# POGO_Tester_Rev1_Connectors.net
KiCad netlist of a schematic drawn in Altium Designer
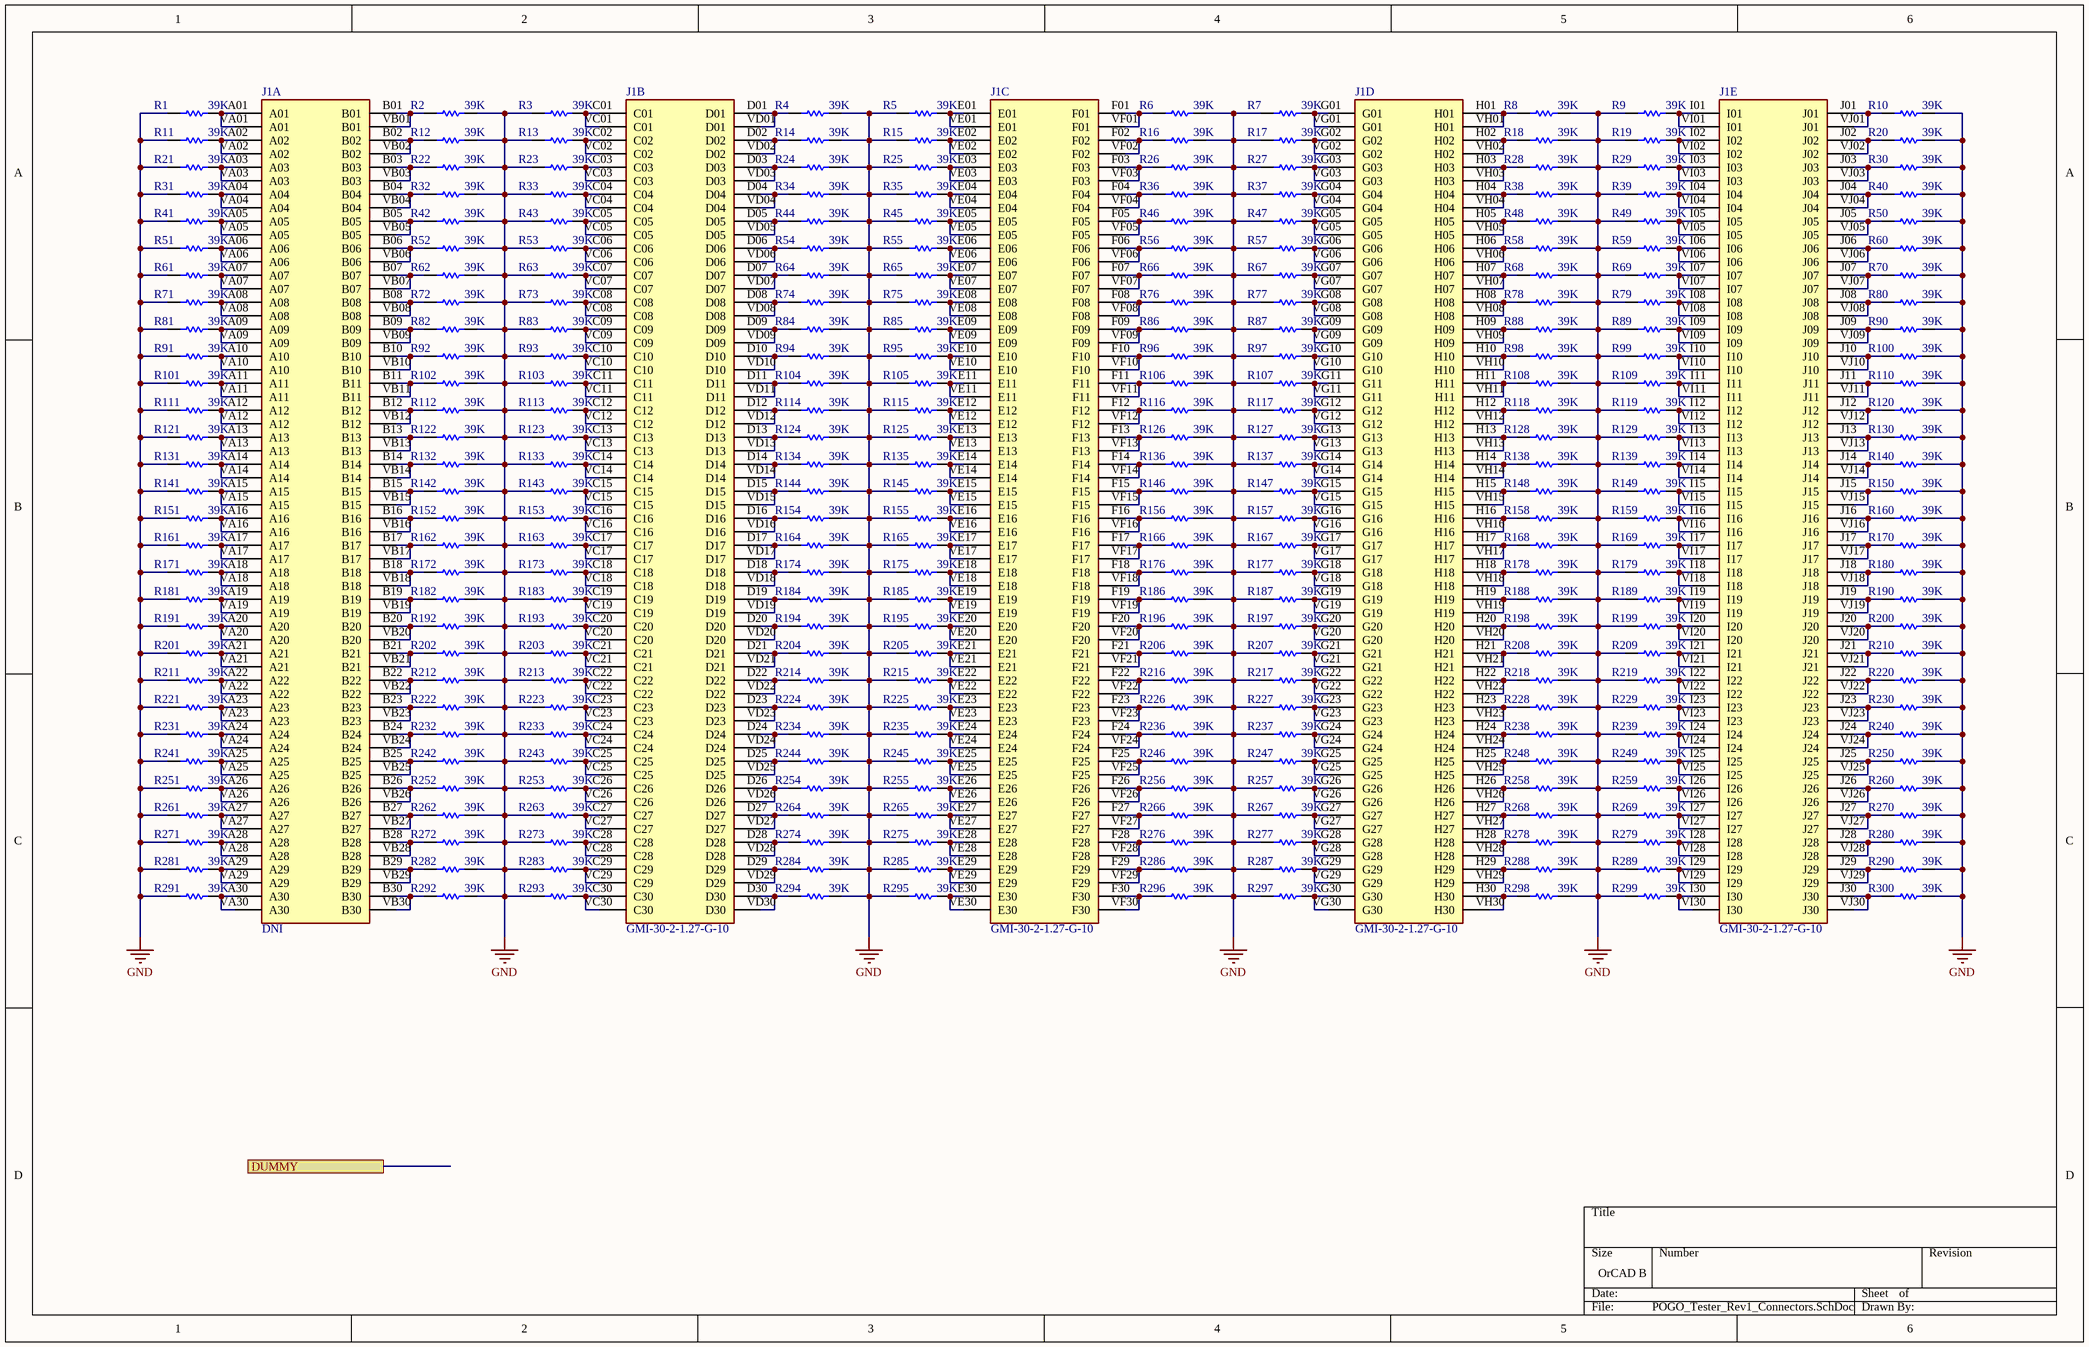
[diagram p0: POGO_Tester_Rev1_Connectors.SchDoc]

(export (version "E")
  (design (tool "Eeschema 10.0.6"))
  (components
    (comp (ref "J1")
      (value "DNI")
      (footprint "SAMTEC_GMI-30-2-1.27-G-10 - Nothing But Pads")
      (fields (field (name "MP") "GMI-30-2-1.27-G-10"))
      (libsource (lib "Avery Schem Library") (part "GMI-30-2-1.27-G-10"))
    )
    (comp (ref "R1")
      (value "39K")
      (footprint "DEFAULT_RESISTOR_0402")
      (description "RES 39K OHM 1% 1/3W 0402")
      (fields (field (name "POWER") "1/3W") (field (name "TOLERANCE") "1%"))
      (libsource (lib "Avery Altium Llibrary") (part "RCS040239K0FKED"))
    )
    (comp (ref "R2")
      (value "39K")
      (footprint "DEFAULT_RESISTOR_0402")
      (description "RES 39K OHM 1% 1/3W 0402")
      (fields (field (name "POWER") "1/3W") (field (name "TOLERANCE") "1%"))
      (libsource (lib "Avery Altium Llibrary") (part "RCS040239K0FKED"))
    )
    (comp (ref "R3")
      (value "39K")
      (footprint "DEFAULT_RESISTOR_0402")
      (description "RES 39K OHM 1% 1/3W 0402")
      (fields (field (name "POWER") "1/3W") (field (name "TOLERANCE") "1%"))
      (libsource (lib "Avery Altium Llibrary") (part "RCS040239K0FKED"))
    )
    (comp (ref "R4")
      (value "39K")
      (footprint "DEFAULT_RESISTOR_0402")
      (description "RES 39K OHM 1% 1/3W 0402")
      (fields (field (name "POWER") "1/3W") (field (name "TOLERANCE") "1%"))
      (libsource (lib "Avery Altium Llibrary") (part "RCS040239K0FKED"))
    )
    (comp (ref "R5")
      (value "39K")
      (footprint "DEFAULT_RESISTOR_0402")
      (description "RES 39K OHM 1% 1/3W 0402")
      (fields (field (name "POWER") "1/3W") (field (name "TOLERANCE") "1%"))
      (libsource (lib "Avery Altium Llibrary") (part "RCS040239K0FKED"))
    )
    (comp (ref "R6")
      (value "39K")
      (footprint "DEFAULT_RESISTOR_0402")
      (description "RES 39K OHM 1% 1/3W 0402")
      (fields (field (name "POWER") "1/3W") (field (name "TOLERANCE") "1%"))
      (libsource (lib "Avery Altium Llibrary") (part "RCS040239K0FKED"))
    )
    (comp (ref "R7")
      (value "39K")
      (footprint "DEFAULT_RESISTOR_0402")
      (description "RES 39K OHM 1% 1/3W 0402")
      (fields (field (name "POWER") "1/3W") (field (name "TOLERANCE") "1%"))
      (libsource (lib "Avery Altium Llibrary") (part "RCS040239K0FKED"))
    )
    (comp (ref "R8")
      (value "39K")
      (footprint "DEFAULT_RESISTOR_0402")
      (description "RES 39K OHM 1% 1/3W 0402")
      (fields (field (name "POWER") "1/3W") (field (name "TOLERANCE") "1%"))
      (libsource (lib "Avery Altium Llibrary") (part "RCS040239K0FKED"))
    )
    (comp (ref "R9")
      (value "39K")
      (footprint "DEFAULT_RESISTOR_0402")
      (description "RES 39K OHM 1% 1/3W 0402")
      (fields (field (name "POWER") "1/3W") (field (name "TOLERANCE") "1%"))
      (libsource (lib "Avery Altium Llibrary") (part "RCS040239K0FKED"))
    )
    (comp (ref "R10")
      (value "39K")
      (footprint "DEFAULT_RESISTOR_0402")
      (description "RES 39K OHM 1% 1/3W 0402")
      (fields (field (name "POWER") "1/3W") (field (name "TOLERANCE") "1%"))
      (libsource (lib "Avery Altium Llibrary") (part "RCS040239K0FKED"))
    )
    (comp (ref "R11")
      (value "39K")
      (footprint "DEFAULT_RESISTOR_0402")
      (description "RES 39K OHM 1% 1/3W 0402")
      (fields (field (name "POWER") "1/3W") (field (name "TOLERANCE") "1%"))
      (libsource (lib "Avery Altium Llibrary") (part "RCS040239K0FKED"))
    )
    (comp (ref "R12")
      (value "39K")
      (footprint "DEFAULT_RESISTOR_0402")
      (description "RES 39K OHM 1% 1/3W 0402")
      (fields (field (name "POWER") "1/3W") (field (name "TOLERANCE") "1%"))
      (libsource (lib "Avery Altium Llibrary") (part "RCS040239K0FKED"))
    )
    (comp (ref "R13")
      (value "39K")
      (footprint "DEFAULT_RESISTOR_0402")
      (description "RES 39K OHM 1% 1/3W 0402")
      (fields (field (name "POWER") "1/3W") (field (name "TOLERANCE") "1%"))
      (libsource (lib "Avery Altium Llibrary") (part "RCS040239K0FKED"))
    )
    (comp (ref "R14")
      (value "39K")
      (footprint "DEFAULT_RESISTOR_0402")
      (description "RES 39K OHM 1% 1/3W 0402")
      (fields (field (name "POWER") "1/3W") (field (name "TOLERANCE") "1%"))
      (libsource (lib "Avery Altium Llibrary") (part "RCS040239K0FKED"))
    )
    (comp (ref "R15")
      (value "39K")
      (footprint "DEFAULT_RESISTOR_0402")
      (description "RES 39K OHM 1% 1/3W 0402")
      (fields (field (name "POWER") "1/3W") (field (name "TOLERANCE") "1%"))
      (libsource (lib "Avery Altium Llibrary") (part "RCS040239K0FKED"))
    )
    (comp (ref "R16")
      (value "39K")
      (footprint "DEFAULT_RESISTOR_0402")
      (description "RES 39K OHM 1% 1/3W 0402")
      (fields (field (name "POWER") "1/3W") (field (name "TOLERANCE") "1%"))
      (libsource (lib "Avery Altium Llibrary") (part "RCS040239K0FKED"))
    )
    (comp (ref "R17")
      (value "39K")
      (footprint "DEFAULT_RESISTOR_0402")
      (description "RES 39K OHM 1% 1/3W 0402")
      (fields (field (name "POWER") "1/3W") (field (name "TOLERANCE") "1%"))
      (libsource (lib "Avery Altium Llibrary") (part "RCS040239K0FKED"))
    )
    (comp (ref "R18")
      (value "39K")
      (footprint "DEFAULT_RESISTOR_0402")
      (description "RES 39K OHM 1% 1/3W 0402")
      (fields (field (name "POWER") "1/3W") (field (name "TOLERANCE") "1%"))
      (libsource (lib "Avery Altium Llibrary") (part "RCS040239K0FKED"))
    )
    (comp (ref "R19")
      (value "39K")
      (footprint "DEFAULT_RESISTOR_0402")
      (description "RES 39K OHM 1% 1/3W 0402")
      (fields (field (name "POWER") "1/3W") (field (name "TOLERANCE") "1%"))
      (libsource (lib "Avery Altium Llibrary") (part "RCS040239K0FKED"))
    )
    (comp (ref "R20")
      (value "39K")
      (footprint "DEFAULT_RESISTOR_0402")
      (description "RES 39K OHM 1% 1/3W 0402")
      (fields (field (name "POWER") "1/3W") (field (name "TOLERANCE") "1%"))
      (libsource (lib "Avery Altium Llibrary") (part "RCS040239K0FKED"))
    )
    (comp (ref "R21")
      (value "39K")
      (footprint "DEFAULT_RESISTOR_0402")
      (description "RES 39K OHM 1% 1/3W 0402")
      (fields (field (name "POWER") "1/3W") (field (name "TOLERANCE") "1%"))
      (libsource (lib "Avery Altium Llibrary") (part "RCS040239K0FKED"))
    )
    (comp (ref "R22")
      (value "39K")
      (footprint "DEFAULT_RESISTOR_0402")
      (description "RES 39K OHM 1% 1/3W 0402")
      (fields (field (name "POWER") "1/3W") (field (name "TOLERANCE") "1%"))
      (libsource (lib "Avery Altium Llibrary") (part "RCS040239K0FKED"))
    )
    (comp (ref "R23")
      (value "39K")
      (footprint "DEFAULT_RESISTOR_0402")
      (description "RES 39K OHM 1% 1/3W 0402")
      (fields (field (name "POWER") "1/3W") (field (name "TOLERANCE") "1%"))
      (libsource (lib "Avery Altium Llibrary") (part "RCS040239K0FKED"))
    )
    (comp (ref "R24")
      (value "39K")
      (footprint "DEFAULT_RESISTOR_0402")
      (description "RES 39K OHM 1% 1/3W 0402")
      (fields (field (name "POWER") "1/3W") (field (name "TOLERANCE") "1%"))
      (libsource (lib "Avery Altium Llibrary") (part "RCS040239K0FKED"))
    )
    (comp (ref "R25")
      (value "39K")
      (footprint "DEFAULT_RESISTOR_0402")
      (description "RES 39K OHM 1% 1/3W 0402")
      (fields (field (name "POWER") "1/3W") (field (name "TOLERANCE") "1%"))
      (libsource (lib "Avery Altium Llibrary") (part "RCS040239K0FKED"))
    )
    (comp (ref "R26")
      (value "39K")
      (footprint "DEFAULT_RESISTOR_0402")
      (description "RES 39K OHM 1% 1/3W 0402")
      (fields (field (name "POWER") "1/3W") (field (name "TOLERANCE") "1%"))
      (libsource (lib "Avery Altium Llibrary") (part "RCS040239K0FKED"))
    )
    (comp (ref "R27")
      (value "39K")
      (footprint "DEFAULT_RESISTOR_0402")
      (description "RES 39K OHM 1% 1/3W 0402")
      (fields (field (name "POWER") "1/3W") (field (name "TOLERANCE") "1%"))
      (libsource (lib "Avery Altium Llibrary") (part "RCS040239K0FKED"))
    )
    (comp (ref "R28")
      (value "39K")
      (footprint "DEFAULT_RESISTOR_0402")
      (description "RES 39K OHM 1% 1/3W 0402")
      (fields (field (name "POWER") "1/3W") (field (name "TOLERANCE") "1%"))
      (libsource (lib "Avery Altium Llibrary") (part "RCS040239K0FKED"))
    )
    (comp (ref "R29")
      (value "39K")
      (footprint "DEFAULT_RESISTOR_0402")
      (description "RES 39K OHM 1% 1/3W 0402")
      (fields (field (name "POWER") "1/3W") (field (name "TOLERANCE") "1%"))
      (libsource (lib "Avery Altium Llibrary") (part "RCS040239K0FKED"))
    )
    (comp (ref "R30")
      (value "39K")
      (footprint "DEFAULT_RESISTOR_0402")
      (description "RES 39K OHM 1% 1/3W 0402")
      (fields (field (name "POWER") "1/3W") (field (name "TOLERANCE") "1%"))
      (libsource (lib "Avery Altium Llibrary") (part "RCS040239K0FKED"))
    )
    (comp (ref "R31")
      (value "39K")
      (footprint "DEFAULT_RESISTOR_0402")
      (description "RES 39K OHM 1% 1/3W 0402")
      (fields (field (name "POWER") "1/3W") (field (name "TOLERANCE") "1%"))
      (libsource (lib "Avery Altium Llibrary") (part "RCS040239K0FKED"))
    )
    (comp (ref "R32")
      (value "39K")
      (footprint "DEFAULT_RESISTOR_0402")
      (description "RES 39K OHM 1% 1/3W 0402")
      (fields (field (name "POWER") "1/3W") (field (name "TOLERANCE") "1%"))
      (libsource (lib "Avery Altium Llibrary") (part "RCS040239K0FKED"))
    )
    (comp (ref "R33")
      (value "39K")
      (footprint "DEFAULT_RESISTOR_0402")
      (description "RES 39K OHM 1% 1/3W 0402")
      (fields (field (name "POWER") "1/3W") (field (name "TOLERANCE") "1%"))
      (libsource (lib "Avery Altium Llibrary") (part "RCS040239K0FKED"))
    )
    (comp (ref "R34")
      (value "39K")
      (footprint "DEFAULT_RESISTOR_0402")
      (description "RES 39K OHM 1% 1/3W 0402")
      (fields (field (name "POWER") "1/3W") (field (name "TOLERANCE") "1%"))
      (libsource (lib "Avery Altium Llibrary") (part "RCS040239K0FKED"))
    )
    (comp (ref "R35")
      (value "39K")
      (footprint "DEFAULT_RESISTOR_0402")
      (description "RES 39K OHM 1% 1/3W 0402")
      (fields (field (name "POWER") "1/3W") (field (name "TOLERANCE") "1%"))
      (libsource (lib "Avery Altium Llibrary") (part "RCS040239K0FKED"))
    )
    (comp (ref "R36")
      (value "39K")
      (footprint "DEFAULT_RESISTOR_0402")
      (description "RES 39K OHM 1% 1/3W 0402")
      (fields (field (name "POWER") "1/3W") (field (name "TOLERANCE") "1%"))
      (libsource (lib "Avery Altium Llibrary") (part "RCS040239K0FKED"))
    )
    (comp (ref "R37")
      (value "39K")
      (footprint "DEFAULT_RESISTOR_0402")
      (description "RES 39K OHM 1% 1/3W 0402")
      (fields (field (name "POWER") "1/3W") (field (name "TOLERANCE") "1%"))
      (libsource (lib "Avery Altium Llibrary") (part "RCS040239K0FKED"))
    )
    (comp (ref "R38")
      (value "39K")
      (footprint "DEFAULT_RESISTOR_0402")
      (description "RES 39K OHM 1% 1/3W 0402")
      (fields (field (name "POWER") "1/3W") (field (name "TOLERANCE") "1%"))
      (libsource (lib "Avery Altium Llibrary") (part "RCS040239K0FKED"))
    )
    (comp (ref "R39")
      (value "39K")
      (footprint "DEFAULT_RESISTOR_0402")
      (description "RES 39K OHM 1% 1/3W 0402")
      (fields (field (name "POWER") "1/3W") (field (name "TOLERANCE") "1%"))
      (libsource (lib "Avery Altium Llibrary") (part "RCS040239K0FKED"))
    )
    (comp (ref "R40")
      (value "39K")
      (footprint "DEFAULT_RESISTOR_0402")
      (description "RES 39K OHM 1% 1/3W 0402")
      (fields (field (name "POWER") "1/3W") (field (name "TOLERANCE") "1%"))
      (libsource (lib "Avery Altium Llibrary") (part "RCS040239K0FKED"))
    )
    (comp (ref "R41")
      (value "39K")
      (footprint "DEFAULT_RESISTOR_0402")
      (description "RES 39K OHM 1% 1/3W 0402")
      (fields (field (name "POWER") "1/3W") (field (name "TOLERANCE") "1%"))
      (libsource (lib "Avery Altium Llibrary") (part "RCS040239K0FKED"))
    )
    (comp (ref "R42")
      (value "39K")
      (footprint "DEFAULT_RESISTOR_0402")
      (description "RES 39K OHM 1% 1/3W 0402")
      (fields (field (name "POWER") "1/3W") (field (name "TOLERANCE") "1%"))
      (libsource (lib "Avery Altium Llibrary") (part "RCS040239K0FKED"))
    )
    (comp (ref "R43")
      (value "39K")
      (footprint "DEFAULT_RESISTOR_0402")
      (description "RES 39K OHM 1% 1/3W 0402")
      (fields (field (name "POWER") "1/3W") (field (name "TOLERANCE") "1%"))
      (libsource (lib "Avery Altium Llibrary") (part "RCS040239K0FKED"))
    )
    (comp (ref "R44")
      (value "39K")
      (footprint "DEFAULT_RESISTOR_0402")
      (description "RES 39K OHM 1% 1/3W 0402")
      (fields (field (name "POWER") "1/3W") (field (name "TOLERANCE") "1%"))
      (libsource (lib "Avery Altium Llibrary") (part "RCS040239K0FKED"))
    )
    (comp (ref "R45")
      (value "39K")
      (footprint "DEFAULT_RESISTOR_0402")
      (description "RES 39K OHM 1% 1/3W 0402")
      (fields (field (name "POWER") "1/3W") (field (name "TOLERANCE") "1%"))
      (libsource (lib "Avery Altium Llibrary") (part "RCS040239K0FKED"))
    )
    (comp (ref "R46")
      (value "39K")
      (footprint "DEFAULT_RESISTOR_0402")
      (description "RES 39K OHM 1% 1/3W 0402")
      (fields (field (name "POWER") "1/3W") (field (name "TOLERANCE") "1%"))
      (libsource (lib "Avery Altium Llibrary") (part "RCS040239K0FKED"))
    )
    (comp (ref "R47")
      (value "39K")
      (footprint "DEFAULT_RESISTOR_0402")
      (description "RES 39K OHM 1% 1/3W 0402")
      (fields (field (name "POWER") "1/3W") (field (name "TOLERANCE") "1%"))
      (libsource (lib "Avery Altium Llibrary") (part "RCS040239K0FKED"))
    )
    (comp (ref "R48")
      (value "39K")
      (footprint "DEFAULT_RESISTOR_0402")
      (description "RES 39K OHM 1% 1/3W 0402")
      (fields (field (name "POWER") "1/3W") (field (name "TOLERANCE") "1%"))
      (libsource (lib "Avery Altium Llibrary") (part "RCS040239K0FKED"))
    )
    (comp (ref "R49")
      (value "39K")
      (footprint "DEFAULT_RESISTOR_0402")
      (description "RES 39K OHM 1% 1/3W 0402")
      (fields (field (name "POWER") "1/3W") (field (name "TOLERANCE") "1%"))
      (libsource (lib "Avery Altium Llibrary") (part "RCS040239K0FKED"))
    )
    (comp (ref "R50")
      (value "39K")
      (footprint "DEFAULT_RESISTOR_0402")
      (description "RES 39K OHM 1% 1/3W 0402")
      (fields (field (name "POWER") "1/3W") (field (name "TOLERANCE") "1%"))
      (libsource (lib "Avery Altium Llibrary") (part "RCS040239K0FKED"))
    )
    (comp (ref "R51")
      (value "39K")
      (footprint "DEFAULT_RESISTOR_0402")
      (description "RES 39K OHM 1% 1/3W 0402")
      (fields (field (name "POWER") "1/3W") (field (name "TOLERANCE") "1%"))
      (libsource (lib "Avery Altium Llibrary") (part "RCS040239K0FKED"))
    )
    (comp (ref "R52")
      (value "39K")
      (footprint "DEFAULT_RESISTOR_0402")
      (description "RES 39K OHM 1% 1/3W 0402")
      (fields (field (name "POWER") "1/3W") (field (name "TOLERANCE") "1%"))
      (libsource (lib "Avery Altium Llibrary") (part "RCS040239K0FKED"))
    )
    (comp (ref "R53")
      (value "39K")
      (footprint "DEFAULT_RESISTOR_0402")
      (description "RES 39K OHM 1% 1/3W 0402")
      (fields (field (name "POWER") "1/3W") (field (name "TOLERANCE") "1%"))
      (libsource (lib "Avery Altium Llibrary") (part "RCS040239K0FKED"))
    )
    (comp (ref "R54")
      (value "39K")
      (footprint "DEFAULT_RESISTOR_0402")
      (description "RES 39K OHM 1% 1/3W 0402")
      (fields (field (name "POWER") "1/3W") (field (name "TOLERANCE") "1%"))
      (libsource (lib "Avery Altium Llibrary") (part "RCS040239K0FKED"))
    )
    (comp (ref "R55")
      (value "39K")
      (footprint "DEFAULT_RESISTOR_0402")
      (description "RES 39K OHM 1% 1/3W 0402")
      (fields (field (name "POWER") "1/3W") (field (name "TOLERANCE") "1%"))
      (libsource (lib "Avery Altium Llibrary") (part "RCS040239K0FKED"))
    )
    (comp (ref "R56")
      (value "39K")
      (footprint "DEFAULT_RESISTOR_0402")
      (description "RES 39K OHM 1% 1/3W 0402")
      (fields (field (name "POWER") "1/3W") (field (name "TOLERANCE") "1%"))
      (libsource (lib "Avery Altium Llibrary") (part "RCS040239K0FKED"))
    )
    (comp (ref "R57")
      (value "39K")
      (footprint "DEFAULT_RESISTOR_0402")
      (description "RES 39K OHM 1% 1/3W 0402")
      (fields (field (name "POWER") "1/3W") (field (name "TOLERANCE") "1%"))
      (libsource (lib "Avery Altium Llibrary") (part "RCS040239K0FKED"))
    )
    (comp (ref "R58")
      (value "39K")
      (footprint "DEFAULT_RESISTOR_0402")
      (description "RES 39K OHM 1% 1/3W 0402")
      (fields (field (name "POWER") "1/3W") (field (name "TOLERANCE") "1%"))
      (libsource (lib "Avery Altium Llibrary") (part "RCS040239K0FKED"))
    )
    (comp (ref "R59")
      (value "39K")
      (footprint "DEFAULT_RESISTOR_0402")
      (description "RES 39K OHM 1% 1/3W 0402")
      (fields (field (name "POWER") "1/3W") (field (name "TOLERANCE") "1%"))
      (libsource (lib "Avery Altium Llibrary") (part "RCS040239K0FKED"))
    )
    (comp (ref "R60")
      (value "39K")
      (footprint "DEFAULT_RESISTOR_0402")
      (description "RES 39K OHM 1% 1/3W 0402")
      (fields (field (name "POWER") "1/3W") (field (name "TOLERANCE") "1%"))
      (libsource (lib "Avery Altium Llibrary") (part "RCS040239K0FKED"))
    )
    (comp (ref "R61")
      (value "39K")
      (footprint "DEFAULT_RESISTOR_0402")
      (description "RES 39K OHM 1% 1/3W 0402")
      (fields (field (name "POWER") "1/3W") (field (name "TOLERANCE") "1%"))
      (libsource (lib "Avery Altium Llibrary") (part "RCS040239K0FKED"))
    )
    (comp (ref "R62")
      (value "39K")
      (footprint "DEFAULT_RESISTOR_0402")
      (description "RES 39K OHM 1% 1/3W 0402")
      (fields (field (name "POWER") "1/3W") (field (name "TOLERANCE") "1%"))
      (libsource (lib "Avery Altium Llibrary") (part "RCS040239K0FKED"))
    )
    (comp (ref "R63")
      (value "39K")
      (footprint "DEFAULT_RESISTOR_0402")
      (description "RES 39K OHM 1% 1/3W 0402")
      (fields (field (name "POWER") "1/3W") (field (name "TOLERANCE") "1%"))
      (libsource (lib "Avery Altium Llibrary") (part "RCS040239K0FKED"))
    )
    (comp (ref "R64")
      (value "39K")
      (footprint "DEFAULT_RESISTOR_0402")
      (description "RES 39K OHM 1% 1/3W 0402")
      (fields (field (name "POWER") "1/3W") (field (name "TOLERANCE") "1%"))
      (libsource (lib "Avery Altium Llibrary") (part "RCS040239K0FKED"))
    )
    (comp (ref "R65")
      (value "39K")
      (footprint "DEFAULT_RESISTOR_0402")
      (description "RES 39K OHM 1% 1/3W 0402")
      (fields (field (name "POWER") "1/3W") (field (name "TOLERANCE") "1%"))
      (libsource (lib "Avery Altium Llibrary") (part "RCS040239K0FKED"))
    )
    (comp (ref "R66")
      (value "39K")
      (footprint "DEFAULT_RESISTOR_0402")
      (description "RES 39K OHM 1% 1/3W 0402")
      (fields (field (name "POWER") "1/3W") (field (name "TOLERANCE") "1%"))
      (libsource (lib "Avery Altium Llibrary") (part "RCS040239K0FKED"))
    )
    (comp (ref "R67")
      (value "39K")
      (footprint "DEFAULT_RESISTOR_0402")
      (description "RES 39K OHM 1% 1/3W 0402")
      (fields (field (name "POWER") "1/3W") (field (name "TOLERANCE") "1%"))
      (libsource (lib "Avery Altium Llibrary") (part "RCS040239K0FKED"))
    )
    (comp (ref "R68")
      (value "39K")
      (footprint "DEFAULT_RESISTOR_0402")
      (description "RES 39K OHM 1% 1/3W 0402")
      (fields (field (name "POWER") "1/3W") (field (name "TOLERANCE") "1%"))
      (libsource (lib "Avery Altium Llibrary") (part "RCS040239K0FKED"))
    )
    (comp (ref "R69")
      (value "39K")
      (footprint "DEFAULT_RESISTOR_0402")
      (description "RES 39K OHM 1% 1/3W 0402")
      (fields (field (name "POWER") "1/3W") (field (name "TOLERANCE") "1%"))
      (libsource (lib "Avery Altium Llibrary") (part "RCS040239K0FKED"))
    )
    (comp (ref "R70")
      (value "39K")
      (footprint "DEFAULT_RESISTOR_0402")
      (description "RES 39K OHM 1% 1/3W 0402")
      (fields (field (name "POWER") "1/3W") (field (name "TOLERANCE") "1%"))
      (libsource (lib "Avery Altium Llibrary") (part "RCS040239K0FKED"))
    )
    (comp (ref "R71")
      (value "39K")
      (footprint "DEFAULT_RESISTOR_0402")
      (description "RES 39K OHM 1% 1/3W 0402")
      (fields (field (name "POWER") "1/3W") (field (name "TOLERANCE") "1%"))
      (libsource (lib "Avery Altium Llibrary") (part "RCS040239K0FKED"))
    )
    (comp (ref "R72")
      (value "39K")
      (footprint "DEFAULT_RESISTOR_0402")
      (description "RES 39K OHM 1% 1/3W 0402")
      (fields (field (name "POWER") "1/3W") (field (name "TOLERANCE") "1%"))
      (libsource (lib "Avery Altium Llibrary") (part "RCS040239K0FKED"))
    )
    (comp (ref "R73")
      (value "39K")
      (footprint "DEFAULT_RESISTOR_0402")
      (description "RES 39K OHM 1% 1/3W 0402")
      (fields (field (name "POWER") "1/3W") (field (name "TOLERANCE") "1%"))
      (libsource (lib "Avery Altium Llibrary") (part "RCS040239K0FKED"))
    )
    (comp (ref "R74")
      (value "39K")
      (footprint "DEFAULT_RESISTOR_0402")
      (description "RES 39K OHM 1% 1/3W 0402")
      (fields (field (name "POWER") "1/3W") (field (name "TOLERANCE") "1%"))
      (libsource (lib "Avery Altium Llibrary") (part "RCS040239K0FKED"))
    )
    (comp (ref "R75")
      (value "39K")
      (footprint "DEFAULT_RESISTOR_0402")
      (description "RES 39K OHM 1% 1/3W 0402")
      (fields (field (name "POWER") "1/3W") (field (name "TOLERANCE") "1%"))
      (libsource (lib "Avery Altium Llibrary") (part "RCS040239K0FKED"))
    )
    (comp (ref "R76")
      (value "39K")
      (footprint "DEFAULT_RESISTOR_0402")
      (description "RES 39K OHM 1% 1/3W 0402")
      (fields (field (name "POWER") "1/3W") (field (name "TOLERANCE") "1%"))
      (libsource (lib "Avery Altium Llibrary") (part "RCS040239K0FKED"))
    )
    (comp (ref "R77")
      (value "39K")
      (footprint "DEFAULT_RESISTOR_0402")
      (description "RES 39K OHM 1% 1/3W 0402")
      (fields (field (name "POWER") "1/3W") (field (name "TOLERANCE") "1%"))
      (libsource (lib "Avery Altium Llibrary") (part "RCS040239K0FKED"))
    )
    (comp (ref "R78")
      (value "39K")
      (footprint "DEFAULT_RESISTOR_0402")
      (description "RES 39K OHM 1% 1/3W 0402")
      (fields (field (name "POWER") "1/3W") (field (name "TOLERANCE") "1%"))
      (libsource (lib "Avery Altium Llibrary") (part "RCS040239K0FKED"))
    )
    (comp (ref "R79")
      (value "39K")
      (footprint "DEFAULT_RESISTOR_0402")
      (description "RES 39K OHM 1% 1/3W 0402")
      (fields (field (name "POWER") "1/3W") (field (name "TOLERANCE") "1%"))
      (libsource (lib "Avery Altium Llibrary") (part "RCS040239K0FKED"))
    )
    (comp (ref "R80")
      (value "39K")
      (footprint "DEFAULT_RESISTOR_0402")
      (description "RES 39K OHM 1% 1/3W 0402")
      (fields (field (name "POWER") "1/3W") (field (name "TOLERANCE") "1%"))
      (libsource (lib "Avery Altium Llibrary") (part "RCS040239K0FKED"))
    )
    (comp (ref "R81")
      (value "39K")
      (footprint "DEFAULT_RESISTOR_0402")
      (description "RES 39K OHM 1% 1/3W 0402")
      (fields (field (name "POWER") "1/3W") (field (name "TOLERANCE") "1%"))
      (libsource (lib "Avery Altium Llibrary") (part "RCS040239K0FKED"))
    )
    (comp (ref "R82")
      (value "39K")
      (footprint "DEFAULT_RESISTOR_0402")
      (description "RES 39K OHM 1% 1/3W 0402")
      (fields (field (name "POWER") "1/3W") (field (name "TOLERANCE") "1%"))
      (libsource (lib "Avery Altium Llibrary") (part "RCS040239K0FKED"))
    )
    (comp (ref "R83")
      (value "39K")
      (footprint "DEFAULT_RESISTOR_0402")
      (description "RES 39K OHM 1% 1/3W 0402")
      (fields (field (name "POWER") "1/3W") (field (name "TOLERANCE") "1%"))
      (libsource (lib "Avery Altium Llibrary") (part "RCS040239K0FKED"))
    )
    (comp (ref "R84")
      (value "39K")
      (footprint "DEFAULT_RESISTOR_0402")
      (description "RES 39K OHM 1% 1/3W 0402")
      (fields (field (name "POWER") "1/3W") (field (name "TOLERANCE") "1%"))
      (libsource (lib "Avery Altium Llibrary") (part "RCS040239K0FKED"))
    )
    (comp (ref "R85")
      (value "39K")
      (footprint "DEFAULT_RESISTOR_0402")
      (description "RES 39K OHM 1% 1/3W 0402")
      (fields (field (name "POWER") "1/3W") (field (name "TOLERANCE") "1%"))
      (libsource (lib "Avery Altium Llibrary") (part "RCS040239K0FKED"))
    )
    (comp (ref "R86")
      (value "39K")
      (footprint "DEFAULT_RESISTOR_0402")
      (description "RES 39K OHM 1% 1/3W 0402")
      (fields (field (name "POWER") "1/3W") (field (name "TOLERANCE") "1%"))
      (libsource (lib "Avery Altium Llibrary") (part "RCS040239K0FKED"))
    )
    (comp (ref "R87")
      (value "39K")
      (footprint "DEFAULT_RESISTOR_0402")
      (description "RES 39K OHM 1% 1/3W 0402")
      (fields (field (name "POWER") "1/3W") (field (name "TOLERANCE") "1%"))
      (libsource (lib "Avery Altium Llibrary") (part "RCS040239K0FKED"))
    )
    (comp (ref "R88")
      (value "39K")
      (footprint "DEFAULT_RESISTOR_0402")
      (description "RES 39K OHM 1% 1/3W 0402")
      (fields (field (name "POWER") "1/3W") (field (name "TOLERANCE") "1%"))
      (libsource (lib "Avery Altium Llibrary") (part "RCS040239K0FKED"))
    )
    (comp (ref "R89")
      (value "39K")
      (footprint "DEFAULT_RESISTOR_0402")
      (description "RES 39K OHM 1% 1/3W 0402")
      (fields (field (name "POWER") "1/3W") (field (name "TOLERANCE") "1%"))
      (libsource (lib "Avery Altium Llibrary") (part "RCS040239K0FKED"))
    )
    (comp (ref "R90")
      (value "39K")
      (footprint "DEFAULT_RESISTOR_0402")
      (description "RES 39K OHM 1% 1/3W 0402")
      (fields (field (name "POWER") "1/3W") (field (name "TOLERANCE") "1%"))
      (libsource (lib "Avery Altium Llibrary") (part "RCS040239K0FKED"))
    )
    (comp (ref "R91")
      (value "39K")
      (footprint "DEFAULT_RESISTOR_0402")
      (description "RES 39K OHM 1% 1/3W 0402")
      (fields (field (name "POWER") "1/3W") (field (name "TOLERANCE") "1%"))
      (libsource (lib "Avery Altium Llibrary") (part "RCS040239K0FKED"))
    )
    (comp (ref "R92")
      (value "39K")
      (footprint "DEFAULT_RESISTOR_0402")
      (description "RES 39K OHM 1% 1/3W 0402")
      (fields (field (name "POWER") "1/3W") (field (name "TOLERANCE") "1%"))
      (libsource (lib "Avery Altium Llibrary") (part "RCS040239K0FKED"))
    )
    (comp (ref "R93")
      (value "39K")
      (footprint "DEFAULT_RESISTOR_0402")
      (description "RES 39K OHM 1% 1/3W 0402")
      (fields (field (name "POWER") "1/3W") (field (name "TOLERANCE") "1%"))
      (libsource (lib "Avery Altium Llibrary") (part "RCS040239K0FKED"))
    )
    (comp (ref "R94")
      (value "39K")
      (footprint "DEFAULT_RESISTOR_0402")
      (description "RES 39K OHM 1% 1/3W 0402")
      (fields (field (name "POWER") "1/3W") (field (name "TOLERANCE") "1%"))
      (libsource (lib "Avery Altium Llibrary") (part "RCS040239K0FKED"))
    )
    (comp (ref "R95")
      (value "39K")
      (footprint "DEFAULT_RESISTOR_0402")
      (description "RES 39K OHM 1% 1/3W 0402")
      (fields (field (name "POWER") "1/3W") (field (name "TOLERANCE") "1%"))
      (libsource (lib "Avery Altium Llibrary") (part "RCS040239K0FKED"))
    )
    (comp (ref "R96")
      (value "39K")
      (footprint "DEFAULT_RESISTOR_0402")
      (description "RES 39K OHM 1% 1/3W 0402")
      (fields (field (name "POWER") "1/3W") (field (name "TOLERANCE") "1%"))
      (libsource (lib "Avery Altium Llibrary") (part "RCS040239K0FKED"))
    )
    (comp (ref "R97")
      (value "39K")
      (footprint "DEFAULT_RESISTOR_0402")
      (description "RES 39K OHM 1% 1/3W 0402")
      (fields (field (name "POWER") "1/3W") (field (name "TOLERANCE") "1%"))
      (libsource (lib "Avery Altium Llibrary") (part "RCS040239K0FKED"))
    )
    (comp (ref "R98")
      (value "39K")
      (footprint "DEFAULT_RESISTOR_0402")
      (description "RES 39K OHM 1% 1/3W 0402")
      (fields (field (name "POWER") "1/3W") (field (name "TOLERANCE") "1%"))
      (libsource (lib "Avery Altium Llibrary") (part "RCS040239K0FKED"))
    )
    (comp (ref "R99")
      (value "39K")
      (footprint "DEFAULT_RESISTOR_0402")
      (description "RES 39K OHM 1% 1/3W 0402")
      (fields (field (name "POWER") "1/3W") (field (name "TOLERANCE") "1%"))
      (libsource (lib "Avery Altium Llibrary") (part "RCS040239K0FKED"))
    )
    (comp (ref "R100")
      (value "39K")
      (footprint "DEFAULT_RESISTOR_0402")
      (description "RES 39K OHM 1% 1/3W 0402")
      (fields (field (name "POWER") "1/3W") (field (name "TOLERANCE") "1%"))
      (libsource (lib "Avery Altium Llibrary") (part "RCS040239K0FKED"))
    )
    (comp (ref "R101")
      (value "39K")
      (footprint "DEFAULT_RESISTOR_0402")
      (description "RES 39K OHM 1% 1/3W 0402")
      (fields (field (name "POWER") "1/3W") (field (name "TOLERANCE") "1%"))
      (libsource (lib "Avery Altium Llibrary") (part "RCS040239K0FKED"))
    )
    (comp (ref "R102")
      (value "39K")
      (footprint "DEFAULT_RESISTOR_0402")
      (description "RES 39K OHM 1% 1/3W 0402")
      (fields (field (name "POWER") "1/3W") (field (name "TOLERANCE") "1%"))
      (libsource (lib "Avery Altium Llibrary") (part "RCS040239K0FKED"))
    )
    (comp (ref "R103")
      (value "39K")
      (footprint "DEFAULT_RESISTOR_0402")
      (description "RES 39K OHM 1% 1/3W 0402")
      (fields (field (name "POWER") "1/3W") (field (name "TOLERANCE") "1%"))
      (libsource (lib "Avery Altium Llibrary") (part "RCS040239K0FKED"))
    )
    (comp (ref "R104")
      (value "39K")
      (footprint "DEFAULT_RESISTOR_0402")
      (description "RES 39K OHM 1% 1/3W 0402")
      (fields (field (name "POWER") "1/3W") (field (name "TOLERANCE") "1%"))
      (libsource (lib "Avery Altium Llibrary") (part "RCS040239K0FKED"))
    )
    (comp (ref "R105")
      (value "39K")
      (footprint "DEFAULT_RESISTOR_0402")
      (description "RES 39K OHM 1% 1/3W 0402")
      (fields (field (name "POWER") "1/3W") (field (name "TOLERANCE") "1%"))
      (libsource (lib "Avery Altium Llibrary") (part "RCS040239K0FKED"))
    )
    (comp (ref "R106")
      (value "39K")
      (footprint "DEFAULT_RESISTOR_0402")
      (description "RES 39K OHM 1% 1/3W 0402")
      (fields (field (name "POWER") "1/3W") (field (name "TOLERANCE") "1%"))
      (libsource (lib "Avery Altium Llibrary") (part "RCS040239K0FKED"))
    )
    (comp (ref "R107")
      (value "39K")
      (footprint "DEFAULT_RESISTOR_0402")
      (description "RES 39K OHM 1% 1/3W 0402")
      (fields (field (name "POWER") "1/3W") (field (name "TOLERANCE") "1%"))
      (libsource (lib "Avery Altium Llibrary") (part "RCS040239K0FKED"))
    )
    (comp (ref "R108")
      (value "39K")
      (footprint "DEFAULT_RESISTOR_0402")
      (description "RES 39K OHM 1% 1/3W 0402")
      (fields (field (name "POWER") "1/3W") (field (name "TOLERANCE") "1%"))
      (libsource (lib "Avery Altium Llibrary") (part "RCS040239K0FKED"))
    )
    (comp (ref "R109")
      (value "39K")
      (footprint "DEFAULT_RESISTOR_0402")
      (description "RES 39K OHM 1% 1/3W 0402")
      (fields (field (name "POWER") "1/3W") (field (name "TOLERANCE") "1%"))
      (libsource (lib "Avery Altium Llibrary") (part "RCS040239K0FKED"))
    )
    (comp (ref "R110")
      (value "39K")
      (footprint "DEFAULT_RESISTOR_0402")
      (description "RES 39K OHM 1% 1/3W 0402")
      (fields (field (name "POWER") "1/3W") (field (name "TOLERANCE") "1%"))
      (libsource (lib "Avery Altium Llibrary") (part "RCS040239K0FKED"))
    )
    (comp (ref "R111")
      (value "39K")
      (footprint "DEFAULT_RESISTOR_0402")
      (description "RES 39K OHM 1% 1/3W 0402")
      (fields (field (name "POWER") "1/3W") (field (name "TOLERANCE") "1%"))
      (libsource (lib "Avery Altium Llibrary") (part "RCS040239K0FKED"))
    )
    (comp (ref "R112")
      (value "39K")
      (footprint "DEFAULT_RESISTOR_0402")
      (description "RES 39K OHM 1% 1/3W 0402")
      (fields (field (name "POWER") "1/3W") (field (name "TOLERANCE") "1%"))
      (libsource (lib "Avery Altium Llibrary") (part "RCS040239K0FKED"))
    )
    (comp (ref "R113")
      (value "39K")
      (footprint "DEFAULT_RESISTOR_0402")
      (description "RES 39K OHM 1% 1/3W 0402")
      (fields (field (name "POWER") "1/3W") (field (name "TOLERANCE") "1%"))
      (libsource (lib "Avery Altium Llibrary") (part "RCS040239K0FKED"))
    )
    (comp (ref "R114")
      (value "39K")
      (footprint "DEFAULT_RESISTOR_0402")
      (description "RES 39K OHM 1% 1/3W 0402")
      (fields (field (name "POWER") "1/3W") (field (name "TOLERANCE") "1%"))
      (libsource (lib "Avery Altium Llibrary") (part "RCS040239K0FKED"))
    )
    (comp (ref "R115")
      (value "39K")
      (footprint "DEFAULT_RESISTOR_0402")
      (description "RES 39K OHM 1% 1/3W 0402")
      (fields (field (name "POWER") "1/3W") (field (name "TOLERANCE") "1%"))
      (libsource (lib "Avery Altium Llibrary") (part "RCS040239K0FKED"))
    )
    (comp (ref "R116")
      (value "39K")
      (footprint "DEFAULT_RESISTOR_0402")
      (description "RES 39K OHM 1% 1/3W 0402")
      (fields (field (name "POWER") "1/3W") (field (name "TOLERANCE") "1%"))
      (libsource (lib "Avery Altium Llibrary") (part "RCS040239K0FKED"))
    )
    (comp (ref "R117")
      (value "39K")
      (footprint "DEFAULT_RESISTOR_0402")
      (description "RES 39K OHM 1% 1/3W 0402")
      (fields (field (name "POWER") "1/3W") (field (name "TOLERANCE") "1%"))
      (libsource (lib "Avery Altium Llibrary") (part "RCS040239K0FKED"))
    )
    (comp (ref "R118")
      (value "39K")
      (footprint "DEFAULT_RESISTOR_0402")
      (description "RES 39K OHM 1% 1/3W 0402")
      (fields (field (name "POWER") "1/3W") (field (name "TOLERANCE") "1%"))
      (libsource (lib "Avery Altium Llibrary") (part "RCS040239K0FKED"))
    )
    (comp (ref "R119")
      (value "39K")
      (footprint "DEFAULT_RESISTOR_0402")
      (description "RES 39K OHM 1% 1/3W 0402")
      (fields (field (name "POWER") "1/3W") (field (name "TOLERANCE") "1%"))
      (libsource (lib "Avery Altium Llibrary") (part "RCS040239K0FKED"))
    )
    (comp (ref "R120")
      (value "39K")
      (footprint "DEFAULT_RESISTOR_0402")
      (description "RES 39K OHM 1% 1/3W 0402")
      (fields (field (name "POWER") "1/3W") (field (name "TOLERANCE") "1%"))
      (libsource (lib "Avery Altium Llibrary") (part "RCS040239K0FKED"))
    )
    (comp (ref "R121")
      (value "39K")
      (footprint "DEFAULT_RESISTOR_0402")
      (description "RES 39K OHM 1% 1/3W 0402")
      (fields (field (name "POWER") "1/3W") (field (name "TOLERANCE") "1%"))
      (libsource (lib "Avery Altium Llibrary") (part "RCS040239K0FKED"))
    )
    (comp (ref "R122")
      (value "39K")
      (footprint "DEFAULT_RESISTOR_0402")
      (description "RES 39K OHM 1% 1/3W 0402")
      (fields (field (name "POWER") "1/3W") (field (name "TOLERANCE") "1%"))
      (libsource (lib "Avery Altium Llibrary") (part "RCS040239K0FKED"))
    )
    (comp (ref "R123")
      (value "39K")
      (footprint "DEFAULT_RESISTOR_0402")
      (description "RES 39K OHM 1% 1/3W 0402")
      (fields (field (name "POWER") "1/3W") (field (name "TOLERANCE") "1%"))
      (libsource (lib "Avery Altium Llibrary") (part "RCS040239K0FKED"))
    )
    (comp (ref "R124")
      (value "39K")
      (footprint "DEFAULT_RESISTOR_0402")
      (description "RES 39K OHM 1% 1/3W 0402")
      (fields (field (name "POWER") "1/3W") (field (name "TOLERANCE") "1%"))
      (libsource (lib "Avery Altium Llibrary") (part "RCS040239K0FKED"))
    )
    (comp (ref "R125")
      (value "39K")
      (footprint "DEFAULT_RESISTOR_0402")
      (description "RES 39K OHM 1% 1/3W 0402")
      (fields (field (name "POWER") "1/3W") (field (name "TOLERANCE") "1%"))
      (libsource (lib "Avery Altium Llibrary") (part "RCS040239K0FKED"))
    )
    (comp (ref "R126")
      (value "39K")
      (footprint "DEFAULT_RESISTOR_0402")
      (description "RES 39K OHM 1% 1/3W 0402")
      (fields (field (name "POWER") "1/3W") (field (name "TOLERANCE") "1%"))
      (libsource (lib "Avery Altium Llibrary") (part "RCS040239K0FKED"))
    )
    (comp (ref "R127")
      (value "39K")
      (footprint "DEFAULT_RESISTOR_0402")
      (description "RES 39K OHM 1% 1/3W 0402")
      (fields (field (name "POWER") "1/3W") (field (name "TOLERANCE") "1%"))
      (libsource (lib "Avery Altium Llibrary") (part "RCS040239K0FKED"))
    )
    (comp (ref "R128")
      (value "39K")
      (footprint "DEFAULT_RESISTOR_0402")
      (description "RES 39K OHM 1% 1/3W 0402")
      (fields (field (name "POWER") "1/3W") (field (name "TOLERANCE") "1%"))
      (libsource (lib "Avery Altium Llibrary") (part "RCS040239K0FKED"))
    )
    (comp (ref "R129")
      (value "39K")
      (footprint "DEFAULT_RESISTOR_0402")
      (description "RES 39K OHM 1% 1/3W 0402")
      (fields (field (name "POWER") "1/3W") (field (name "TOLERANCE") "1%"))
      (libsource (lib "Avery Altium Llibrary") (part "RCS040239K0FKED"))
    )
    (comp (ref "R130")
      (value "39K")
      (footprint "DEFAULT_RESISTOR_0402")
      (description "RES 39K OHM 1% 1/3W 0402")
      (fields (field (name "POWER") "1/3W") (field (name "TOLERANCE") "1%"))
      (libsource (lib "Avery Altium Llibrary") (part "RCS040239K0FKED"))
    )
    (comp (ref "R131")
      (value "39K")
      (footprint "DEFAULT_RESISTOR_0402")
      (description "RES 39K OHM 1% 1/3W 0402")
      (fields (field (name "POWER") "1/3W") (field (name "TOLERANCE") "1%"))
      (libsource (lib "Avery Altium Llibrary") (part "RCS040239K0FKED"))
    )
    (comp (ref "R132")
      (value "39K")
      (footprint "DEFAULT_RESISTOR_0402")
      (description "RES 39K OHM 1% 1/3W 0402")
      (fields (field (name "POWER") "1/3W") (field (name "TOLERANCE") "1%"))
      (libsource (lib "Avery Altium Llibrary") (part "RCS040239K0FKED"))
    )
    (comp (ref "R133")
      (value "39K")
      (footprint "DEFAULT_RESISTOR_0402")
      (description "RES 39K OHM 1% 1/3W 0402")
      (fields (field (name "POWER") "1/3W") (field (name "TOLERANCE") "1%"))
      (libsource (lib "Avery Altium Llibrary") (part "RCS040239K0FKED"))
    )
    (comp (ref "R134")
      (value "39K")
      (footprint "DEFAULT_RESISTOR_0402")
      (description "RES 39K OHM 1% 1/3W 0402")
      (fields (field (name "POWER") "1/3W") (field (name "TOLERANCE") "1%"))
      (libsource (lib "Avery Altium Llibrary") (part "RCS040239K0FKED"))
    )
    (comp (ref "R135")
      (value "39K")
      (footprint "DEFAULT_RESISTOR_0402")
      (description "RES 39K OHM 1% 1/3W 0402")
      (fields (field (name "POWER") "1/3W") (field (name "TOLERANCE") "1%"))
      (libsource (lib "Avery Altium Llibrary") (part "RCS040239K0FKED"))
    )
    (comp (ref "R136")
      (value "39K")
      (footprint "DEFAULT_RESISTOR_0402")
      (description "RES 39K OHM 1% 1/3W 0402")
      (fields (field (name "POWER") "1/3W") (field (name "TOLERANCE") "1%"))
      (libsource (lib "Avery Altium Llibrary") (part "RCS040239K0FKED"))
    )
    (comp (ref "R137")
      (value "39K")
      (footprint "DEFAULT_RESISTOR_0402")
      (description "RES 39K OHM 1% 1/3W 0402")
      (fields (field (name "POWER") "1/3W") (field (name "TOLERANCE") "1%"))
      (libsource (lib "Avery Altium Llibrary") (part "RCS040239K0FKED"))
    )
    (comp (ref "R138")
      (value "39K")
      (footprint "DEFAULT_RESISTOR_0402")
      (description "RES 39K OHM 1% 1/3W 0402")
      (fields (field (name "POWER") "1/3W") (field (name "TOLERANCE") "1%"))
      (libsource (lib "Avery Altium Llibrary") (part "RCS040239K0FKED"))
    )
    (comp (ref "R139")
      (value "39K")
      (footprint "DEFAULT_RESISTOR_0402")
      (description "RES 39K OHM 1% 1/3W 0402")
      (fields (field (name "POWER") "1/3W") (field (name "TOLERANCE") "1%"))
      (libsource (lib "Avery Altium Llibrary") (part "RCS040239K0FKED"))
    )
    (comp (ref "R140")
      (value "39K")
      (footprint "DEFAULT_RESISTOR_0402")
      (description "RES 39K OHM 1% 1/3W 0402")
      (fields (field (name "POWER") "1/3W") (field (name "TOLERANCE") "1%"))
      (libsource (lib "Avery Altium Llibrary") (part "RCS040239K0FKED"))
    )
    (comp (ref "R141")
      (value "39K")
      (footprint "DEFAULT_RESISTOR_0402")
      (description "RES 39K OHM 1% 1/3W 0402")
      (fields (field (name "POWER") "1/3W") (field (name "TOLERANCE") "1%"))
      (libsource (lib "Avery Altium Llibrary") (part "RCS040239K0FKED"))
    )
    (comp (ref "R142")
      (value "39K")
      (footprint "DEFAULT_RESISTOR_0402")
      (description "RES 39K OHM 1% 1/3W 0402")
      (fields (field (name "POWER") "1/3W") (field (name "TOLERANCE") "1%"))
      (libsource (lib "Avery Altium Llibrary") (part "RCS040239K0FKED"))
    )
    (comp (ref "R143")
      (value "39K")
      (footprint "DEFAULT_RESISTOR_0402")
      (description "RES 39K OHM 1% 1/3W 0402")
      (fields (field (name "POWER") "1/3W") (field (name "TOLERANCE") "1%"))
      (libsource (lib "Avery Altium Llibrary") (part "RCS040239K0FKED"))
    )
    (comp (ref "R144")
      (value "39K")
      (footprint "DEFAULT_RESISTOR_0402")
      (description "RES 39K OHM 1% 1/3W 0402")
      (fields (field (name "POWER") "1/3W") (field (name "TOLERANCE") "1%"))
      (libsource (lib "Avery Altium Llibrary") (part "RCS040239K0FKED"))
    )
    (comp (ref "R145")
      (value "39K")
      (footprint "DEFAULT_RESISTOR_0402")
      (description "RES 39K OHM 1% 1/3W 0402")
      (fields (field (name "POWER") "1/3W") (field (name "TOLERANCE") "1%"))
      (libsource (lib "Avery Altium Llibrary") (part "RCS040239K0FKED"))
    )
    (comp (ref "R146")
      (value "39K")
      (footprint "DEFAULT_RESISTOR_0402")
      (description "RES 39K OHM 1% 1/3W 0402")
      (fields (field (name "POWER") "1/3W") (field (name "TOLERANCE") "1%"))
      (libsource (lib "Avery Altium Llibrary") (part "RCS040239K0FKED"))
    )
    (comp (ref "R147")
      (value "39K")
      (footprint "DEFAULT_RESISTOR_0402")
      (description "RES 39K OHM 1% 1/3W 0402")
      (fields (field (name "POWER") "1/3W") (field (name "TOLERANCE") "1%"))
      (libsource (lib "Avery Altium Llibrary") (part "RCS040239K0FKED"))
    )
    (comp (ref "R148")
      (value "39K")
      (footprint "DEFAULT_RESISTOR_0402")
      (description "RES 39K OHM 1% 1/3W 0402")
      (fields (field (name "POWER") "1/3W") (field (name "TOLERANCE") "1%"))
      (libsource (lib "Avery Altium Llibrary") (part "RCS040239K0FKED"))
    )
    (comp (ref "R149")
      (value "39K")
      (footprint "DEFAULT_RESISTOR_0402")
      (description "RES 39K OHM 1% 1/3W 0402")
      (fields (field (name "POWER") "1/3W") (field (name "TOLERANCE") "1%"))
      (libsource (lib "Avery Altium Llibrary") (part "RCS040239K0FKED"))
    )
    (comp (ref "R150")
      (value "39K")
      (footprint "DEFAULT_RESISTOR_0402")
      (description "RES 39K OHM 1% 1/3W 0402")
      (fields (field (name "POWER") "1/3W") (field (name "TOLERANCE") "1%"))
      (libsource (lib "Avery Altium Llibrary") (part "RCS040239K0FKED"))
    )
    (comp (ref "R151")
      (value "39K")
      (footprint "DEFAULT_RESISTOR_0402")
      (description "RES 39K OHM 1% 1/3W 0402")
      (fields (field (name "POWER") "1/3W") (field (name "TOLERANCE") "1%"))
      (libsource (lib "Avery Altium Llibrary") (part "RCS040239K0FKED"))
    )
    (comp (ref "R152")
      (value "39K")
      (footprint "DEFAULT_RESISTOR_0402")
      (description "RES 39K OHM 1% 1/3W 0402")
      (fields (field (name "POWER") "1/3W") (field (name "TOLERANCE") "1%"))
      (libsource (lib "Avery Altium Llibrary") (part "RCS040239K0FKED"))
    )
    (comp (ref "R153")
      (value "39K")
      (footprint "DEFAULT_RESISTOR_0402")
      (description "RES 39K OHM 1% 1/3W 0402")
      (fields (field (name "POWER") "1/3W") (field (name "TOLERANCE") "1%"))
      (libsource (lib "Avery Altium Llibrary") (part "RCS040239K0FKED"))
    )
    (comp (ref "R154")
      (value "39K")
      (footprint "DEFAULT_RESISTOR_0402")
      (description "RES 39K OHM 1% 1/3W 0402")
      (fields (field (name "POWER") "1/3W") (field (name "TOLERANCE") "1%"))
      (libsource (lib "Avery Altium Llibrary") (part "RCS040239K0FKED"))
    )
    (comp (ref "R155")
      (value "39K")
      (footprint "DEFAULT_RESISTOR_0402")
      (description "RES 39K OHM 1% 1/3W 0402")
      (fields (field (name "POWER") "1/3W") (field (name "TOLERANCE") "1%"))
      (libsource (lib "Avery Altium Llibrary") (part "RCS040239K0FKED"))
    )
    (comp (ref "R156")
      (value "39K")
      (footprint "DEFAULT_RESISTOR_0402")
      (description "RES 39K OHM 1% 1/3W 0402")
      (fields (field (name "POWER") "1/3W") (field (name "TOLERANCE") "1%"))
      (libsource (lib "Avery Altium Llibrary") (part "RCS040239K0FKED"))
    )
    (comp (ref "R157")
      (value "39K")
      (footprint "DEFAULT_RESISTOR_0402")
      (description "RES 39K OHM 1% 1/3W 0402")
      (fields (field (name "POWER") "1/3W") (field (name "TOLERANCE") "1%"))
      (libsource (lib "Avery Altium Llibrary") (part "RCS040239K0FKED"))
    )
    (comp (ref "R158")
      (value "39K")
      (footprint "DEFAULT_RESISTOR_0402")
      (description "RES 39K OHM 1% 1/3W 0402")
      (fields (field (name "POWER") "1/3W") (field (name "TOLERANCE") "1%"))
      (libsource (lib "Avery Altium Llibrary") (part "RCS040239K0FKED"))
    )
    (comp (ref "R159")
      (value "39K")
      (footprint "DEFAULT_RESISTOR_0402")
      (description "RES 39K OHM 1% 1/3W 0402")
      (fields (field (name "POWER") "1/3W") (field (name "TOLERANCE") "1%"))
      (libsource (lib "Avery Altium Llibrary") (part "RCS040239K0FKED"))
    )
    (comp (ref "R160")
      (value "39K")
      (footprint "DEFAULT_RESISTOR_0402")
      (description "RES 39K OHM 1% 1/3W 0402")
      (fields (field (name "POWER") "1/3W") (field (name "TOLERANCE") "1%"))
      (libsource (lib "Avery Altium Llibrary") (part "RCS040239K0FKED"))
    )
    (comp (ref "R161")
      (value "39K")
      (footprint "DEFAULT_RESISTOR_0402")
      (description "RES 39K OHM 1% 1/3W 0402")
      (fields (field (name "POWER") "1/3W") (field (name "TOLERANCE") "1%"))
      (libsource (lib "Avery Altium Llibrary") (part "RCS040239K0FKED"))
    )
    (comp (ref "R162")
      (value "39K")
      (footprint "DEFAULT_RESISTOR_0402")
      (description "RES 39K OHM 1% 1/3W 0402")
      (fields (field (name "POWER") "1/3W") (field (name "TOLERANCE") "1%"))
      (libsource (lib "Avery Altium Llibrary") (part "RCS040239K0FKED"))
    )
    (comp (ref "R163")
      (value "39K")
      (footprint "DEFAULT_RESISTOR_0402")
      (description "RES 39K OHM 1% 1/3W 0402")
      (fields (field (name "POWER") "1/3W") (field (name "TOLERANCE") "1%"))
      (libsource (lib "Avery Altium Llibrary") (part "RCS040239K0FKED"))
    )
    (comp (ref "R164")
      (value "39K")
      (footprint "DEFAULT_RESISTOR_0402")
      (description "RES 39K OHM 1% 1/3W 0402")
      (fields (field (name "POWER") "1/3W") (field (name "TOLERANCE") "1%"))
      (libsource (lib "Avery Altium Llibrary") (part "RCS040239K0FKED"))
    )
    (comp (ref "R165")
      (value "39K")
      (footprint "DEFAULT_RESISTOR_0402")
      (description "RES 39K OHM 1% 1/3W 0402")
      (fields (field (name "POWER") "1/3W") (field (name "TOLERANCE") "1%"))
      (libsource (lib "Avery Altium Llibrary") (part "RCS040239K0FKED"))
    )
    (comp (ref "R166")
      (value "39K")
      (footprint "DEFAULT_RESISTOR_0402")
      (description "RES 39K OHM 1% 1/3W 0402")
      (fields (field (name "POWER") "1/3W") (field (name "TOLERANCE") "1%"))
      (libsource (lib "Avery Altium Llibrary") (part "RCS040239K0FKED"))
    )
    (comp (ref "R167")
      (value "39K")
      (footprint "DEFAULT_RESISTOR_0402")
      (description "RES 39K OHM 1% 1/3W 0402")
      (fields (field (name "POWER") "1/3W") (field (name "TOLERANCE") "1%"))
      (libsource (lib "Avery Altium Llibrary") (part "RCS040239K0FKED"))
    )
    (comp (ref "R168")
      (value "39K")
      (footprint "DEFAULT_RESISTOR_0402")
      (description "RES 39K OHM 1% 1/3W 0402")
      (fields (field (name "POWER") "1/3W") (field (name "TOLERANCE") "1%"))
      (libsource (lib "Avery Altium Llibrary") (part "RCS040239K0FKED"))
    )
    (comp (ref "R169")
      (value "39K")
      (footprint "DEFAULT_RESISTOR_0402")
      (description "RES 39K OHM 1% 1/3W 0402")
      (fields (field (name "POWER") "1/3W") (field (name "TOLERANCE") "1%"))
      (libsource (lib "Avery Altium Llibrary") (part "RCS040239K0FKED"))
    )
    (comp (ref "R170")
      (value "39K")
      (footprint "DEFAULT_RESISTOR_0402")
      (description "RES 39K OHM 1% 1/3W 0402")
      (fields (field (name "POWER") "1/3W") (field (name "TOLERANCE") "1%"))
      (libsource (lib "Avery Altium Llibrary") (part "RCS040239K0FKED"))
    )
    (comp (ref "R171")
      (value "39K")
      (footprint "DEFAULT_RESISTOR_0402")
      (description "RES 39K OHM 1% 1/3W 0402")
      (fields (field (name "POWER") "1/3W") (field (name "TOLERANCE") "1%"))
      (libsource (lib "Avery Altium Llibrary") (part "RCS040239K0FKED"))
    )
    (comp (ref "R172")
      (value "39K")
      (footprint "DEFAULT_RESISTOR_0402")
      (description "RES 39K OHM 1% 1/3W 0402")
      (fields (field (name "POWER") "1/3W") (field (name "TOLERANCE") "1%"))
      (libsource (lib "Avery Altium Llibrary") (part "RCS040239K0FKED"))
    )
    (comp (ref "R173")
      (value "39K")
      (footprint "DEFAULT_RESISTOR_0402")
      (description "RES 39K OHM 1% 1/3W 0402")
      (fields (field (name "POWER") "1/3W") (field (name "TOLERANCE") "1%"))
      (libsource (lib "Avery Altium Llibrary") (part "RCS040239K0FKED"))
    )
    (comp (ref "R174")
      (value "39K")
      (footprint "DEFAULT_RESISTOR_0402")
      (description "RES 39K OHM 1% 1/3W 0402")
      (fields (field (name "POWER") "1/3W") (field (name "TOLERANCE") "1%"))
      (libsource (lib "Avery Altium Llibrary") (part "RCS040239K0FKED"))
    )
    (comp (ref "R175")
      (value "39K")
      (footprint "DEFAULT_RESISTOR_0402")
      (description "RES 39K OHM 1% 1/3W 0402")
      (fields (field (name "POWER") "1/3W") (field (name "TOLERANCE") "1%"))
      (libsource (lib "Avery Altium Llibrary") (part "RCS040239K0FKED"))
    )
    (comp (ref "R176")
      (value "39K")
      (footprint "DEFAULT_RESISTOR_0402")
      (description "RES 39K OHM 1% 1/3W 0402")
      (fields (field (name "POWER") "1/3W") (field (name "TOLERANCE") "1%"))
      (libsource (lib "Avery Altium Llibrary") (part "RCS040239K0FKED"))
    )
    (comp (ref "R177")
      (value "39K")
      (footprint "DEFAULT_RESISTOR_0402")
      (description "RES 39K OHM 1% 1/3W 0402")
      (fields (field (name "POWER") "1/3W") (field (name "TOLERANCE") "1%"))
      (libsource (lib "Avery Altium Llibrary") (part "RCS040239K0FKED"))
    )
    (comp (ref "R178")
      (value "39K")
      (footprint "DEFAULT_RESISTOR_0402")
      (description "RES 39K OHM 1% 1/3W 0402")
      (fields (field (name "POWER") "1/3W") (field (name "TOLERANCE") "1%"))
      (libsource (lib "Avery Altium Llibrary") (part "RCS040239K0FKED"))
    )
    (comp (ref "R179")
      (value "39K")
      (footprint "DEFAULT_RESISTOR_0402")
      (description "RES 39K OHM 1% 1/3W 0402")
      (fields (field (name "POWER") "1/3W") (field (name "TOLERANCE") "1%"))
      (libsource (lib "Avery Altium Llibrary") (part "RCS040239K0FKED"))
    )
    (comp (ref "R180")
      (value "39K")
      (footprint "DEFAULT_RESISTOR_0402")
      (description "RES 39K OHM 1% 1/3W 0402")
      (fields (field (name "POWER") "1/3W") (field (name "TOLERANCE") "1%"))
      (libsource (lib "Avery Altium Llibrary") (part "RCS040239K0FKED"))
    )
    (comp (ref "R181")
      (value "39K")
      (footprint "DEFAULT_RESISTOR_0402")
      (description "RES 39K OHM 1% 1/3W 0402")
      (fields (field (name "POWER") "1/3W") (field (name "TOLERANCE") "1%"))
      (libsource (lib "Avery Altium Llibrary") (part "RCS040239K0FKED"))
    )
    (comp (ref "R182")
      (value "39K")
      (footprint "DEFAULT_RESISTOR_0402")
      (description "RES 39K OHM 1% 1/3W 0402")
      (fields (field (name "POWER") "1/3W") (field (name "TOLERANCE") "1%"))
      (libsource (lib "Avery Altium Llibrary") (part "RCS040239K0FKED"))
    )
    (comp (ref "R183")
      (value "39K")
      (footprint "DEFAULT_RESISTOR_0402")
      (description "RES 39K OHM 1% 1/3W 0402")
      (fields (field (name "POWER") "1/3W") (field (name "TOLERANCE") "1%"))
      (libsource (lib "Avery Altium Llibrary") (part "RCS040239K0FKED"))
    )
    (comp (ref "R184")
      (value "39K")
      (footprint "DEFAULT_RESISTOR_0402")
      (description "RES 39K OHM 1% 1/3W 0402")
      (fields (field (name "POWER") "1/3W") (field (name "TOLERANCE") "1%"))
      (libsource (lib "Avery Altium Llibrary") (part "RCS040239K0FKED"))
    )
    (comp (ref "R185")
      (value "39K")
      (footprint "DEFAULT_RESISTOR_0402")
      (description "RES 39K OHM 1% 1/3W 0402")
      (fields (field (name "POWER") "1/3W") (field (name "TOLERANCE") "1%"))
      (libsource (lib "Avery Altium Llibrary") (part "RCS040239K0FKED"))
    )
    (comp (ref "R186")
      (value "39K")
      (footprint "DEFAULT_RESISTOR_0402")
      (description "RES 39K OHM 1% 1/3W 0402")
      (fields (field (name "POWER") "1/3W") (field (name "TOLERANCE") "1%"))
      (libsource (lib "Avery Altium Llibrary") (part "RCS040239K0FKED"))
    )
    (comp (ref "R187")
      (value "39K")
      (footprint "DEFAULT_RESISTOR_0402")
      (description "RES 39K OHM 1% 1/3W 0402")
      (fields (field (name "POWER") "1/3W") (field (name "TOLERANCE") "1%"))
      (libsource (lib "Avery Altium Llibrary") (part "RCS040239K0FKED"))
    )
    (comp (ref "R188")
      (value "39K")
      (footprint "DEFAULT_RESISTOR_0402")
      (description "RES 39K OHM 1% 1/3W 0402")
      (fields (field (name "POWER") "1/3W") (field (name "TOLERANCE") "1%"))
      (libsource (lib "Avery Altium Llibrary") (part "RCS040239K0FKED"))
    )
    (comp (ref "R189")
      (value "39K")
      (footprint "DEFAULT_RESISTOR_0402")
      (description "RES 39K OHM 1% 1/3W 0402")
      (fields (field (name "POWER") "1/3W") (field (name "TOLERANCE") "1%"))
      (libsource (lib "Avery Altium Llibrary") (part "RCS040239K0FKED"))
    )
    (comp (ref "R190")
      (value "39K")
      (footprint "DEFAULT_RESISTOR_0402")
      (description "RES 39K OHM 1% 1/3W 0402")
      (fields (field (name "POWER") "1/3W") (field (name "TOLERANCE") "1%"))
      (libsource (lib "Avery Altium Llibrary") (part "RCS040239K0FKED"))
    )
    (comp (ref "R191")
      (value "39K")
      (footprint "DEFAULT_RESISTOR_0402")
      (description "RES 39K OHM 1% 1/3W 0402")
      (fields (field (name "POWER") "1/3W") (field (name "TOLERANCE") "1%"))
      (libsource (lib "Avery Altium Llibrary") (part "RCS040239K0FKED"))
    )
    (comp (ref "R192")
      (value "39K")
      (footprint "DEFAULT_RESISTOR_0402")
      (description "RES 39K OHM 1% 1/3W 0402")
      (fields (field (name "POWER") "1/3W") (field (name "TOLERANCE") "1%"))
      (libsource (lib "Avery Altium Llibrary") (part "RCS040239K0FKED"))
    )
    (comp (ref "R193")
      (value "39K")
      (footprint "DEFAULT_RESISTOR_0402")
      (description "RES 39K OHM 1% 1/3W 0402")
      (fields (field (name "POWER") "1/3W") (field (name "TOLERANCE") "1%"))
      (libsource (lib "Avery Altium Llibrary") (part "RCS040239K0FKED"))
    )
    (comp (ref "R194")
      (value "39K")
      (footprint "DEFAULT_RESISTOR_0402")
      (description "RES 39K OHM 1% 1/3W 0402")
      (fields (field (name "POWER") "1/3W") (field (name "TOLERANCE") "1%"))
      (libsource (lib "Avery Altium Llibrary") (part "RCS040239K0FKED"))
    )
    (comp (ref "R195")
      (value "39K")
      (footprint "DEFAULT_RESISTOR_0402")
      (description "RES 39K OHM 1% 1/3W 0402")
      (fields (field (name "POWER") "1/3W") (field (name "TOLERANCE") "1%"))
      (libsource (lib "Avery Altium Llibrary") (part "RCS040239K0FKED"))
    )
    (comp (ref "R196")
      (value "39K")
      (footprint "DEFAULT_RESISTOR_0402")
      (description "RES 39K OHM 1% 1/3W 0402")
      (fields (field (name "POWER") "1/3W") (field (name "TOLERANCE") "1%"))
      (libsource (lib "Avery Altium Llibrary") (part "RCS040239K0FKED"))
    )
    (comp (ref "R197")
      (value "39K")
      (footprint "DEFAULT_RESISTOR_0402")
      (description "RES 39K OHM 1% 1/3W 0402")
      (fields (field (name "POWER") "1/3W") (field (name "TOLERANCE") "1%"))
      (libsource (lib "Avery Altium Llibrary") (part "RCS040239K0FKED"))
    )
    (comp (ref "R198")
      (value "39K")
      (footprint "DEFAULT_RESISTOR_0402")
      (description "RES 39K OHM 1% 1/3W 0402")
      (fields (field (name "POWER") "1/3W") (field (name "TOLERANCE") "1%"))
      (libsource (lib "Avery Altium Llibrary") (part "RCS040239K0FKED"))
    )
    (comp (ref "R199")
      (value "39K")
      (footprint "DEFAULT_RESISTOR_0402")
      (description "RES 39K OHM 1% 1/3W 0402")
      (fields (field (name "POWER") "1/3W") (field (name "TOLERANCE") "1%"))
      (libsource (lib "Avery Altium Llibrary") (part "RCS040239K0FKED"))
    )
    (comp (ref "R200")
      (value "39K")
      (footprint "DEFAULT_RESISTOR_0402")
      (description "RES 39K OHM 1% 1/3W 0402")
      (fields (field (name "POWER") "1/3W") (field (name "TOLERANCE") "1%"))
      (libsource (lib "Avery Altium Llibrary") (part "RCS040239K0FKED"))
    )
    (comp (ref "R201")
      (value "39K")
      (footprint "DEFAULT_RESISTOR_0402")
      (description "RES 39K OHM 1% 1/3W 0402")
      (fields (field (name "POWER") "1/3W") (field (name "TOLERANCE") "1%"))
      (libsource (lib "Avery Altium Llibrary") (part "RCS040239K0FKED"))
    )
    (comp (ref "R202")
      (value "39K")
      (footprint "DEFAULT_RESISTOR_0402")
      (description "RES 39K OHM 1% 1/3W 0402")
      (fields (field (name "POWER") "1/3W") (field (name "TOLERANCE") "1%"))
      (libsource (lib "Avery Altium Llibrary") (part "RCS040239K0FKED"))
    )
    (comp (ref "R203")
      (value "39K")
      (footprint "DEFAULT_RESISTOR_0402")
      (description "RES 39K OHM 1% 1/3W 0402")
      (fields (field (name "POWER") "1/3W") (field (name "TOLERANCE") "1%"))
      (libsource (lib "Avery Altium Llibrary") (part "RCS040239K0FKED"))
    )
    (comp (ref "R204")
      (value "39K")
      (footprint "DEFAULT_RESISTOR_0402")
      (description "RES 39K OHM 1% 1/3W 0402")
      (fields (field (name "POWER") "1/3W") (field (name "TOLERANCE") "1%"))
      (libsource (lib "Avery Altium Llibrary") (part "RCS040239K0FKED"))
    )
    (comp (ref "R205")
      (value "39K")
      (footprint "DEFAULT_RESISTOR_0402")
      (description "RES 39K OHM 1% 1/3W 0402")
      (fields (field (name "POWER") "1/3W") (field (name "TOLERANCE") "1%"))
      (libsource (lib "Avery Altium Llibrary") (part "RCS040239K0FKED"))
    )
    (comp (ref "R206")
      (value "39K")
      (footprint "DEFAULT_RESISTOR_0402")
      (description "RES 39K OHM 1% 1/3W 0402")
      (fields (field (name "POWER") "1/3W") (field (name "TOLERANCE") "1%"))
      (libsource (lib "Avery Altium Llibrary") (part "RCS040239K0FKED"))
    )
    (comp (ref "R207")
      (value "39K")
      (footprint "DEFAULT_RESISTOR_0402")
      (description "RES 39K OHM 1% 1/3W 0402")
      (fields (field (name "POWER") "1/3W") (field (name "TOLERANCE") "1%"))
      (libsource (lib "Avery Altium Llibrary") (part "RCS040239K0FKED"))
    )
    (comp (ref "R208")
      (value "39K")
      (footprint "DEFAULT_RESISTOR_0402")
      (description "RES 39K OHM 1% 1/3W 0402")
      (fields (field (name "POWER") "1/3W") (field (name "TOLERANCE") "1%"))
      (libsource (lib "Avery Altium Llibrary") (part "RCS040239K0FKED"))
    )
    (comp (ref "R209")
      (value "39K")
      (footprint "DEFAULT_RESISTOR_0402")
      (description "RES 39K OHM 1% 1/3W 0402")
      (fields (field (name "POWER") "1/3W") (field (name "TOLERANCE") "1%"))
      (libsource (lib "Avery Altium Llibrary") (part "RCS040239K0FKED"))
    )
    (comp (ref "R210")
      (value "39K")
      (footprint "DEFAULT_RESISTOR_0402")
      (description "RES 39K OHM 1% 1/3W 0402")
      (fields (field (name "POWER") "1/3W") (field (name "TOLERANCE") "1%"))
      (libsource (lib "Avery Altium Llibrary") (part "RCS040239K0FKED"))
    )
    (comp (ref "R211")
      (value "39K")
      (footprint "DEFAULT_RESISTOR_0402")
      (description "RES 39K OHM 1% 1/3W 0402")
      (fields (field (name "POWER") "1/3W") (field (name "TOLERANCE") "1%"))
      (libsource (lib "Avery Altium Llibrary") (part "RCS040239K0FKED"))
    )
    (comp (ref "R212")
      (value "39K")
      (footprint "DEFAULT_RESISTOR_0402")
      (description "RES 39K OHM 1% 1/3W 0402")
      (fields (field (name "POWER") "1/3W") (field (name "TOLERANCE") "1%"))
      (libsource (lib "Avery Altium Llibrary") (part "RCS040239K0FKED"))
    )
    (comp (ref "R213")
      (value "39K")
      (footprint "DEFAULT_RESISTOR_0402")
      (description "RES 39K OHM 1% 1/3W 0402")
      (fields (field (name "POWER") "1/3W") (field (name "TOLERANCE") "1%"))
      (libsource (lib "Avery Altium Llibrary") (part "RCS040239K0FKED"))
    )
    (comp (ref "R214")
      (value "39K")
      (footprint "DEFAULT_RESISTOR_0402")
      (description "RES 39K OHM 1% 1/3W 0402")
      (fields (field (name "POWER") "1/3W") (field (name "TOLERANCE") "1%"))
      (libsource (lib "Avery Altium Llibrary") (part "RCS040239K0FKED"))
    )
    (comp (ref "R215")
      (value "39K")
      (footprint "DEFAULT_RESISTOR_0402")
      (description "RES 39K OHM 1% 1/3W 0402")
      (fields (field (name "POWER") "1/3W") (field (name "TOLERANCE") "1%"))
      (libsource (lib "Avery Altium Llibrary") (part "RCS040239K0FKED"))
    )
    (comp (ref "R216")
      (value "39K")
      (footprint "DEFAULT_RESISTOR_0402")
      (description "RES 39K OHM 1% 1/3W 0402")
      (fields (field (name "POWER") "1/3W") (field (name "TOLERANCE") "1%"))
      (libsource (lib "Avery Altium Llibrary") (part "RCS040239K0FKED"))
    )
    (comp (ref "R217")
      (value "39K")
      (footprint "DEFAULT_RESISTOR_0402")
      (description "RES 39K OHM 1% 1/3W 0402")
      (fields (field (name "POWER") "1/3W") (field (name "TOLERANCE") "1%"))
      (libsource (lib "Avery Altium Llibrary") (part "RCS040239K0FKED"))
    )
    (comp (ref "R218")
      (value "39K")
      (footprint "DEFAULT_RESISTOR_0402")
      (description "RES 39K OHM 1% 1/3W 0402")
      (fields (field (name "POWER") "1/3W") (field (name "TOLERANCE") "1%"))
      (libsource (lib "Avery Altium Llibrary") (part "RCS040239K0FKED"))
    )
    (comp (ref "R219")
      (value "39K")
      (footprint "DEFAULT_RESISTOR_0402")
      (description "RES 39K OHM 1% 1/3W 0402")
      (fields (field (name "POWER") "1/3W") (field (name "TOLERANCE") "1%"))
      (libsource (lib "Avery Altium Llibrary") (part "RCS040239K0FKED"))
    )
    (comp (ref "R220")
      (value "39K")
      (footprint "DEFAULT_RESISTOR_0402")
      (description "RES 39K OHM 1% 1/3W 0402")
      (fields (field (name "POWER") "1/3W") (field (name "TOLERANCE") "1%"))
      (libsource (lib "Avery Altium Llibrary") (part "RCS040239K0FKED"))
    )
    (comp (ref "R221")
      (value "39K")
      (footprint "DEFAULT_RESISTOR_0402")
      (description "RES 39K OHM 1% 1/3W 0402")
      (fields (field (name "POWER") "1/3W") (field (name "TOLERANCE") "1%"))
      (libsource (lib "Avery Altium Llibrary") (part "RCS040239K0FKED"))
    )
    (comp (ref "R222")
      (value "39K")
      (footprint "DEFAULT_RESISTOR_0402")
      (description "RES 39K OHM 1% 1/3W 0402")
      (fields (field (name "POWER") "1/3W") (field (name "TOLERANCE") "1%"))
      (libsource (lib "Avery Altium Llibrary") (part "RCS040239K0FKED"))
    )
    (comp (ref "R223")
      (value "39K")
      (footprint "DEFAULT_RESISTOR_0402")
      (description "RES 39K OHM 1% 1/3W 0402")
      (fields (field (name "POWER") "1/3W") (field (name "TOLERANCE") "1%"))
      (libsource (lib "Avery Altium Llibrary") (part "RCS040239K0FKED"))
    )
    (comp (ref "R224")
      (value "39K")
      (footprint "DEFAULT_RESISTOR_0402")
      (description "RES 39K OHM 1% 1/3W 0402")
      (fields (field (name "POWER") "1/3W") (field (name "TOLERANCE") "1%"))
      (libsource (lib "Avery Altium Llibrary") (part "RCS040239K0FKED"))
    )
    (comp (ref "R225")
      (value "39K")
      (footprint "DEFAULT_RESISTOR_0402")
      (description "RES 39K OHM 1% 1/3W 0402")
      (fields (field (name "POWER") "1/3W") (field (name "TOLERANCE") "1%"))
      (libsource (lib "Avery Altium Llibrary") (part "RCS040239K0FKED"))
    )
    (comp (ref "R226")
      (value "39K")
      (footprint "DEFAULT_RESISTOR_0402")
      (description "RES 39K OHM 1% 1/3W 0402")
      (fields (field (name "POWER") "1/3W") (field (name "TOLERANCE") "1%"))
      (libsource (lib "Avery Altium Llibrary") (part "RCS040239K0FKED"))
    )
    (comp (ref "R227")
      (value "39K")
      (footprint "DEFAULT_RESISTOR_0402")
      (description "RES 39K OHM 1% 1/3W 0402")
      (fields (field (name "POWER") "1/3W") (field (name "TOLERANCE") "1%"))
      (libsource (lib "Avery Altium Llibrary") (part "RCS040239K0FKED"))
    )
    (comp (ref "R228")
      (value "39K")
      (footprint "DEFAULT_RESISTOR_0402")
      (description "RES 39K OHM 1% 1/3W 0402")
      (fields (field (name "POWER") "1/3W") (field (name "TOLERANCE") "1%"))
      (libsource (lib "Avery Altium Llibrary") (part "RCS040239K0FKED"))
    )
    (comp (ref "R229")
      (value "39K")
      (footprint "DEFAULT_RESISTOR_0402")
      (description "RES 39K OHM 1% 1/3W 0402")
      (fields (field (name "POWER") "1/3W") (field (name "TOLERANCE") "1%"))
      (libsource (lib "Avery Altium Llibrary") (part "RCS040239K0FKED"))
    )
    (comp (ref "R230")
      (value "39K")
      (footprint "DEFAULT_RESISTOR_0402")
      (description "RES 39K OHM 1% 1/3W 0402")
      (fields (field (name "POWER") "1/3W") (field (name "TOLERANCE") "1%"))
      (libsource (lib "Avery Altium Llibrary") (part "RCS040239K0FKED"))
    )
    (comp (ref "R231")
      (value "39K")
      (footprint "DEFAULT_RESISTOR_0402")
      (description "RES 39K OHM 1% 1/3W 0402")
      (fields (field (name "POWER") "1/3W") (field (name "TOLERANCE") "1%"))
      (libsource (lib "Avery Altium Llibrary") (part "RCS040239K0FKED"))
    )
    (comp (ref "R232")
      (value "39K")
      (footprint "DEFAULT_RESISTOR_0402")
      (description "RES 39K OHM 1% 1/3W 0402")
      (fields (field (name "POWER") "1/3W") (field (name "TOLERANCE") "1%"))
      (libsource (lib "Avery Altium Llibrary") (part "RCS040239K0FKED"))
    )
    (comp (ref "R233")
      (value "39K")
      (footprint "DEFAULT_RESISTOR_0402")
      (description "RES 39K OHM 1% 1/3W 0402")
      (fields (field (name "POWER") "1/3W") (field (name "TOLERANCE") "1%"))
      (libsource (lib "Avery Altium Llibrary") (part "RCS040239K0FKED"))
    )
    (comp (ref "R234")
      (value "39K")
      (footprint "DEFAULT_RESISTOR_0402")
      (description "RES 39K OHM 1% 1/3W 0402")
      (fields (field (name "POWER") "1/3W") (field (name "TOLERANCE") "1%"))
      (libsource (lib "Avery Altium Llibrary") (part "RCS040239K0FKED"))
    )
    (comp (ref "R235")
      (value "39K")
      (footprint "DEFAULT_RESISTOR_0402")
      (description "RES 39K OHM 1% 1/3W 0402")
      (fields (field (name "POWER") "1/3W") (field (name "TOLERANCE") "1%"))
      (libsource (lib "Avery Altium Llibrary") (part "RCS040239K0FKED"))
    )
    (comp (ref "R236")
      (value "39K")
      (footprint "DEFAULT_RESISTOR_0402")
      (description "RES 39K OHM 1% 1/3W 0402")
      (fields (field (name "POWER") "1/3W") (field (name "TOLERANCE") "1%"))
      (libsource (lib "Avery Altium Llibrary") (part "RCS040239K0FKED"))
    )
    (comp (ref "R237")
      (value "39K")
      (footprint "DEFAULT_RESISTOR_0402")
      (description "RES 39K OHM 1% 1/3W 0402")
      (fields (field (name "POWER") "1/3W") (field (name "TOLERANCE") "1%"))
      (libsource (lib "Avery Altium Llibrary") (part "RCS040239K0FKED"))
    )
    (comp (ref "R238")
      (value "39K")
      (footprint "DEFAULT_RESISTOR_0402")
      (description "RES 39K OHM 1% 1/3W 0402")
      (fields (field (name "POWER") "1/3W") (field (name "TOLERANCE") "1%"))
      (libsource (lib "Avery Altium Llibrary") (part "RCS040239K0FKED"))
    )
    (comp (ref "R239")
      (value "39K")
      (footprint "DEFAULT_RESISTOR_0402")
      (description "RES 39K OHM 1% 1/3W 0402")
      (fields (field (name "POWER") "1/3W") (field (name "TOLERANCE") "1%"))
      (libsource (lib "Avery Altium Llibrary") (part "RCS040239K0FKED"))
    )
    (comp (ref "R240")
      (value "39K")
      (footprint "DEFAULT_RESISTOR_0402")
      (description "RES 39K OHM 1% 1/3W 0402")
      (fields (field (name "POWER") "1/3W") (field (name "TOLERANCE") "1%"))
      (libsource (lib "Avery Altium Llibrary") (part "RCS040239K0FKED"))
    )
    (comp (ref "R241")
      (value "39K")
      (footprint "DEFAULT_RESISTOR_0402")
      (description "RES 39K OHM 1% 1/3W 0402")
      (fields (field (name "POWER") "1/3W") (field (name "TOLERANCE") "1%"))
      (libsource (lib "Avery Altium Llibrary") (part "RCS040239K0FKED"))
    )
    (comp (ref "R242")
      (value "39K")
      (footprint "DEFAULT_RESISTOR_0402")
      (description "RES 39K OHM 1% 1/3W 0402")
      (fields (field (name "POWER") "1/3W") (field (name "TOLERANCE") "1%"))
      (libsource (lib "Avery Altium Llibrary") (part "RCS040239K0FKED"))
    )
    (comp (ref "R243")
      (value "39K")
      (footprint "DEFAULT_RESISTOR_0402")
      (description "RES 39K OHM 1% 1/3W 0402")
      (fields (field (name "POWER") "1/3W") (field (name "TOLERANCE") "1%"))
      (libsource (lib "Avery Altium Llibrary") (part "RCS040239K0FKED"))
    )
    (comp (ref "R244")
      (value "39K")
      (footprint "DEFAULT_RESISTOR_0402")
      (description "RES 39K OHM 1% 1/3W 0402")
      (fields (field (name "POWER") "1/3W") (field (name "TOLERANCE") "1%"))
      (libsource (lib "Avery Altium Llibrary") (part "RCS040239K0FKED"))
    )
    (comp (ref "R245")
      (value "39K")
      (footprint "DEFAULT_RESISTOR_0402")
      (description "RES 39K OHM 1% 1/3W 0402")
      (fields (field (name "POWER") "1/3W") (field (name "TOLERANCE") "1%"))
      (libsource (lib "Avery Altium Llibrary") (part "RCS040239K0FKED"))
    )
    (comp (ref "R246")
      (value "39K")
      (footprint "DEFAULT_RESISTOR_0402")
      (description "RES 39K OHM 1% 1/3W 0402")
      (fields (field (name "POWER") "1/3W") (field (name "TOLERANCE") "1%"))
      (libsource (lib "Avery Altium Llibrary") (part "RCS040239K0FKED"))
    )
    (comp (ref "R247")
      (value "39K")
      (footprint "DEFAULT_RESISTOR_0402")
      (description "RES 39K OHM 1% 1/3W 0402")
      (fields (field (name "POWER") "1/3W") (field (name "TOLERANCE") "1%"))
      (libsource (lib "Avery Altium Llibrary") (part "RCS040239K0FKED"))
    )
    (comp (ref "R248")
      (value "39K")
      (footprint "DEFAULT_RESISTOR_0402")
      (description "RES 39K OHM 1% 1/3W 0402")
      (fields (field (name "POWER") "1/3W") (field (name "TOLERANCE") "1%"))
      (libsource (lib "Avery Altium Llibrary") (part "RCS040239K0FKED"))
    )
    (comp (ref "R249")
      (value "39K")
      (footprint "DEFAULT_RESISTOR_0402")
      (description "RES 39K OHM 1% 1/3W 0402")
      (fields (field (name "POWER") "1/3W") (field (name "TOLERANCE") "1%"))
      (libsource (lib "Avery Altium Llibrary") (part "RCS040239K0FKED"))
    )
    (comp (ref "R250")
      (value "39K")
      (footprint "DEFAULT_RESISTOR_0402")
      (description "RES 39K OHM 1% 1/3W 0402")
      (fields (field (name "POWER") "1/3W") (field (name "TOLERANCE") "1%"))
      (libsource (lib "Avery Altium Llibrary") (part "RCS040239K0FKED"))
    )
    (comp (ref "R251")
      (value "39K")
      (footprint "DEFAULT_RESISTOR_0402")
      (description "RES 39K OHM 1% 1/3W 0402")
      (fields (field (name "POWER") "1/3W") (field (name "TOLERANCE") "1%"))
      (libsource (lib "Avery Altium Llibrary") (part "RCS040239K0FKED"))
    )
    (comp (ref "R252")
      (value "39K")
      (footprint "DEFAULT_RESISTOR_0402")
      (description "RES 39K OHM 1% 1/3W 0402")
      (fields (field (name "POWER") "1/3W") (field (name "TOLERANCE") "1%"))
      (libsource (lib "Avery Altium Llibrary") (part "RCS040239K0FKED"))
    )
    (comp (ref "R253")
      (value "39K")
      (footprint "DEFAULT_RESISTOR_0402")
      (description "RES 39K OHM 1% 1/3W 0402")
      (fields (field (name "POWER") "1/3W") (field (name "TOLERANCE") "1%"))
      (libsource (lib "Avery Altium Llibrary") (part "RCS040239K0FKED"))
    )
    (comp (ref "R254")
      (value "39K")
      (footprint "DEFAULT_RESISTOR_0402")
      (description "RES 39K OHM 1% 1/3W 0402")
      (fields (field (name "POWER") "1/3W") (field (name "TOLERANCE") "1%"))
      (libsource (lib "Avery Altium Llibrary") (part "RCS040239K0FKED"))
    )
    (comp (ref "R255")
      (value "39K")
      (footprint "DEFAULT_RESISTOR_0402")
      (description "RES 39K OHM 1% 1/3W 0402")
      (fields (field (name "POWER") "1/3W") (field (name "TOLERANCE") "1%"))
      (libsource (lib "Avery Altium Llibrary") (part "RCS040239K0FKED"))
    )
    (comp (ref "R256")
      (value "39K")
      (footprint "DEFAULT_RESISTOR_0402")
      (description "RES 39K OHM 1% 1/3W 0402")
      (fields (field (name "POWER") "1/3W") (field (name "TOLERANCE") "1%"))
      (libsource (lib "Avery Altium Llibrary") (part "RCS040239K0FKED"))
    )
    (comp (ref "R257")
      (value "39K")
      (footprint "DEFAULT_RESISTOR_0402")
      (description "RES 39K OHM 1% 1/3W 0402")
      (fields (field (name "POWER") "1/3W") (field (name "TOLERANCE") "1%"))
      (libsource (lib "Avery Altium Llibrary") (part "RCS040239K0FKED"))
    )
    (comp (ref "R258")
      (value "39K")
      (footprint "DEFAULT_RESISTOR_0402")
      (description "RES 39K OHM 1% 1/3W 0402")
      (fields (field (name "POWER") "1/3W") (field (name "TOLERANCE") "1%"))
      (libsource (lib "Avery Altium Llibrary") (part "RCS040239K0FKED"))
    )
    (comp (ref "R259")
      (value "39K")
      (footprint "DEFAULT_RESISTOR_0402")
      (description "RES 39K OHM 1% 1/3W 0402")
      (fields (field (name "POWER") "1/3W") (field (name "TOLERANCE") "1%"))
      (libsource (lib "Avery Altium Llibrary") (part "RCS040239K0FKED"))
    )
    (comp (ref "R260")
      (value "39K")
      (footprint "DEFAULT_RESISTOR_0402")
      (description "RES 39K OHM 1% 1/3W 0402")
      (fields (field (name "POWER") "1/3W") (field (name "TOLERANCE") "1%"))
      (libsource (lib "Avery Altium Llibrary") (part "RCS040239K0FKED"))
    )
    (comp (ref "R261")
      (value "39K")
      (footprint "DEFAULT_RESISTOR_0402")
      (description "RES 39K OHM 1% 1/3W 0402")
      (fields (field (name "POWER") "1/3W") (field (name "TOLERANCE") "1%"))
      (libsource (lib "Avery Altium Llibrary") (part "RCS040239K0FKED"))
    )
    (comp (ref "R262")
      (value "39K")
      (footprint "DEFAULT_RESISTOR_0402")
      (description "RES 39K OHM 1% 1/3W 0402")
      (fields (field (name "POWER") "1/3W") (field (name "TOLERANCE") "1%"))
      (libsource (lib "Avery Altium Llibrary") (part "RCS040239K0FKED"))
    )
    (comp (ref "R263")
      (value "39K")
      (footprint "DEFAULT_RESISTOR_0402")
      (description "RES 39K OHM 1% 1/3W 0402")
      (fields (field (name "POWER") "1/3W") (field (name "TOLERANCE") "1%"))
      (libsource (lib "Avery Altium Llibrary") (part "RCS040239K0FKED"))
    )
    (comp (ref "R264")
      (value "39K")
      (footprint "DEFAULT_RESISTOR_0402")
      (description "RES 39K OHM 1% 1/3W 0402")
      (fields (field (name "POWER") "1/3W") (field (name "TOLERANCE") "1%"))
      (libsource (lib "Avery Altium Llibrary") (part "RCS040239K0FKED"))
    )
    (comp (ref "R265")
      (value "39K")
      (footprint "DEFAULT_RESISTOR_0402")
      (description "RES 39K OHM 1% 1/3W 0402")
      (fields (field (name "POWER") "1/3W") (field (name "TOLERANCE") "1%"))
      (libsource (lib "Avery Altium Llibrary") (part "RCS040239K0FKED"))
    )
    (comp (ref "R266")
      (value "39K")
      (footprint "DEFAULT_RESISTOR_0402")
      (description "RES 39K OHM 1% 1/3W 0402")
      (fields (field (name "POWER") "1/3W") (field (name "TOLERANCE") "1%"))
      (libsource (lib "Avery Altium Llibrary") (part "RCS040239K0FKED"))
    )
    (comp (ref "R267")
      (value "39K")
      (footprint "DEFAULT_RESISTOR_0402")
      (description "RES 39K OHM 1% 1/3W 0402")
      (fields (field (name "POWER") "1/3W") (field (name "TOLERANCE") "1%"))
      (libsource (lib "Avery Altium Llibrary") (part "RCS040239K0FKED"))
    )
    (comp (ref "R268")
      (value "39K")
      (footprint "DEFAULT_RESISTOR_0402")
      (description "RES 39K OHM 1% 1/3W 0402")
      (fields (field (name "POWER") "1/3W") (field (name "TOLERANCE") "1%"))
      (libsource (lib "Avery Altium Llibrary") (part "RCS040239K0FKED"))
    )
    (comp (ref "R269")
      (value "39K")
      (footprint "DEFAULT_RESISTOR_0402")
      (description "RES 39K OHM 1% 1/3W 0402")
      (fields (field (name "POWER") "1/3W") (field (name "TOLERANCE") "1%"))
      (libsource (lib "Avery Altium Llibrary") (part "RCS040239K0FKED"))
    )
    (comp (ref "R270")
      (value "39K")
      (footprint "DEFAULT_RESISTOR_0402")
      (description "RES 39K OHM 1% 1/3W 0402")
      (fields (field (name "POWER") "1/3W") (field (name "TOLERANCE") "1%"))
      (libsource (lib "Avery Altium Llibrary") (part "RCS040239K0FKED"))
    )
    (comp (ref "R271")
      (value "39K")
      (footprint "DEFAULT_RESISTOR_0402")
      (description "RES 39K OHM 1% 1/3W 0402")
      (fields (field (name "POWER") "1/3W") (field (name "TOLERANCE") "1%"))
      (libsource (lib "Avery Altium Llibrary") (part "RCS040239K0FKED"))
    )
    (comp (ref "R272")
      (value "39K")
      (footprint "DEFAULT_RESISTOR_0402")
      (description "RES 39K OHM 1% 1/3W 0402")
      (fields (field (name "POWER") "1/3W") (field (name "TOLERANCE") "1%"))
      (libsource (lib "Avery Altium Llibrary") (part "RCS040239K0FKED"))
    )
    (comp (ref "R273")
      (value "39K")
      (footprint "DEFAULT_RESISTOR_0402")
      (description "RES 39K OHM 1% 1/3W 0402")
      (fields (field (name "POWER") "1/3W") (field (name "TOLERANCE") "1%"))
      (libsource (lib "Avery Altium Llibrary") (part "RCS040239K0FKED"))
    )
    (comp (ref "R274")
      (value "39K")
      (footprint "DEFAULT_RESISTOR_0402")
      (description "RES 39K OHM 1% 1/3W 0402")
      (fields (field (name "POWER") "1/3W") (field (name "TOLERANCE") "1%"))
      (libsource (lib "Avery Altium Llibrary") (part "RCS040239K0FKED"))
    )
    (comp (ref "R275")
      (value "39K")
      (footprint "DEFAULT_RESISTOR_0402")
      (description "RES 39K OHM 1% 1/3W 0402")
      (fields (field (name "POWER") "1/3W") (field (name "TOLERANCE") "1%"))
      (libsource (lib "Avery Altium Llibrary") (part "RCS040239K0FKED"))
    )
    (comp (ref "R276")
      (value "39K")
      (footprint "DEFAULT_RESISTOR_0402")
      (description "RES 39K OHM 1% 1/3W 0402")
      (fields (field (name "POWER") "1/3W") (field (name "TOLERANCE") "1%"))
      (libsource (lib "Avery Altium Llibrary") (part "RCS040239K0FKED"))
    )
    (comp (ref "R277")
      (value "39K")
      (footprint "DEFAULT_RESISTOR_0402")
      (description "RES 39K OHM 1% 1/3W 0402")
      (fields (field (name "POWER") "1/3W") (field (name "TOLERANCE") "1%"))
      (libsource (lib "Avery Altium Llibrary") (part "RCS040239K0FKED"))
    )
    (comp (ref "R278")
      (value "39K")
      (footprint "DEFAULT_RESISTOR_0402")
      (description "RES 39K OHM 1% 1/3W 0402")
      (fields (field (name "POWER") "1/3W") (field (name "TOLERANCE") "1%"))
      (libsource (lib "Avery Altium Llibrary") (part "RCS040239K0FKED"))
    )
    (comp (ref "R279")
      (value "39K")
      (footprint "DEFAULT_RESISTOR_0402")
      (description "RES 39K OHM 1% 1/3W 0402")
      (fields (field (name "POWER") "1/3W") (field (name "TOLERANCE") "1%"))
      (libsource (lib "Avery Altium Llibrary") (part "RCS040239K0FKED"))
    )
    (comp (ref "R280")
      (value "39K")
      (footprint "DEFAULT_RESISTOR_0402")
      (description "RES 39K OHM 1% 1/3W 0402")
      (fields (field (name "POWER") "1/3W") (field (name "TOLERANCE") "1%"))
      (libsource (lib "Avery Altium Llibrary") (part "RCS040239K0FKED"))
    )
    (comp (ref "R281")
      (value "39K")
      (footprint "DEFAULT_RESISTOR_0402")
      (description "RES 39K OHM 1% 1/3W 0402")
      (fields (field (name "POWER") "1/3W") (field (name "TOLERANCE") "1%"))
      (libsource (lib "Avery Altium Llibrary") (part "RCS040239K0FKED"))
    )
    (comp (ref "R282")
      (value "39K")
      (footprint "DEFAULT_RESISTOR_0402")
      (description "RES 39K OHM 1% 1/3W 0402")
      (fields (field (name "POWER") "1/3W") (field (name "TOLERANCE") "1%"))
      (libsource (lib "Avery Altium Llibrary") (part "RCS040239K0FKED"))
    )
    (comp (ref "R283")
      (value "39K")
      (footprint "DEFAULT_RESISTOR_0402")
      (description "RES 39K OHM 1% 1/3W 0402")
      (fields (field (name "POWER") "1/3W") (field (name "TOLERANCE") "1%"))
      (libsource (lib "Avery Altium Llibrary") (part "RCS040239K0FKED"))
    )
    (comp (ref "R284")
      (value "39K")
      (footprint "DEFAULT_RESISTOR_0402")
      (description "RES 39K OHM 1% 1/3W 0402")
      (fields (field (name "POWER") "1/3W") (field (name "TOLERANCE") "1%"))
      (libsource (lib "Avery Altium Llibrary") (part "RCS040239K0FKED"))
    )
    (comp (ref "R285")
      (value "39K")
      (footprint "DEFAULT_RESISTOR_0402")
      (description "RES 39K OHM 1% 1/3W 0402")
      (fields (field (name "POWER") "1/3W") (field (name "TOLERANCE") "1%"))
      (libsource (lib "Avery Altium Llibrary") (part "RCS040239K0FKED"))
    )
    (comp (ref "R286")
      (value "39K")
      (footprint "DEFAULT_RESISTOR_0402")
      (description "RES 39K OHM 1% 1/3W 0402")
      (fields (field (name "POWER") "1/3W") (field (name "TOLERANCE") "1%"))
      (libsource (lib "Avery Altium Llibrary") (part "RCS040239K0FKED"))
    )
    (comp (ref "R287")
      (value "39K")
      (footprint "DEFAULT_RESISTOR_0402")
      (description "RES 39K OHM 1% 1/3W 0402")
      (fields (field (name "POWER") "1/3W") (field (name "TOLERANCE") "1%"))
      (libsource (lib "Avery Altium Llibrary") (part "RCS040239K0FKED"))
    )
    (comp (ref "R288")
      (value "39K")
      (footprint "DEFAULT_RESISTOR_0402")
      (description "RES 39K OHM 1% 1/3W 0402")
      (fields (field (name "POWER") "1/3W") (field (name "TOLERANCE") "1%"))
      (libsource (lib "Avery Altium Llibrary") (part "RCS040239K0FKED"))
    )
    (comp (ref "R289")
      (value "39K")
      (footprint "DEFAULT_RESISTOR_0402")
      (description "RES 39K OHM 1% 1/3W 0402")
      (fields (field (name "POWER") "1/3W") (field (name "TOLERANCE") "1%"))
      (libsource (lib "Avery Altium Llibrary") (part "RCS040239K0FKED"))
    )
    (comp (ref "R290")
      (value "39K")
      (footprint "DEFAULT_RESISTOR_0402")
      (description "RES 39K OHM 1% 1/3W 0402")
      (fields (field (name "POWER") "1/3W") (field (name "TOLERANCE") "1%"))
      (libsource (lib "Avery Altium Llibrary") (part "RCS040239K0FKED"))
    )
    (comp (ref "R291")
      (value "39K")
      (footprint "DEFAULT_RESISTOR_0402")
      (description "RES 39K OHM 1% 1/3W 0402")
      (fields (field (name "POWER") "1/3W") (field (name "TOLERANCE") "1%"))
      (libsource (lib "Avery Altium Llibrary") (part "RCS040239K0FKED"))
    )
    (comp (ref "R292")
      (value "39K")
      (footprint "DEFAULT_RESISTOR_0402")
      (description "RES 39K OHM 1% 1/3W 0402")
      (fields (field (name "POWER") "1/3W") (field (name "TOLERANCE") "1%"))
      (libsource (lib "Avery Altium Llibrary") (part "RCS040239K0FKED"))
    )
    (comp (ref "R293")
      (value "39K")
      (footprint "DEFAULT_RESISTOR_0402")
      (description "RES 39K OHM 1% 1/3W 0402")
      (fields (field (name "POWER") "1/3W") (field (name "TOLERANCE") "1%"))
      (libsource (lib "Avery Altium Llibrary") (part "RCS040239K0FKED"))
    )
    (comp (ref "R294")
      (value "39K")
      (footprint "DEFAULT_RESISTOR_0402")
      (description "RES 39K OHM 1% 1/3W 0402")
      (fields (field (name "POWER") "1/3W") (field (name "TOLERANCE") "1%"))
      (libsource (lib "Avery Altium Llibrary") (part "RCS040239K0FKED"))
    )
    (comp (ref "R295")
      (value "39K")
      (footprint "DEFAULT_RESISTOR_0402")
      (description "RES 39K OHM 1% 1/3W 0402")
      (fields (field (name "POWER") "1/3W") (field (name "TOLERANCE") "1%"))
      (libsource (lib "Avery Altium Llibrary") (part "RCS040239K0FKED"))
    )
    (comp (ref "R296")
      (value "39K")
      (footprint "DEFAULT_RESISTOR_0402")
      (description "RES 39K OHM 1% 1/3W 0402")
      (fields (field (name "POWER") "1/3W") (field (name "TOLERANCE") "1%"))
      (libsource (lib "Avery Altium Llibrary") (part "RCS040239K0FKED"))
    )
    (comp (ref "R297")
      (value "39K")
      (footprint "DEFAULT_RESISTOR_0402")
      (description "RES 39K OHM 1% 1/3W 0402")
      (fields (field (name "POWER") "1/3W") (field (name "TOLERANCE") "1%"))
      (libsource (lib "Avery Altium Llibrary") (part "RCS040239K0FKED"))
    )
    (comp (ref "R298")
      (value "39K")
      (footprint "DEFAULT_RESISTOR_0402")
      (description "RES 39K OHM 1% 1/3W 0402")
      (fields (field (name "POWER") "1/3W") (field (name "TOLERANCE") "1%"))
      (libsource (lib "Avery Altium Llibrary") (part "RCS040239K0FKED"))
    )
    (comp (ref "R299")
      (value "39K")
      (footprint "DEFAULT_RESISTOR_0402")
      (description "RES 39K OHM 1% 1/3W 0402")
      (fields (field (name "POWER") "1/3W") (field (name "TOLERANCE") "1%"))
      (libsource (lib "Avery Altium Llibrary") (part "RCS040239K0FKED"))
    )
    (comp (ref "R300")
      (value "39K")
      (footprint "DEFAULT_RESISTOR_0402")
      (description "RES 39K OHM 1% 1/3W 0402")
      (fields (field (name "POWER") "1/3W") (field (name "TOLERANCE") "1%"))
      (libsource (lib "Avery Altium Llibrary") (part "RCS040239K0FKED"))
    )
  )
  (nets
    (net (code "2") (name "GND") (class "Default")
      (node (ref "R1") (pin "2") (pinfunction "2_2") (pintype "passive"))
      (node (ref "R10") (pin "1") (pinfunction "1_1") (pintype "passive"))
      (node (ref "R100") (pin "1") (pinfunction "1_1") (pintype "passive"))
      (node (ref "R101") (pin "2") (pinfunction "2_2") (pintype "passive"))
      (node (ref "R102") (pin "1") (pinfunction "1_1") (pintype "passive"))
      (node (ref "R103") (pin "2") (pinfunction "2_2") (pintype "passive"))
      (node (ref "R104") (pin "1") (pinfunction "1_1") (pintype "passive"))
      (node (ref "R105") (pin "2") (pinfunction "2_2") (pintype "passive"))
      (node (ref "R106") (pin "1") (pinfunction "1_1") (pintype "passive"))
      (node (ref "R107") (pin "2") (pinfunction "2_2") (pintype "passive"))
      (node (ref "R108") (pin "1") (pinfunction "1_1") (pintype "passive"))
      (node (ref "R109") (pin "2") (pinfunction "2_2") (pintype "passive"))
      (node (ref "R11") (pin "2") (pinfunction "2_2") (pintype "passive"))
      (node (ref "R110") (pin "1") (pinfunction "1_1") (pintype "passive"))
      (node (ref "R111") (pin "2") (pinfunction "2_2") (pintype "passive"))
      (node (ref "R112") (pin "1") (pinfunction "1_1") (pintype "passive"))
      (node (ref "R113") (pin "2") (pinfunction "2_2") (pintype "passive"))
      (node (ref "R114") (pin "1") (pinfunction "1_1") (pintype "passive"))
      (node (ref "R115") (pin "2") (pinfunction "2_2") (pintype "passive"))
      (node (ref "R116") (pin "1") (pinfunction "1_1") (pintype "passive"))
      (node (ref "R117") (pin "2") (pinfunction "2_2") (pintype "passive"))
      (node (ref "R118") (pin "1") (pinfunction "1_1") (pintype "passive"))
      (node (ref "R119") (pin "2") (pinfunction "2_2") (pintype "passive"))
      (node (ref "R12") (pin "1") (pinfunction "1_1") (pintype "passive"))
      (node (ref "R120") (pin "1") (pinfunction "1_1") (pintype "passive"))
      (node (ref "R121") (pin "2") (pinfunction "2_2") (pintype "passive"))
      (node (ref "R122") (pin "1") (pinfunction "1_1") (pintype "passive"))
      (node (ref "R123") (pin "2") (pinfunction "2_2") (pintype "passive"))
      (node (ref "R124") (pin "1") (pinfunction "1_1") (pintype "passive"))
      (node (ref "R125") (pin "2") (pinfunction "2_2") (pintype "passive"))
      (node (ref "R126") (pin "1") (pinfunction "1_1") (pintype "passive"))
      (node (ref "R127") (pin "2") (pinfunction "2_2") (pintype "passive"))
      (node (ref "R128") (pin "1") (pinfunction "1_1") (pintype "passive"))
      (node (ref "R129") (pin "2") (pinfunction "2_2") (pintype "passive"))
      (node (ref "R13") (pin "2") (pinfunction "2_2") (pintype "passive"))
      (node (ref "R130") (pin "1") (pinfunction "1_1") (pintype "passive"))
      (node (ref "R131") (pin "2") (pinfunction "2_2") (pintype "passive"))
      (node (ref "R132") (pin "1") (pinfunction "1_1") (pintype "passive"))
      (node (ref "R133") (pin "2") (pinfunction "2_2") (pintype "passive"))
      (node (ref "R134") (pin "1") (pinfunction "1_1") (pintype "passive"))
      (node (ref "R135") (pin "2") (pinfunction "2_2") (pintype "passive"))
      (node (ref "R136") (pin "1") (pinfunction "1_1") (pintype "passive"))
      (node (ref "R137") (pin "2") (pinfunction "2_2") (pintype "passive"))
      (node (ref "R138") (pin "1") (pinfunction "1_1") (pintype "passive"))
      (node (ref "R139") (pin "2") (pinfunction "2_2") (pintype "passive"))
      (node (ref "R14") (pin "1") (pinfunction "1_1") (pintype "passive"))
      (node (ref "R140") (pin "1") (pinfunction "1_1") (pintype "passive"))
      (node (ref "R141") (pin "2") (pinfunction "2_2") (pintype "passive"))
      (node (ref "R142") (pin "1") (pinfunction "1_1") (pintype "passive"))
      (node (ref "R143") (pin "2") (pinfunction "2_2") (pintype "passive"))
      (node (ref "R144") (pin "1") (pinfunction "1_1") (pintype "passive"))
      (node (ref "R145") (pin "2") (pinfunction "2_2") (pintype "passive"))
      (node (ref "R146") (pin "1") (pinfunction "1_1") (pintype "passive"))
      (node (ref "R147") (pin "2") (pinfunction "2_2") (pintype "passive"))
      (node (ref "R148") (pin "1") (pinfunction "1_1") (pintype "passive"))
      (node (ref "R149") (pin "2") (pinfunction "2_2") (pintype "passive"))
      (node (ref "R15") (pin "2") (pinfunction "2_2") (pintype "passive"))
      (node (ref "R150") (pin "1") (pinfunction "1_1") (pintype "passive"))
      (node (ref "R151") (pin "2") (pinfunction "2_2") (pintype "passive"))
      (node (ref "R152") (pin "1") (pinfunction "1_1") (pintype "passive"))
      (node (ref "R153") (pin "2") (pinfunction "2_2") (pintype "passive"))
      (node (ref "R154") (pin "1") (pinfunction "1_1") (pintype "passive"))
      (node (ref "R155") (pin "2") (pinfunction "2_2") (pintype "passive"))
      (node (ref "R156") (pin "1") (pinfunction "1_1") (pintype "passive"))
      (node (ref "R157") (pin "2") (pinfunction "2_2") (pintype "passive"))
      (node (ref "R158") (pin "1") (pinfunction "1_1") (pintype "passive"))
      (node (ref "R159") (pin "2") (pinfunction "2_2") (pintype "passive"))
      (node (ref "R16") (pin "1") (pinfunction "1_1") (pintype "passive"))
      (node (ref "R160") (pin "1") (pinfunction "1_1") (pintype "passive"))
      (node (ref "R161") (pin "2") (pinfunction "2_2") (pintype "passive"))
      (node (ref "R162") (pin "1") (pinfunction "1_1") (pintype "passive"))
      (node (ref "R163") (pin "2") (pinfunction "2_2") (pintype "passive"))
      (node (ref "R164") (pin "1") (pinfunction "1_1") (pintype "passive"))
      (node (ref "R165") (pin "2") (pinfunction "2_2") (pintype "passive"))
      (node (ref "R166") (pin "1") (pinfunction "1_1") (pintype "passive"))
      (node (ref "R167") (pin "2") (pinfunction "2_2") (pintype "passive"))
      (node (ref "R168") (pin "1") (pinfunction "1_1") (pintype "passive"))
      (node (ref "R169") (pin "2") (pinfunction "2_2") (pintype "passive"))
      (node (ref "R17") (pin "2") (pinfunction "2_2") (pintype "passive"))
      (node (ref "R170") (pin "1") (pinfunction "1_1") (pintype "passive"))
      (node (ref "R171") (pin "2") (pinfunction "2_2") (pintype "passive"))
      (node (ref "R172") (pin "1") (pinfunction "1_1") (pintype "passive"))
      (node (ref "R173") (pin "2") (pinfunction "2_2") (pintype "passive"))
      (node (ref "R174") (pin "1") (pinfunction "1_1") (pintype "passive"))
      (node (ref "R175") (pin "2") (pinfunction "2_2") (pintype "passive"))
      (node (ref "R176") (pin "1") (pinfunction "1_1") (pintype "passive"))
      (node (ref "R177") (pin "2") (pinfunction "2_2") (pintype "passive"))
      (node (ref "R178") (pin "1") (pinfunction "1_1") (pintype "passive"))
      (node (ref "R179") (pin "2") (pinfunction "2_2") (pintype "passive"))
      (node (ref "R18") (pin "1") (pinfunction "1_1") (pintype "passive"))
      (node (ref "R180") (pin "1") (pinfunction "1_1") (pintype "passive"))
      (node (ref "R181") (pin "2") (pinfunction "2_2") (pintype "passive"))
      (node (ref "R182") (pin "1") (pinfunction "1_1") (pintype "passive"))
      (node (ref "R183") (pin "2") (pinfunction "2_2") (pintype "passive"))
      (node (ref "R184") (pin "1") (pinfunction "1_1") (pintype "passive"))
      (node (ref "R185") (pin "2") (pinfunction "2_2") (pintype "passive"))
      (node (ref "R186") (pin "1") (pinfunction "1_1") (pintype "passive"))
      (node (ref "R187") (pin "2") (pinfunction "2_2") (pintype "passive"))
      (node (ref "R188") (pin "1") (pinfunction "1_1") (pintype "passive"))
      (node (ref "R189") (pin "2") (pinfunction "2_2") (pintype "passive"))
      (node (ref "R19") (pin "2") (pinfunction "2_2") (pintype "passive"))
      (node (ref "R190") (pin "1") (pinfunction "1_1") (pintype "passive"))
      (node (ref "R191") (pin "2") (pinfunction "2_2") (pintype "passive"))
      (node (ref "R192") (pin "1") (pinfunction "1_1") (pintype "passive"))
      (node (ref "R193") (pin "2") (pinfunction "2_2") (pintype "passive"))
      (node (ref "R194") (pin "1") (pinfunction "1_1") (pintype "passive"))
      (node (ref "R195") (pin "2") (pinfunction "2_2") (pintype "passive"))
      (node (ref "R196") (pin "1") (pinfunction "1_1") (pintype "passive"))
      (node (ref "R197") (pin "2") (pinfunction "2_2") (pintype "passive"))
      (node (ref "R198") (pin "1") (pinfunction "1_1") (pintype "passive"))
      (node (ref "R199") (pin "2") (pinfunction "2_2") (pintype "passive"))
      (node (ref "R2") (pin "1") (pinfunction "1_1") (pintype "passive"))
      (node (ref "R20") (pin "1") (pinfunction "1_1") (pintype "passive"))
      (node (ref "R200") (pin "1") (pinfunction "1_1") (pintype "passive"))
      (node (ref "R201") (pin "2") (pinfunction "2_2") (pintype "passive"))
      (node (ref "R202") (pin "1") (pinfunction "1_1") (pintype "passive"))
      (node (ref "R203") (pin "2") (pinfunction "2_2") (pintype "passive"))
      (node (ref "R204") (pin "1") (pinfunction "1_1") (pintype "passive"))
      (node (ref "R205") (pin "2") (pinfunction "2_2") (pintype "passive"))
      (node (ref "R206") (pin "1") (pinfunction "1_1") (pintype "passive"))
      (node (ref "R207") (pin "2") (pinfunction "2_2") (pintype "passive"))
      (node (ref "R208") (pin "1") (pinfunction "1_1") (pintype "passive"))
      (node (ref "R209") (pin "2") (pinfunction "2_2") (pintype "passive"))
      (node (ref "R21") (pin "2") (pinfunction "2_2") (pintype "passive"))
      (node (ref "R210") (pin "1") (pinfunction "1_1") (pintype "passive"))
      (node (ref "R211") (pin "2") (pinfunction "2_2") (pintype "passive"))
      (node (ref "R212") (pin "1") (pinfunction "1_1") (pintype "passive"))
      (node (ref "R213") (pin "2") (pinfunction "2_2") (pintype "passive"))
      (node (ref "R214") (pin "1") (pinfunction "1_1") (pintype "passive"))
      (node (ref "R215") (pin "2") (pinfunction "2_2") (pintype "passive"))
      (node (ref "R216") (pin "1") (pinfunction "1_1") (pintype "passive"))
      (node (ref "R217") (pin "2") (pinfunction "2_2") (pintype "passive"))
      (node (ref "R218") (pin "1") (pinfunction "1_1") (pintype "passive"))
      (node (ref "R219") (pin "2") (pinfunction "2_2") (pintype "passive"))
      (node (ref "R22") (pin "1") (pinfunction "1_1") (pintype "passive"))
      (node (ref "R220") (pin "1") (pinfunction "1_1") (pintype "passive"))
      (node (ref "R221") (pin "2") (pinfunction "2_2") (pintype "passive"))
      (node (ref "R222") (pin "1") (pinfunction "1_1") (pintype "passive"))
      (node (ref "R223") (pin "2") (pinfunction "2_2") (pintype "passive"))
      (node (ref "R224") (pin "1") (pinfunction "1_1") (pintype "passive"))
      (node (ref "R225") (pin "2") (pinfunction "2_2") (pintype "passive"))
      (node (ref "R226") (pin "1") (pinfunction "1_1") (pintype "passive"))
      (node (ref "R227") (pin "2") (pinfunction "2_2") (pintype "passive"))
      (node (ref "R228") (pin "1") (pinfunction "1_1") (pintype "passive"))
      (node (ref "R229") (pin "2") (pinfunction "2_2") (pintype "passive"))
      (node (ref "R23") (pin "2") (pinfunction "2_2") (pintype "passive"))
      (node (ref "R230") (pin "1") (pinfunction "1_1") (pintype "passive"))
      (node (ref "R231") (pin "2") (pinfunction "2_2") (pintype "passive"))
      (node (ref "R232") (pin "1") (pinfunction "1_1") (pintype "passive"))
      (node (ref "R233") (pin "2") (pinfunction "2_2") (pintype "passive"))
      (node (ref "R234") (pin "1") (pinfunction "1_1") (pintype "passive"))
      (node (ref "R235") (pin "2") (pinfunction "2_2") (pintype "passive"))
      (node (ref "R236") (pin "1") (pinfunction "1_1") (pintype "passive"))
      (node (ref "R237") (pin "2") (pinfunction "2_2") (pintype "passive"))
      (node (ref "R238") (pin "1") (pinfunction "1_1") (pintype "passive"))
      (node (ref "R239") (pin "2") (pinfunction "2_2") (pintype "passive"))
      (node (ref "R24") (pin "1") (pinfunction "1_1") (pintype "passive"))
      (node (ref "R240") (pin "1") (pinfunction "1_1") (pintype "passive"))
      (node (ref "R241") (pin "2") (pinfunction "2_2") (pintype "passive"))
      (node (ref "R242") (pin "1") (pinfunction "1_1") (pintype "passive"))
      (node (ref "R243") (pin "2") (pinfunction "2_2") (pintype "passive"))
      (node (ref "R244") (pin "1") (pinfunction "1_1") (pintype "passive"))
      (node (ref "R245") (pin "2") (pinfunction "2_2") (pintype "passive"))
      (node (ref "R246") (pin "1") (pinfunction "1_1") (pintype "passive"))
      (node (ref "R247") (pin "2") (pinfunction "2_2") (pintype "passive"))
      (node (ref "R248") (pin "1") (pinfunction "1_1") (pintype "passive"))
      (node (ref "R249") (pin "2") (pinfunction "2_2") (pintype "passive"))
      (node (ref "R25") (pin "2") (pinfunction "2_2") (pintype "passive"))
      (node (ref "R250") (pin "1") (pinfunction "1_1") (pintype "passive"))
      (node (ref "R251") (pin "2") (pinfunction "2_2") (pintype "passive"))
      (node (ref "R252") (pin "1") (pinfunction "1_1") (pintype "passive"))
      (node (ref "R253") (pin "2") (pinfunction "2_2") (pintype "passive"))
      (node (ref "R254") (pin "1") (pinfunction "1_1") (pintype "passive"))
      (node (ref "R255") (pin "2") (pinfunction "2_2") (pintype "passive"))
      (node (ref "R256") (pin "1") (pinfunction "1_1") (pintype "passive"))
      (node (ref "R257") (pin "2") (pinfunction "2_2") (pintype "passive"))
      (node (ref "R258") (pin "1") (pinfunction "1_1") (pintype "passive"))
      (node (ref "R259") (pin "2") (pinfunction "2_2") (pintype "passive"))
      (node (ref "R26") (pin "1") (pinfunction "1_1") (pintype "passive"))
      (node (ref "R260") (pin "1") (pinfunction "1_1") (pintype "passive"))
      (node (ref "R261") (pin "2") (pinfunction "2_2") (pintype "passive"))
      (node (ref "R262") (pin "1") (pinfunction "1_1") (pintype "passive"))
      (node (ref "R263") (pin "2") (pinfunction "2_2") (pintype "passive"))
      (node (ref "R264") (pin "1") (pinfunction "1_1") (pintype "passive"))
      (node (ref "R265") (pin "2") (pinfunction "2_2") (pintype "passive"))
      (node (ref "R266") (pin "1") (pinfunction "1_1") (pintype "passive"))
      (node (ref "R267") (pin "2") (pinfunction "2_2") (pintype "passive"))
      (node (ref "R268") (pin "1") (pinfunction "1_1") (pintype "passive"))
      (node (ref "R269") (pin "2") (pinfunction "2_2") (pintype "passive"))
      (node (ref "R27") (pin "2") (pinfunction "2_2") (pintype "passive"))
      (node (ref "R270") (pin "1") (pinfunction "1_1") (pintype "passive"))
      (node (ref "R271") (pin "2") (pinfunction "2_2") (pintype "passive"))
      (node (ref "R272") (pin "1") (pinfunction "1_1") (pintype "passive"))
      (node (ref "R273") (pin "2") (pinfunction "2_2") (pintype "passive"))
      (node (ref "R274") (pin "1") (pinfunction "1_1") (pintype "passive"))
      (node (ref "R275") (pin "2") (pinfunction "2_2") (pintype "passive"))
      (node (ref "R276") (pin "1") (pinfunction "1_1") (pintype "passive"))
      (node (ref "R277") (pin "2") (pinfunction "2_2") (pintype "passive"))
      (node (ref "R278") (pin "1") (pinfunction "1_1") (pintype "passive"))
      (node (ref "R279") (pin "2") (pinfunction "2_2") (pintype "passive"))
      (node (ref "R28") (pin "1") (pinfunction "1_1") (pintype "passive"))
      (node (ref "R280") (pin "1") (pinfunction "1_1") (pintype "passive"))
      (node (ref "R281") (pin "2") (pinfunction "2_2") (pintype "passive"))
      (node (ref "R282") (pin "1") (pinfunction "1_1") (pintype "passive"))
      (node (ref "R283") (pin "2") (pinfunction "2_2") (pintype "passive"))
      (node (ref "R284") (pin "1") (pinfunction "1_1") (pintype "passive"))
      (node (ref "R285") (pin "2") (pinfunction "2_2") (pintype "passive"))
      (node (ref "R286") (pin "1") (pinfunction "1_1") (pintype "passive"))
      (node (ref "R287") (pin "2") (pinfunction "2_2") (pintype "passive"))
      (node (ref "R288") (pin "1") (pinfunction "1_1") (pintype "passive"))
      (node (ref "R289") (pin "2") (pinfunction "2_2") (pintype "passive"))
      (node (ref "R29") (pin "2") (pinfunction "2_2") (pintype "passive"))
      (node (ref "R290") (pin "1") (pinfunction "1_1") (pintype "passive"))
      (node (ref "R291") (pin "2") (pinfunction "2_2") (pintype "passive"))
      (node (ref "R292") (pin "1") (pinfunction "1_1") (pintype "passive"))
      (node (ref "R293") (pin "2") (pinfunction "2_2") (pintype "passive"))
      (node (ref "R294") (pin "1") (pinfunction "1_1") (pintype "passive"))
      (node (ref "R295") (pin "2") (pinfunction "2_2") (pintype "passive"))
      (node (ref "R296") (pin "1") (pinfunction "1_1") (pintype "passive"))
      (node (ref "R297") (pin "2") (pinfunction "2_2") (pintype "passive"))
      (node (ref "R298") (pin "1") (pinfunction "1_1") (pintype "passive"))
      (node (ref "R299") (pin "2") (pinfunction "2_2") (pintype "passive"))
      (node (ref "R3") (pin "2") (pinfunction "2_2") (pintype "passive"))
      (node (ref "R30") (pin "1") (pinfunction "1_1") (pintype "passive"))
      (node (ref "R300") (pin "1") (pinfunction "1_1") (pintype "passive"))
      (node (ref "R31") (pin "2") (pinfunction "2_2") (pintype "passive"))
      (node (ref "R32") (pin "1") (pinfunction "1_1") (pintype "passive"))
      (node (ref "R33") (pin "2") (pinfunction "2_2") (pintype "passive"))
      (node (ref "R34") (pin "1") (pinfunction "1_1") (pintype "passive"))
      (node (ref "R35") (pin "2") (pinfunction "2_2") (pintype "passive"))
      (node (ref "R36") (pin "1") (pinfunction "1_1") (pintype "passive"))
      (node (ref "R37") (pin "2") (pinfunction "2_2") (pintype "passive"))
      (node (ref "R38") (pin "1") (pinfunction "1_1") (pintype "passive"))
      (node (ref "R39") (pin "2") (pinfunction "2_2") (pintype "passive"))
      (node (ref "R4") (pin "1") (pinfunction "1_1") (pintype "passive"))
      (node (ref "R40") (pin "1") (pinfunction "1_1") (pintype "passive"))
      (node (ref "R41") (pin "2") (pinfunction "2_2") (pintype "passive"))
      (node (ref "R42") (pin "1") (pinfunction "1_1") (pintype "passive"))
      (node (ref "R43") (pin "2") (pinfunction "2_2") (pintype "passive"))
      (node (ref "R44") (pin "1") (pinfunction "1_1") (pintype "passive"))
      (node (ref "R45") (pin "2") (pinfunction "2_2") (pintype "passive"))
      (node (ref "R46") (pin "1") (pinfunction "1_1") (pintype "passive"))
      (node (ref "R47") (pin "2") (pinfunction "2_2") (pintype "passive"))
      (node (ref "R48") (pin "1") (pinfunction "1_1") (pintype "passive"))
      (node (ref "R49") (pin "2") (pinfunction "2_2") (pintype "passive"))
      (node (ref "R5") (pin "2") (pinfunction "2_2") (pintype "passive"))
      (node (ref "R50") (pin "1") (pinfunction "1_1") (pintype "passive"))
      (node (ref "R51") (pin "2") (pinfunction "2_2") (pintype "passive"))
      (node (ref "R52") (pin "1") (pinfunction "1_1") (pintype "passive"))
      (node (ref "R53") (pin "2") (pinfunction "2_2") (pintype "passive"))
      (node (ref "R54") (pin "1") (pinfunction "1_1") (pintype "passive"))
      (node (ref "R55") (pin "2") (pinfunction "2_2") (pintype "passive"))
      (node (ref "R56") (pin "1") (pinfunction "1_1") (pintype "passive"))
      (node (ref "R57") (pin "2") (pinfunction "2_2") (pintype "passive"))
      (node (ref "R58") (pin "1") (pinfunction "1_1") (pintype "passive"))
      (node (ref "R59") (pin "2") (pinfunction "2_2") (pintype "passive"))
      (node (ref "R6") (pin "1") (pinfunction "1_1") (pintype "passive"))
      (node (ref "R60") (pin "1") (pinfunction "1_1") (pintype "passive"))
      (node (ref "R61") (pin "2") (pinfunction "2_2") (pintype "passive"))
      (node (ref "R62") (pin "1") (pinfunction "1_1") (pintype "passive"))
      (node (ref "R63") (pin "2") (pinfunction "2_2") (pintype "passive"))
      (node (ref "R64") (pin "1") (pinfunction "1_1") (pintype "passive"))
      (node (ref "R65") (pin "2") (pinfunction "2_2") (pintype "passive"))
      (node (ref "R66") (pin "1") (pinfunction "1_1") (pintype "passive"))
      (node (ref "R67") (pin "2") (pinfunction "2_2") (pintype "passive"))
      (node (ref "R68") (pin "1") (pinfunction "1_1") (pintype "passive"))
      (node (ref "R69") (pin "2") (pinfunction "2_2") (pintype "passive"))
      (node (ref "R7") (pin "2") (pinfunction "2_2") (pintype "passive"))
      (node (ref "R70") (pin "1") (pinfunction "1_1") (pintype "passive"))
      (node (ref "R71") (pin "2") (pinfunction "2_2") (pintype "passive"))
      (node (ref "R72") (pin "1") (pinfunction "1_1") (pintype "passive"))
      (node (ref "R73") (pin "2") (pinfunction "2_2") (pintype "passive"))
      (node (ref "R74") (pin "1") (pinfunction "1_1") (pintype "passive"))
      (node (ref "R75") (pin "2") (pinfunction "2_2") (pintype "passive"))
      (node (ref "R76") (pin "1") (pinfunction "1_1") (pintype "passive"))
      (node (ref "R77") (pin "2") (pinfunction "2_2") (pintype "passive"))
      (node (ref "R78") (pin "1") (pinfunction "1_1") (pintype "passive"))
      (node (ref "R79") (pin "2") (pinfunction "2_2") (pintype "passive"))
      (node (ref "R8") (pin "1") (pinfunction "1_1") (pintype "passive"))
      (node (ref "R80") (pin "1") (pinfunction "1_1") (pintype "passive"))
      (node (ref "R81") (pin "2") (pinfunction "2_2") (pintype "passive"))
      (node (ref "R82") (pin "1") (pinfunction "1_1") (pintype "passive"))
      (node (ref "R83") (pin "2") (pinfunction "2_2") (pintype "passive"))
      (node (ref "R84") (pin "1") (pinfunction "1_1") (pintype "passive"))
      (node (ref "R85") (pin "2") (pinfunction "2_2") (pintype "passive"))
      (node (ref "R86") (pin "1") (pinfunction "1_1") (pintype "passive"))
      (node (ref "R87") (pin "2") (pinfunction "2_2") (pintype "passive"))
      (node (ref "R88") (pin "1") (pinfunction "1_1") (pintype "passive"))
      (node (ref "R89") (pin "2") (pinfunction "2_2") (pintype "passive"))
      (node (ref "R9") (pin "2") (pinfunction "2_2") (pintype "passive"))
      (node (ref "R90") (pin "1") (pinfunction "1_1") (pintype "passive"))
      (node (ref "R91") (pin "2") (pinfunction "2_2") (pintype "passive"))
      (node (ref "R92") (pin "1") (pinfunction "1_1") (pintype "passive"))
      (node (ref "R93") (pin "2") (pinfunction "2_2") (pintype "passive"))
      (node (ref "R94") (pin "1") (pinfunction "1_1") (pintype "passive"))
      (node (ref "R95") (pin "2") (pinfunction "2_2") (pintype "passive"))
      (node (ref "R96") (pin "1") (pinfunction "1_1") (pintype "passive"))
      (node (ref "R97") (pin "2") (pinfunction "2_2") (pintype "passive"))
      (node (ref "R98") (pin "1") (pinfunction "1_1") (pintype "passive"))
      (node (ref "R99") (pin "2") (pinfunction "2_2") (pintype "passive"))
    )
    (net (code "3") (name "Net-(J1-PadA01)") (class "Default")
      (node (ref "J1") (pin "A01") (pinfunction "A01_A01") (pintype "passive"))
      (node (ref "J1") (pin "VA01") (pinfunction "A01_VA01") (pintype "passive"))
      (node (ref "R1") (pin "1") (pinfunction "1_1") (pintype "passive"))
    )
    (net (code "4") (name "Net-(J1-PadA02)") (class "Default")
      (node (ref "J1") (pin "A02") (pinfunction "A02_A02") (pintype "passive"))
      (node (ref "J1") (pin "VA02") (pinfunction "A02_VA02") (pintype "passive"))
      (node (ref "R11") (pin "1") (pinfunction "1_1") (pintype "passive"))
    )
    (net (code "5") (name "Net-(J1-PadA03)") (class "Default")
      (node (ref "J1") (pin "A03") (pinfunction "A03_A03") (pintype "passive"))
      (node (ref "J1") (pin "VA03") (pinfunction "A03_VA03") (pintype "passive"))
      (node (ref "R21") (pin "1") (pinfunction "1_1") (pintype "passive"))
    )
    (net (code "6") (name "Net-(J1-PadA04)") (class "Default")
      (node (ref "J1") (pin "A04") (pinfunction "A04_A04") (pintype "passive"))
      (node (ref "J1") (pin "VA04") (pinfunction "A04_VA04") (pintype "passive"))
      (node (ref "R31") (pin "1") (pinfunction "1_1") (pintype "passive"))
    )
    (net (code "7") (name "Net-(J1-PadA05)") (class "Default")
      (node (ref "J1") (pin "A05") (pinfunction "A05_A05") (pintype "passive"))
      (node (ref "J1") (pin "VA05") (pinfunction "A05_VA05") (pintype "passive"))
      (node (ref "R41") (pin "1") (pinfunction "1_1") (pintype "passive"))
    )
    (net (code "8") (name "Net-(J1-PadA06)") (class "Default")
      (node (ref "J1") (pin "A06") (pinfunction "A06_A06") (pintype "passive"))
      (node (ref "J1") (pin "VA06") (pinfunction "A06_VA06") (pintype "passive"))
      (node (ref "R51") (pin "1") (pinfunction "1_1") (pintype "passive"))
    )
    (net (code "9") (name "Net-(J1-PadA07)") (class "Default")
      (node (ref "J1") (pin "A07") (pinfunction "A07_A07") (pintype "passive"))
      (node (ref "J1") (pin "VA07") (pinfunction "A07_VA07") (pintype "passive"))
      (node (ref "R61") (pin "1") (pinfunction "1_1") (pintype "passive"))
    )
    (net (code "10") (name "Net-(J1-PadA08)") (class "Default")
      (node (ref "J1") (pin "A08") (pinfunction "A08_A08") (pintype "passive"))
      (node (ref "J1") (pin "VA08") (pinfunction "A08_VA08") (pintype "passive"))
      (node (ref "R71") (pin "1") (pinfunction "1_1") (pintype "passive"))
    )
    (net (code "11") (name "Net-(J1-PadA09)") (class "Default")
      (node (ref "J1") (pin "A09") (pinfunction "A09_A09") (pintype "passive"))
      (node (ref "J1") (pin "VA09") (pinfunction "A09_VA09") (pintype "passive"))
      (node (ref "R81") (pin "1") (pinfunction "1_1") (pintype "passive"))
    )
    (net (code "12") (name "Net-(J1-PadA10)") (class "Default")
      (node (ref "J1") (pin "A10") (pinfunction "A10_A10") (pintype "passive"))
      (node (ref "J1") (pin "VA10") (pinfunction "A10_VA10") (pintype "passive"))
      (node (ref "R91") (pin "1") (pinfunction "1_1") (pintype "passive"))
    )
    (net (code "13") (name "Net-(J1-PadA11)") (class "Default")
      (node (ref "J1") (pin "A11") (pinfunction "A11_A11") (pintype "passive"))
      (node (ref "J1") (pin "VA11") (pinfunction "A11_VA11") (pintype "passive"))
      (node (ref "R101") (pin "1") (pinfunction "1_1") (pintype "passive"))
    )
    (net (code "14") (name "Net-(J1-PadA12)") (class "Default")
      (node (ref "J1") (pin "A12") (pinfunction "A12_A12") (pintype "passive"))
      (node (ref "J1") (pin "VA12") (pinfunction "A12_VA12") (pintype "passive"))
      (node (ref "R111") (pin "1") (pinfunction "1_1") (pintype "passive"))
    )
    (net (code "15") (name "Net-(J1-PadA13)") (class "Default")
      (node (ref "J1") (pin "A13") (pinfunction "A13_A13") (pintype "passive"))
      (node (ref "J1") (pin "VA13") (pinfunction "A13_VA13") (pintype "passive"))
      (node (ref "R121") (pin "1") (pinfunction "1_1") (pintype "passive"))
    )
    (net (code "16") (name "Net-(J1-PadA14)") (class "Default")
      (node (ref "J1") (pin "A14") (pinfunction "A14_A14") (pintype "passive"))
      (node (ref "J1") (pin "VA14") (pinfunction "A14_VA14") (pintype "passive"))
      (node (ref "R131") (pin "1") (pinfunction "1_1") (pintype "passive"))
    )
    (net (code "17") (name "Net-(J1-PadA15)") (class "Default")
      (node (ref "J1") (pin "A15") (pinfunction "A15_A15") (pintype "passive"))
      (node (ref "J1") (pin "VA15") (pinfunction "A15_VA15") (pintype "passive"))
      (node (ref "R141") (pin "1") (pinfunction "1_1") (pintype "passive"))
    )
    (net (code "18") (name "Net-(J1-PadA16)") (class "Default")
      (node (ref "J1") (pin "A16") (pinfunction "A16_A16") (pintype "passive"))
      (node (ref "J1") (pin "VA16") (pinfunction "A16_VA16") (pintype "passive"))
      (node (ref "R151") (pin "1") (pinfunction "1_1") (pintype "passive"))
    )
    (net (code "19") (name "Net-(J1-PadA17)") (class "Default")
      (node (ref "J1") (pin "A17") (pinfunction "A17_A17") (pintype "passive"))
      (node (ref "J1") (pin "VA17") (pinfunction "A17_VA17") (pintype "passive"))
      (node (ref "R161") (pin "1") (pinfunction "1_1") (pintype "passive"))
    )
    (net (code "20") (name "Net-(J1-PadA18)") (class "Default")
      (node (ref "J1") (pin "A18") (pinfunction "A18_A18") (pintype "passive"))
      (node (ref "J1") (pin "VA18") (pinfunction "A18_VA18") (pintype "passive"))
      (node (ref "R171") (pin "1") (pinfunction "1_1") (pintype "passive"))
    )
    (net (code "21") (name "Net-(J1-PadA19)") (class "Default")
      (node (ref "J1") (pin "A19") (pinfunction "A19_A19") (pintype "passive"))
      (node (ref "J1") (pin "VA19") (pinfunction "A19_VA19") (pintype "passive"))
      (node (ref "R181") (pin "1") (pinfunction "1_1") (pintype "passive"))
    )
    (net (code "22") (name "Net-(J1-PadA20)") (class "Default")
      (node (ref "J1") (pin "A20") (pinfunction "A20_A20") (pintype "passive"))
      (node (ref "J1") (pin "VA20") (pinfunction "A20_VA20") (pintype "passive"))
      (node (ref "R191") (pin "1") (pinfunction "1_1") (pintype "passive"))
    )
    (net (code "23") (name "Net-(J1-PadA21)") (class "Default")
      (node (ref "J1") (pin "A21") (pinfunction "A21_A21") (pintype "passive"))
      (node (ref "J1") (pin "VA21") (pinfunction "A21_VA21") (pintype "passive"))
      (node (ref "R201") (pin "1") (pinfunction "1_1") (pintype "passive"))
    )
    (net (code "24") (name "Net-(J1-PadA22)") (class "Default")
      (node (ref "J1") (pin "A22") (pinfunction "A22_A22") (pintype "passive"))
      (node (ref "J1") (pin "VA22") (pinfunction "A22_VA22") (pintype "passive"))
      (node (ref "R211") (pin "1") (pinfunction "1_1") (pintype "passive"))
    )
    (net (code "25") (name "Net-(J1-PadA23)") (class "Default")
      (node (ref "J1") (pin "A23") (pinfunction "A23_A23") (pintype "passive"))
      (node (ref "J1") (pin "VA23") (pinfunction "A23_VA23") (pintype "passive"))
      (node (ref "R221") (pin "1") (pinfunction "1_1") (pintype "passive"))
    )
    (net (code "26") (name "Net-(J1-PadA24)") (class "Default")
      (node (ref "J1") (pin "A24") (pinfunction "A24_A24") (pintype "passive"))
      (node (ref "J1") (pin "VA24") (pinfunction "A24_VA24") (pintype "passive"))
      (node (ref "R231") (pin "1") (pinfunction "1_1") (pintype "passive"))
    )
    (net (code "27") (name "Net-(J1-PadA25)") (class "Default")
      (node (ref "J1") (pin "A25") (pinfunction "A25_A25") (pintype "passive"))
      (node (ref "J1") (pin "VA25") (pinfunction "A25_VA25") (pintype "passive"))
      (node (ref "R241") (pin "1") (pinfunction "1_1") (pintype "passive"))
    )
    (net (code "28") (name "Net-(J1-PadA26)") (class "Default")
      (node (ref "J1") (pin "A26") (pinfunction "A26_A26") (pintype "passive"))
      (node (ref "J1") (pin "VA26") (pinfunction "A26_VA26") (pintype "passive"))
      (node (ref "R251") (pin "1") (pinfunction "1_1") (pintype "passive"))
    )
    (net (code "29") (name "Net-(J1-PadA27)") (class "Default")
      (node (ref "J1") (pin "A27") (pinfunction "A27_A27") (pintype "passive"))
      (node (ref "J1") (pin "VA27") (pinfunction "A27_VA27") (pintype "passive"))
      (node (ref "R261") (pin "1") (pinfunction "1_1") (pintype "passive"))
    )
    (net (code "30") (name "Net-(J1-PadA28)") (class "Default")
      (node (ref "J1") (pin "A28") (pinfunction "A28_A28") (pintype "passive"))
      (node (ref "J1") (pin "VA28") (pinfunction "A28_VA28") (pintype "passive"))
      (node (ref "R271") (pin "1") (pinfunction "1_1") (pintype "passive"))
    )
    (net (code "31") (name "Net-(J1-PadA29)") (class "Default")
      (node (ref "J1") (pin "A29") (pinfunction "A29_A29") (pintype "passive"))
      (node (ref "J1") (pin "VA29") (pinfunction "A29_VA29") (pintype "passive"))
      (node (ref "R281") (pin "1") (pinfunction "1_1") (pintype "passive"))
    )
    (net (code "32") (name "Net-(J1-PadA30)") (class "Default")
      (node (ref "J1") (pin "A30") (pinfunction "A30_A30") (pintype "passive"))
      (node (ref "J1") (pin "VA30") (pinfunction "A30_VA30") (pintype "passive"))
      (node (ref "R291") (pin "1") (pinfunction "1_1") (pintype "passive"))
    )
    (net (code "33") (name "Net-(J1-PadB01)") (class "Default")
      (node (ref "J1") (pin "B01") (pinfunction "B01_B01") (pintype "passive"))
      (node (ref "J1") (pin "VB01") (pinfunction "B01_VB01") (pintype "passive"))
      (node (ref "R2") (pin "2") (pinfunction "2_2") (pintype "passive"))
    )
    (net (code "34") (name "Net-(J1-PadB02)") (class "Default")
      (node (ref "J1") (pin "B02") (pinfunction "B02_B02") (pintype "passive"))
      (node (ref "J1") (pin "VB02") (pinfunction "B02_VB02") (pintype "passive"))
      (node (ref "R12") (pin "2") (pinfunction "2_2") (pintype "passive"))
    )
    (net (code "35") (name "Net-(J1-PadB03)") (class "Default")
      (node (ref "J1") (pin "B03") (pinfunction "B03_B03") (pintype "passive"))
      (node (ref "J1") (pin "VB03") (pinfunction "B03_VB03") (pintype "passive"))
      (node (ref "R22") (pin "2") (pinfunction "2_2") (pintype "passive"))
    )
    (net (code "36") (name "Net-(J1-PadB04)") (class "Default")
      (node (ref "J1") (pin "B04") (pinfunction "B04_B04") (pintype "passive"))
      (node (ref "J1") (pin "VB04") (pinfunction "B04_VB04") (pintype "passive"))
      (node (ref "R32") (pin "2") (pinfunction "2_2") (pintype "passive"))
    )
    (net (code "37") (name "Net-(J1-PadB05)") (class "Default")
      (node (ref "J1") (pin "B05") (pinfunction "B05_B05") (pintype "passive"))
      (node (ref "J1") (pin "VB05") (pinfunction "B05_VB05") (pintype "passive"))
      (node (ref "R42") (pin "2") (pinfunction "2_2") (pintype "passive"))
    )
    (net (code "38") (name "Net-(J1-PadB06)") (class "Default")
      (node (ref "J1") (pin "B06") (pinfunction "B06_B06") (pintype "passive"))
      (node (ref "J1") (pin "VB06") (pinfunction "B06_VB06") (pintype "passive"))
      (node (ref "R52") (pin "2") (pinfunction "2_2") (pintype "passive"))
    )
    (net (code "39") (name "Net-(J1-PadB07)") (class "Default")
      (node (ref "J1") (pin "B07") (pinfunction "B07_B07") (pintype "passive"))
      (node (ref "J1") (pin "VB07") (pinfunction "B07_VB07") (pintype "passive"))
      (node (ref "R62") (pin "2") (pinfunction "2_2") (pintype "passive"))
    )
    (net (code "40") (name "Net-(J1-PadB08)") (class "Default")
      (node (ref "J1") (pin "B08") (pinfunction "B08_B08") (pintype "passive"))
      (node (ref "J1") (pin "VB08") (pinfunction "B08_VB08") (pintype "passive"))
      (node (ref "R72") (pin "2") (pinfunction "2_2") (pintype "passive"))
    )
    (net (code "41") (name "Net-(J1-PadB09)") (class "Default")
      (node (ref "J1") (pin "B09") (pinfunction "B09_B09") (pintype "passive"))
      (node (ref "J1") (pin "VB09") (pinfunction "B09_VB09") (pintype "passive"))
      (node (ref "R82") (pin "2") (pinfunction "2_2") (pintype "passive"))
    )
    (net (code "42") (name "Net-(J1-PadB10)") (class "Default")
      (node (ref "J1") (pin "B10") (pinfunction "B10_B10") (pintype "passive"))
      (node (ref "J1") (pin "VB10") (pinfunction "B10_VB10") (pintype "passive"))
      (node (ref "R92") (pin "2") (pinfunction "2_2") (pintype "passive"))
    )
    (net (code "43") (name "Net-(J1-PadB11)") (class "Default")
      (node (ref "J1") (pin "B11") (pinfunction "B11_B11") (pintype "passive"))
      (node (ref "J1") (pin "VB11") (pinfunction "B11_VB11") (pintype "passive"))
      (node (ref "R102") (pin "2") (pinfunction "2_2") (pintype "passive"))
    )
    (net (code "44") (name "Net-(J1-PadB12)") (class "Default")
      (node (ref "J1") (pin "B12") (pinfunction "B12_B12") (pintype "passive"))
      (node (ref "J1") (pin "VB12") (pinfunction "B12_VB12") (pintype "passive"))
      (node (ref "R112") (pin "2") (pinfunction "2_2") (pintype "passive"))
    )
    (net (code "45") (name "Net-(J1-PadB13)") (class "Default")
      (node (ref "J1") (pin "B13") (pinfunction "B13_B13") (pintype "passive"))
      (node (ref "J1") (pin "VB13") (pinfunction "B13_VB13") (pintype "passive"))
      (node (ref "R122") (pin "2") (pinfunction "2_2") (pintype "passive"))
    )
    (net (code "46") (name "Net-(J1-PadB14)") (class "Default")
      (node (ref "J1") (pin "B14") (pinfunction "B14_B14") (pintype "passive"))
      (node (ref "J1") (pin "VB14") (pinfunction "B14_VB14") (pintype "passive"))
      (node (ref "R132") (pin "2") (pinfunction "2_2") (pintype "passive"))
    )
    (net (code "47") (name "Net-(J1-PadB15)") (class "Default")
      (node (ref "J1") (pin "B15") (pinfunction "B15_B15") (pintype "passive"))
      (node (ref "J1") (pin "VB15") (pinfunction "B15_VB15") (pintype "passive"))
      (node (ref "R142") (pin "2") (pinfunction "2_2") (pintype "passive"))
    )
    (net (code "48") (name "Net-(J1-PadB16)") (class "Default")
      (node (ref "J1") (pin "B16") (pinfunction "B16_B16") (pintype "passive"))
      (node (ref "J1") (pin "VB16") (pinfunction "B16_VB16") (pintype "passive"))
      (node (ref "R152") (pin "2") (pinfunction "2_2") (pintype "passive"))
    )
    (net (code "49") (name "Net-(J1-PadB17)") (class "Default")
      (node (ref "J1") (pin "B17") (pinfunction "B17_B17") (pintype "passive"))
      (node (ref "J1") (pin "VB17") (pinfunction "B17_VB17") (pintype "passive"))
      (node (ref "R162") (pin "2") (pinfunction "2_2") (pintype "passive"))
    )
    (net (code "50") (name "Net-(J1-PadB18)") (class "Default")
      (node (ref "J1") (pin "B18") (pinfunction "B18_B18") (pintype "passive"))
      (node (ref "J1") (pin "VB18") (pinfunction "B18_VB18") (pintype "passive"))
      (node (ref "R172") (pin "2") (pinfunction "2_2") (pintype "passive"))
    )
    (net (code "51") (name "Net-(J1-PadB19)") (class "Default")
      (node (ref "J1") (pin "B19") (pinfunction "B19_B19") (pintype "passive"))
      (node (ref "J1") (pin "VB19") (pinfunction "B19_VB19") (pintype "passive"))
      (node (ref "R182") (pin "2") (pinfunction "2_2") (pintype "passive"))
    )
    (net (code "52") (name "Net-(J1-PadB20)") (class "Default")
      (node (ref "J1") (pin "B20") (pinfunction "B20_B20") (pintype "passive"))
      (node (ref "J1") (pin "VB20") (pinfunction "B20_VB20") (pintype "passive"))
      (node (ref "R192") (pin "2") (pinfunction "2_2") (pintype "passive"))
    )
    (net (code "53") (name "Net-(J1-PadB21)") (class "Default")
      (node (ref "J1") (pin "B21") (pinfunction "B21_B21") (pintype "passive"))
      (node (ref "J1") (pin "VB21") (pinfunction "B21_VB21") (pintype "passive"))
      (node (ref "R202") (pin "2") (pinfunction "2_2") (pintype "passive"))
    )
    (net (code "54") (name "Net-(J1-PadB22)") (class "Default")
      (node (ref "J1") (pin "B22") (pinfunction "B22_B22") (pintype "passive"))
      (node (ref "J1") (pin "VB22") (pinfunction "B22_VB22") (pintype "passive"))
      (node (ref "R212") (pin "2") (pinfunction "2_2") (pintype "passive"))
    )
    (net (code "55") (name "Net-(J1-PadB23)") (class "Default")
      (node (ref "J1") (pin "B23") (pinfunction "B23_B23") (pintype "passive"))
      (node (ref "J1") (pin "VB23") (pinfunction "B23_VB23") (pintype "passive"))
      (node (ref "R222") (pin "2") (pinfunction "2_2") (pintype "passive"))
    )
    (net (code "56") (name "Net-(J1-PadB24)") (class "Default")
      (node (ref "J1") (pin "B24") (pinfunction "B24_B24") (pintype "passive"))
      (node (ref "J1") (pin "VB24") (pinfunction "B24_VB24") (pintype "passive"))
      (node (ref "R232") (pin "2") (pinfunction "2_2") (pintype "passive"))
    )
    (net (code "57") (name "Net-(J1-PadB25)") (class "Default")
      (node (ref "J1") (pin "B25") (pinfunction "B25_B25") (pintype "passive"))
      (node (ref "J1") (pin "VB25") (pinfunction "B25_VB25") (pintype "passive"))
      (node (ref "R242") (pin "2") (pinfunction "2_2") (pintype "passive"))
    )
    (net (code "58") (name "Net-(J1-PadB26)") (class "Default")
      (node (ref "J1") (pin "B26") (pinfunction "B26_B26") (pintype "passive"))
      (node (ref "J1") (pin "VB26") (pinfunction "B26_VB26") (pintype "passive"))
      (node (ref "R252") (pin "2") (pinfunction "2_2") (pintype "passive"))
    )
    (net (code "59") (name "Net-(J1-PadB27)") (class "Default")
      (node (ref "J1") (pin "B27") (pinfunction "B27_B27") (pintype "passive"))
      (node (ref "J1") (pin "VB27") (pinfunction "B27_VB27") (pintype "passive"))
      (node (ref "R262") (pin "2") (pinfunction "2_2") (pintype "passive"))
    )
    (net (code "60") (name "Net-(J1-PadB28)") (class "Default")
      (node (ref "J1") (pin "B28") (pinfunction "B28_B28") (pintype "passive"))
      (node (ref "J1") (pin "VB28") (pinfunction "B28_VB28") (pintype "passive"))
      (node (ref "R272") (pin "2") (pinfunction "2_2") (pintype "passive"))
    )
    (net (code "61") (name "Net-(J1-PadB29)") (class "Default")
      (node (ref "J1") (pin "B29") (pinfunction "B29_B29") (pintype "passive"))
      (node (ref "J1") (pin "VB29") (pinfunction "B29_VB29") (pintype "passive"))
      (node (ref "R282") (pin "2") (pinfunction "2_2") (pintype "passive"))
    )
    (net (code "62") (name "Net-(J1-PadB30)") (class "Default")
      (node (ref "J1") (pin "B30") (pinfunction "B30_B30") (pintype "passive"))
      (node (ref "J1") (pin "VB30") (pinfunction "B30_VB30") (pintype "passive"))
      (node (ref "R292") (pin "2") (pinfunction "2_2") (pintype "passive"))
    )
    (net (code "63") (name "Net-(J1-PadC01)") (class "Default")
      (node (ref "J1") (pin "C01") (pinfunction "C01_C01") (pintype "passive"))
      (node (ref "J1") (pin "VC01") (pinfunction "C01_VC01") (pintype "passive"))
      (node (ref "R3") (pin "1") (pinfunction "1_1") (pintype "passive"))
    )
    (net (code "64") (name "Net-(J1-PadC02)") (class "Default")
      (node (ref "J1") (pin "C02") (pinfunction "C02_C02") (pintype "passive"))
      (node (ref "J1") (pin "VC02") (pinfunction "C02_VC02") (pintype "passive"))
      (node (ref "R13") (pin "1") (pinfunction "1_1") (pintype "passive"))
    )
    (net (code "65") (name "Net-(J1-PadC03)") (class "Default")
      (node (ref "J1") (pin "C03") (pinfunction "C03_C03") (pintype "passive"))
      (node (ref "J1") (pin "VC03") (pinfunction "C03_VC03") (pintype "passive"))
      (node (ref "R23") (pin "1") (pinfunction "1_1") (pintype "passive"))
    )
    (net (code "66") (name "Net-(J1-PadC04)") (class "Default")
      (node (ref "J1") (pin "C04") (pinfunction "C04_C04") (pintype "passive"))
      (node (ref "J1") (pin "VC04") (pinfunction "C04_VC04") (pintype "passive"))
      (node (ref "R33") (pin "1") (pinfunction "1_1") (pintype "passive"))
    )
    (net (code "67") (name "Net-(J1-PadC05)") (class "Default")
      (node (ref "J1") (pin "C05") (pinfunction "C05_C05") (pintype "passive"))
      (node (ref "J1") (pin "VC05") (pinfunction "C05_VC05") (pintype "passive"))
      (node (ref "R43") (pin "1") (pinfunction "1_1") (pintype "passive"))
    )
    (net (code "68") (name "Net-(J1-PadC06)") (class "Default")
      (node (ref "J1") (pin "C06") (pinfunction "C06_C06") (pintype "passive"))
      (node (ref "J1") (pin "VC06") (pinfunction "C06_VC06") (pintype "passive"))
      (node (ref "R53") (pin "1") (pinfunction "1_1") (pintype "passive"))
    )
    (net (code "69") (name "Net-(J1-PadC07)") (class "Default")
      (node (ref "J1") (pin "C07") (pinfunction "C07_C07") (pintype "passive"))
      (node (ref "J1") (pin "VC07") (pinfunction "C07_VC07") (pintype "passive"))
      (node (ref "R63") (pin "1") (pinfunction "1_1") (pintype "passive"))
    )
    (net (code "70") (name "Net-(J1-PadC08)") (class "Default")
      (node (ref "J1") (pin "C08") (pinfunction "C08_C08") (pintype "passive"))
      (node (ref "J1") (pin "VC08") (pinfunction "C08_VC08") (pintype "passive"))
      (node (ref "R73") (pin "1") (pinfunction "1_1") (pintype "passive"))
    )
    (net (code "71") (name "Net-(J1-PadC09)") (class "Default")
      (node (ref "J1") (pin "C09") (pinfunction "C09_C09") (pintype "passive"))
      (node (ref "J1") (pin "VC09") (pinfunction "C09_VC09") (pintype "passive"))
      (node (ref "R83") (pin "1") (pinfunction "1_1") (pintype "passive"))
    )
    (net (code "72") (name "Net-(J1-PadC10)") (class "Default")
      (node (ref "J1") (pin "C10") (pinfunction "C10_C10") (pintype "passive"))
      (node (ref "J1") (pin "VC10") (pinfunction "C10_VC10") (pintype "passive"))
      (node (ref "R93") (pin "1") (pinfunction "1_1") (pintype "passive"))
    )
    (net (code "73") (name "Net-(J1-PadC11)") (class "Default")
      (node (ref "J1") (pin "C11") (pinfunction "C11_C11") (pintype "passive"))
      (node (ref "J1") (pin "VC11") (pinfunction "C11_VC11") (pintype "passive"))
      (node (ref "R103") (pin "1") (pinfunction "1_1") (pintype "passive"))
    )
    (net (code "74") (name "Net-(J1-PadC12)") (class "Default")
      (node (ref "J1") (pin "C12") (pinfunction "C12_C12") (pintype "passive"))
      (node (ref "J1") (pin "VC12") (pinfunction "C12_VC12") (pintype "passive"))
      (node (ref "R113") (pin "1") (pinfunction "1_1") (pintype "passive"))
    )
    (net (code "75") (name "Net-(J1-PadC13)") (class "Default")
      (node (ref "J1") (pin "C13") (pinfunction "C13_C13") (pintype "passive"))
      (node (ref "J1") (pin "VC13") (pinfunction "C13_VC13") (pintype "passive"))
      (node (ref "R123") (pin "1") (pinfunction "1_1") (pintype "passive"))
    )
    (net (code "76") (name "Net-(J1-PadC14)") (class "Default")
      (node (ref "J1") (pin "C14") (pinfunction "C14_C14") (pintype "passive"))
      (node (ref "J1") (pin "VC14") (pinfunction "C14_VC14") (pintype "passive"))
      (node (ref "R133") (pin "1") (pinfunction "1_1") (pintype "passive"))
    )
    (net (code "77") (name "Net-(J1-PadC15)") (class "Default")
      (node (ref "J1") (pin "C15") (pinfunction "C15_C15") (pintype "passive"))
      (node (ref "J1") (pin "VC15") (pinfunction "C15_VC15") (pintype "passive"))
      (node (ref "R143") (pin "1") (pinfunction "1_1") (pintype "passive"))
    )
    (net (code "78") (name "Net-(J1-PadC16)") (class "Default")
      (node (ref "J1") (pin "C16") (pinfunction "C16_C16") (pintype "passive"))
      (node (ref "J1") (pin "VC16") (pinfunction "C16_VC16") (pintype "passive"))
      (node (ref "R153") (pin "1") (pinfunction "1_1") (pintype "passive"))
    )
    (net (code "79") (name "Net-(J1-PadC17)") (class "Default")
      (node (ref "J1") (pin "C17") (pinfunction "C17_C17") (pintype "passive"))
      (node (ref "J1") (pin "VC17") (pinfunction "C17_VC17") (pintype "passive"))
      (node (ref "R163") (pin "1") (pinfunction "1_1") (pintype "passive"))
    )
    (net (code "80") (name "Net-(J1-PadC18)") (class "Default")
      (node (ref "J1") (pin "C18") (pinfunction "C18_C18") (pintype "passive"))
      (node (ref "J1") (pin "VC18") (pinfunction "C18_VC18") (pintype "passive"))
      (node (ref "R173") (pin "1") (pinfunction "1_1") (pintype "passive"))
    )
    (net (code "81") (name "Net-(J1-PadC19)") (class "Default")
      (node (ref "J1") (pin "C19") (pinfunction "C19_C19") (pintype "passive"))
      (node (ref "J1") (pin "VC19") (pinfunction "C19_VC19") (pintype "passive"))
      (node (ref "R183") (pin "1") (pinfunction "1_1") (pintype "passive"))
    )
    (net (code "82") (name "Net-(J1-PadC20)") (class "Default")
      (node (ref "J1") (pin "C20") (pinfunction "C20_C20") (pintype "passive"))
      (node (ref "J1") (pin "VC20") (pinfunction "C20_VC20") (pintype "passive"))
      (node (ref "R193") (pin "1") (pinfunction "1_1") (pintype "passive"))
    )
    (net (code "83") (name "Net-(J1-PadC21)") (class "Default")
      (node (ref "J1") (pin "C21") (pinfunction "C21_C21") (pintype "passive"))
      (node (ref "J1") (pin "VC21") (pinfunction "C21_VC21") (pintype "passive"))
      (node (ref "R203") (pin "1") (pinfunction "1_1") (pintype "passive"))
    )
    (net (code "84") (name "Net-(J1-PadC22)") (class "Default")
      (node (ref "J1") (pin "C22") (pinfunction "C22_C22") (pintype "passive"))
      (node (ref "J1") (pin "VC22") (pinfunction "C22_VC22") (pintype "passive"))
      (node (ref "R213") (pin "1") (pinfunction "1_1") (pintype "passive"))
    )
    (net (code "85") (name "Net-(J1-PadC23)") (class "Default")
      (node (ref "J1") (pin "C23") (pinfunction "C23_C23") (pintype "passive"))
      (node (ref "J1") (pin "VC23") (pinfunction "C23_VC23") (pintype "passive"))
      (node (ref "R223") (pin "1") (pinfunction "1_1") (pintype "passive"))
    )
    (net (code "86") (name "Net-(J1-PadC24)") (class "Default")
      (node (ref "J1") (pin "C24") (pinfunction "C24_C24") (pintype "passive"))
      (node (ref "J1") (pin "VC24") (pinfunction "C24_VC24") (pintype "passive"))
      (node (ref "R233") (pin "1") (pinfunction "1_1") (pintype "passive"))
    )
    (net (code "87") (name "Net-(J1-PadC25)") (class "Default")
      (node (ref "J1") (pin "C25") (pinfunction "C25_C25") (pintype "passive"))
      (node (ref "J1") (pin "VC25") (pinfunction "C25_VC25") (pintype "passive"))
      (node (ref "R243") (pin "1") (pinfunction "1_1") (pintype "passive"))
    )
    (net (code "88") (name "Net-(J1-PadC26)") (class "Default")
      (node (ref "J1") (pin "C26") (pinfunction "C26_C26") (pintype "passive"))
      (node (ref "J1") (pin "VC26") (pinfunction "C26_VC26") (pintype "passive"))
      (node (ref "R253") (pin "1") (pinfunction "1_1") (pintype "passive"))
    )
    (net (code "89") (name "Net-(J1-PadC27)") (class "Default")
      (node (ref "J1") (pin "C27") (pinfunction "C27_C27") (pintype "passive"))
      (node (ref "J1") (pin "VC27") (pinfunction "C27_VC27") (pintype "passive"))
      (node (ref "R263") (pin "1") (pinfunction "1_1") (pintype "passive"))
    )
    (net (code "90") (name "Net-(J1-PadC28)") (class "Default")
      (node (ref "J1") (pin "C28") (pinfunction "C28_C28") (pintype "passive"))
      (node (ref "J1") (pin "VC28") (pinfunction "C28_VC28") (pintype "passive"))
      (node (ref "R273") (pin "1") (pinfunction "1_1") (pintype "passive"))
    )
    (net (code "91") (name "Net-(J1-PadC29)") (class "Default")
      (node (ref "J1") (pin "C29") (pinfunction "C29_C29") (pintype "passive"))
      (node (ref "J1") (pin "VC29") (pinfunction "C29_VC29") (pintype "passive"))
      (node (ref "R283") (pin "1") (pinfunction "1_1") (pintype "passive"))
    )
    (net (code "92") (name "Net-(J1-PadC30)") (class "Default")
      (node (ref "J1") (pin "C30") (pinfunction "C30_C30") (pintype "passive"))
      (node (ref "J1") (pin "VC30") (pinfunction "C30_VC30") (pintype "passive"))
      (node (ref "R293") (pin "1") (pinfunction "1_1") (pintype "passive"))
    )
    (net (code "93") (name "Net-(J1-PadD01)") (class "Default")
      (node (ref "J1") (pin "D01") (pinfunction "D01_D01") (pintype "passive"))
      (node (ref "J1") (pin "VD01") (pinfunction "D01_VD01") (pintype "passive"))
      (node (ref "R4") (pin "2") (pinfunction "2_2") (pintype "passive"))
    )
    (net (code "94") (name "Net-(J1-PadD02)") (class "Default")
      (node (ref "J1") (pin "D02") (pinfunction "D02_D02") (pintype "passive"))
      (node (ref "J1") (pin "VD02") (pinfunction "D02_VD02") (pintype "passive"))
      (node (ref "R14") (pin "2") (pinfunction "2_2") (pintype "passive"))
    )
    (net (code "95") (name "Net-(J1-PadD03)") (class "Default")
      (node (ref "J1") (pin "D03") (pinfunction "D03_D03") (pintype "passive"))
      (node (ref "J1") (pin "VD03") (pinfunction "D03_VD03") (pintype "passive"))
      (node (ref "R24") (pin "2") (pinfunction "2_2") (pintype "passive"))
    )
    (net (code "96") (name "Net-(J1-PadD04)") (class "Default")
      (node (ref "J1") (pin "D04") (pinfunction "D04_D04") (pintype "passive"))
      (node (ref "J1") (pin "VD04") (pinfunction "D04_VD04") (pintype "passive"))
      (node (ref "R34") (pin "2") (pinfunction "2_2") (pintype "passive"))
    )
    (net (code "97") (name "Net-(J1-PadD05)") (class "Default")
      (node (ref "J1") (pin "D05") (pinfunction "D05_D05") (pintype "passive"))
      (node (ref "J1") (pin "VD05") (pinfunction "D05_VD05") (pintype "passive"))
      (node (ref "R44") (pin "2") (pinfunction "2_2") (pintype "passive"))
    )
    (net (code "98") (name "Net-(J1-PadD06)") (class "Default")
      (node (ref "J1") (pin "D06") (pinfunction "D06_D06") (pintype "passive"))
      (node (ref "J1") (pin "VD06") (pinfunction "D06_VD06") (pintype "passive"))
      (node (ref "R54") (pin "2") (pinfunction "2_2") (pintype "passive"))
    )
    (net (code "99") (name "Net-(J1-PadD07)") (class "Default")
      (node (ref "J1") (pin "D07") (pinfunction "D07_D07") (pintype "passive"))
      (node (ref "J1") (pin "VD07") (pinfunction "D07_VD07") (pintype "passive"))
      (node (ref "R64") (pin "2") (pinfunction "2_2") (pintype "passive"))
    )
    (net (code "100") (name "Net-(J1-PadD08)") (class "Default")
      (node (ref "J1") (pin "D08") (pinfunction "D08_D08") (pintype "passive"))
      (node (ref "J1") (pin "VD08") (pinfunction "D08_VD08") (pintype "passive"))
      (node (ref "R74") (pin "2") (pinfunction "2_2") (pintype "passive"))
    )
    (net (code "101") (name "Net-(J1-PadD09)") (class "Default")
      (node (ref "J1") (pin "D09") (pinfunction "D09_D09") (pintype "passive"))
      (node (ref "J1") (pin "VD09") (pinfunction "D09_VD09") (pintype "passive"))
      (node (ref "R84") (pin "2") (pinfunction "2_2") (pintype "passive"))
    )
    (net (code "102") (name "Net-(J1-PadD10)") (class "Default")
      (node (ref "J1") (pin "D10") (pinfunction "D10_D10") (pintype "passive"))
      (node (ref "J1") (pin "VD10") (pinfunction "D10_VD10") (pintype "passive"))
      (node (ref "R94") (pin "2") (pinfunction "2_2") (pintype "passive"))
    )
    (net (code "103") (name "Net-(J1-PadD11)") (class "Default")
      (node (ref "J1") (pin "D11") (pinfunction "D11_D11") (pintype "passive"))
      (node (ref "J1") (pin "VD11") (pinfunction "D11_VD11") (pintype "passive"))
      (node (ref "R104") (pin "2") (pinfunction "2_2") (pintype "passive"))
    )
    (net (code "104") (name "Net-(J1-PadD12)") (class "Default")
      (node (ref "J1") (pin "D12") (pinfunction "D12_D12") (pintype "passive"))
      (node (ref "J1") (pin "VD12") (pinfunction "D12_VD12") (pintype "passive"))
      (node (ref "R114") (pin "2") (pinfunction "2_2") (pintype "passive"))
    )
    (net (code "105") (name "Net-(J1-PadD13)") (class "Default")
      (node (ref "J1") (pin "D13") (pinfunction "D13_D13") (pintype "passive"))
      (node (ref "J1") (pin "VD13") (pinfunction "D13_VD13") (pintype "passive"))
      (node (ref "R124") (pin "2") (pinfunction "2_2") (pintype "passive"))
    )
    (net (code "106") (name "Net-(J1-PadD14)") (class "Default")
      (node (ref "J1") (pin "D14") (pinfunction "D14_D14") (pintype "passive"))
      (node (ref "J1") (pin "VD14") (pinfunction "D14_VD14") (pintype "passive"))
      (node (ref "R134") (pin "2") (pinfunction "2_2") (pintype "passive"))
    )
    (net (code "107") (name "Net-(J1-PadD15)") (class "Default")
      (node (ref "J1") (pin "D15") (pinfunction "D15_D15") (pintype "passive"))
      (node (ref "J1") (pin "VD15") (pinfunction "D15_VD15") (pintype "passive"))
      (node (ref "R144") (pin "2") (pinfunction "2_2") (pintype "passive"))
    )
    (net (code "108") (name "Net-(J1-PadD16)") (class "Default")
      (node (ref "J1") (pin "D16") (pinfunction "D16_D16") (pintype "passive"))
      (node (ref "J1") (pin "VD16") (pinfunction "D16_VD16") (pintype "passive"))
      (node (ref "R154") (pin "2") (pinfunction "2_2") (pintype "passive"))
    )
    (net (code "109") (name "Net-(J1-PadD17)") (class "Default")
      (node (ref "J1") (pin "D17") (pinfunction "D17_D17") (pintype "passive"))
      (node (ref "J1") (pin "VD17") (pinfunction "D17_VD17") (pintype "passive"))
      (node (ref "R164") (pin "2") (pinfunction "2_2") (pintype "passive"))
    )
    (net (code "110") (name "Net-(J1-PadD18)") (class "Default")
      (node (ref "J1") (pin "D18") (pinfunction "D18_D18") (pintype "passive"))
      (node (ref "J1") (pin "VD18") (pinfunction "D18_VD18") (pintype "passive"))
      (node (ref "R174") (pin "2") (pinfunction "2_2") (pintype "passive"))
    )
    (net (code "111") (name "Net-(J1-PadD19)") (class "Default")
      (node (ref "J1") (pin "D19") (pinfunction "D19_D19") (pintype "passive"))
      (node (ref "J1") (pin "VD19") (pinfunction "D19_VD19") (pintype "passive"))
      (node (ref "R184") (pin "2") (pinfunction "2_2") (pintype "passive"))
    )
    (net (code "112") (name "Net-(J1-PadD20)") (class "Default")
      (node (ref "J1") (pin "D20") (pinfunction "D20_D20") (pintype "passive"))
      (node (ref "J1") (pin "VD20") (pinfunction "D20_VD20") (pintype "passive"))
      (node (ref "R194") (pin "2") (pinfunction "2_2") (pintype "passive"))
    )
    (net (code "113") (name "Net-(J1-PadD21)") (class "Default")
      (node (ref "J1") (pin "D21") (pinfunction "D21_D21") (pintype "passive"))
      (node (ref "J1") (pin "VD21") (pinfunction "D21_VD21") (pintype "passive"))
      (node (ref "R204") (pin "2") (pinfunction "2_2") (pintype "passive"))
    )
    (net (code "114") (name "Net-(J1-PadD22)") (class "Default")
      (node (ref "J1") (pin "D22") (pinfunction "D22_D22") (pintype "passive"))
      (node (ref "J1") (pin "VD22") (pinfunction "D22_VD22") (pintype "passive"))
      (node (ref "R214") (pin "2") (pinfunction "2_2") (pintype "passive"))
    )
    (net (code "115") (name "Net-(J1-PadD23)") (class "Default")
      (node (ref "J1") (pin "D23") (pinfunction "D23_D23") (pintype "passive"))
      (node (ref "J1") (pin "VD23") (pinfunction "D23_VD23") (pintype "passive"))
      (node (ref "R224") (pin "2") (pinfunction "2_2") (pintype "passive"))
    )
    (net (code "116") (name "Net-(J1-PadD24)") (class "Default")
      (node (ref "J1") (pin "D24") (pinfunction "D24_D24") (pintype "passive"))
      (node (ref "J1") (pin "VD24") (pinfunction "D24_VD24") (pintype "passive"))
      (node (ref "R234") (pin "2") (pinfunction "2_2") (pintype "passive"))
    )
    (net (code "117") (name "Net-(J1-PadD25)") (class "Default")
      (node (ref "J1") (pin "D25") (pinfunction "D25_D25") (pintype "passive"))
      (node (ref "J1") (pin "VD25") (pinfunction "D25_VD25") (pintype "passive"))
      (node (ref "R244") (pin "2") (pinfunction "2_2") (pintype "passive"))
    )
    (net (code "118") (name "Net-(J1-PadD26)") (class "Default")
      (node (ref "J1") (pin "D26") (pinfunction "D26_D26") (pintype "passive"))
      (node (ref "J1") (pin "VD26") (pinfunction "D26_VD26") (pintype "passive"))
      (node (ref "R254") (pin "2") (pinfunction "2_2") (pintype "passive"))
    )
    (net (code "119") (name "Net-(J1-PadD27)") (class "Default")
      (node (ref "J1") (pin "D27") (pinfunction "D27_D27") (pintype "passive"))
      (node (ref "J1") (pin "VD27") (pinfunction "D27_VD27") (pintype "passive"))
      (node (ref "R264") (pin "2") (pinfunction "2_2") (pintype "passive"))
    )
    (net (code "120") (name "Net-(J1-PadD28)") (class "Default")
      (node (ref "J1") (pin "D28") (pinfunction "D28_D28") (pintype "passive"))
      (node (ref "J1") (pin "VD28") (pinfunction "D28_VD28") (pintype "passive"))
      (node (ref "R274") (pin "2") (pinfunction "2_2") (pintype "passive"))
    )
    (net (code "121") (name "Net-(J1-PadD29)") (class "Default")
      (node (ref "J1") (pin "D29") (pinfunction "D29_D29") (pintype "passive"))
      (node (ref "J1") (pin "VD29") (pinfunction "D29_VD29") (pintype "passive"))
      (node (ref "R284") (pin "2") (pinfunction "2_2") (pintype "passive"))
    )
    (net (code "122") (name "Net-(J1-PadD30)") (class "Default")
      (node (ref "J1") (pin "D30") (pinfunction "D30_D30") (pintype "passive"))
      (node (ref "J1") (pin "VD30") (pinfunction "D30_VD30") (pintype "passive"))
      (node (ref "R294") (pin "2") (pinfunction "2_2") (pintype "passive"))
    )
    (net (code "123") (name "Net-(J1-PadE01)") (class "Default")
      (node (ref "J1") (pin "E01") (pinfunction "E01_E01") (pintype "passive"))
      (node (ref "J1") (pin "VE01") (pinfunction "E01_VE01") (pintype "passive"))
      (node (ref "R5") (pin "1") (pinfunction "1_1") (pintype "passive"))
    )
    (net (code "124") (name "Net-(J1-PadE02)") (class "Default")
      (node (ref "J1") (pin "E02") (pinfunction "E02_E02") (pintype "passive"))
      (node (ref "J1") (pin "VE02") (pinfunction "E02_VE02") (pintype "passive"))
      (node (ref "R15") (pin "1") (pinfunction "1_1") (pintype "passive"))
    )
    (net (code "125") (name "Net-(J1-PadE03)") (class "Default")
      (node (ref "J1") (pin "E03") (pinfunction "E03_E03") (pintype "passive"))
      (node (ref "J1") (pin "VE03") (pinfunction "E03_VE03") (pintype "passive"))
      (node (ref "R25") (pin "1") (pinfunction "1_1") (pintype "passive"))
    )
    (net (code "126") (name "Net-(J1-PadE04)") (class "Default")
      (node (ref "J1") (pin "E04") (pinfunction "E04_E04") (pintype "passive"))
      (node (ref "J1") (pin "VE04") (pinfunction "E04_VE04") (pintype "passive"))
      (node (ref "R35") (pin "1") (pinfunction "1_1") (pintype "passive"))
    )
    (net (code "127") (name "Net-(J1-PadE05)") (class "Default")
      (node (ref "J1") (pin "E05") (pinfunction "E05_E05") (pintype "passive"))
      (node (ref "J1") (pin "VE05") (pinfunction "E05_VE05") (pintype "passive"))
      (node (ref "R45") (pin "1") (pinfunction "1_1") (pintype "passive"))
    )
    (net (code "128") (name "Net-(J1-PadE06)") (class "Default")
      (node (ref "J1") (pin "E06") (pinfunction "E06_E06") (pintype "passive"))
      (node (ref "J1") (pin "VE06") (pinfunction "E06_VE06") (pintype "passive"))
      (node (ref "R55") (pin "1") (pinfunction "1_1") (pintype "passive"))
    )
    (net (code "129") (name "Net-(J1-PadE07)") (class "Default")
      (node (ref "J1") (pin "E07") (pinfunction "E07_E07") (pintype "passive"))
      (node (ref "J1") (pin "VE07") (pinfunction "E07_VE07") (pintype "passive"))
      (node (ref "R65") (pin "1") (pinfunction "1_1") (pintype "passive"))
    )
    (net (code "130") (name "Net-(J1-PadE08)") (class "Default")
      (node (ref "J1") (pin "E08") (pinfunction "E08_E08") (pintype "passive"))
      (node (ref "J1") (pin "VE08") (pinfunction "E08_VE08") (pintype "passive"))
      (node (ref "R75") (pin "1") (pinfunction "1_1") (pintype "passive"))
    )
    (net (code "131") (name "Net-(J1-PadE09)") (class "Default")
      (node (ref "J1") (pin "E09") (pinfunction "E09_E09") (pintype "passive"))
      (node (ref "J1") (pin "VE09") (pinfunction "E09_VE09") (pintype "passive"))
      (node (ref "R85") (pin "1") (pinfunction "1_1") (pintype "passive"))
    )
    (net (code "132") (name "Net-(J1-PadE10)") (class "Default")
      (node (ref "J1") (pin "E10") (pinfunction "E10_E10") (pintype "passive"))
      (node (ref "J1") (pin "VE10") (pinfunction "E10_VE10") (pintype "passive"))
      (node (ref "R95") (pin "1") (pinfunction "1_1") (pintype "passive"))
    )
    (net (code "133") (name "Net-(J1-PadE11)") (class "Default")
      (node (ref "J1") (pin "E11") (pinfunction "E11_E11") (pintype "passive"))
      (node (ref "J1") (pin "VE11") (pinfunction "E11_VE11") (pintype "passive"))
      (node (ref "R105") (pin "1") (pinfunction "1_1") (pintype "passive"))
    )
    (net (code "134") (name "Net-(J1-PadE12)") (class "Default")
      (node (ref "J1") (pin "E12") (pinfunction "E12_E12") (pintype "passive"))
      (node (ref "J1") (pin "VE12") (pinfunction "E12_VE12") (pintype "passive"))
      (node (ref "R115") (pin "1") (pinfunction "1_1") (pintype "passive"))
    )
    (net (code "135") (name "Net-(J1-PadE13)") (class "Default")
      (node (ref "J1") (pin "E13") (pinfunction "E13_E13") (pintype "passive"))
      (node (ref "J1") (pin "VE13") (pinfunction "E13_VE13") (pintype "passive"))
      (node (ref "R125") (pin "1") (pinfunction "1_1") (pintype "passive"))
    )
    (net (code "136") (name "Net-(J1-PadE14)") (class "Default")
      (node (ref "J1") (pin "E14") (pinfunction "E14_E14") (pintype "passive"))
      (node (ref "J1") (pin "VE14") (pinfunction "E14_VE14") (pintype "passive"))
      (node (ref "R135") (pin "1") (pinfunction "1_1") (pintype "passive"))
    )
    (net (code "137") (name "Net-(J1-PadE15)") (class "Default")
      (node (ref "J1") (pin "E15") (pinfunction "E15_E15") (pintype "passive"))
      (node (ref "J1") (pin "VE15") (pinfunction "E15_VE15") (pintype "passive"))
      (node (ref "R145") (pin "1") (pinfunction "1_1") (pintype "passive"))
    )
    (net (code "138") (name "Net-(J1-PadE16)") (class "Default")
      (node (ref "J1") (pin "E16") (pinfunction "E16_E16") (pintype "passive"))
      (node (ref "J1") (pin "VE16") (pinfunction "E16_VE16") (pintype "passive"))
      (node (ref "R155") (pin "1") (pinfunction "1_1") (pintype "passive"))
    )
    (net (code "139") (name "Net-(J1-PadE17)") (class "Default")
      (node (ref "J1") (pin "E17") (pinfunction "E17_E17") (pintype "passive"))
      (node (ref "J1") (pin "VE17") (pinfunction "E17_VE17") (pintype "passive"))
      (node (ref "R165") (pin "1") (pinfunction "1_1") (pintype "passive"))
    )
    (net (code "140") (name "Net-(J1-PadE18)") (class "Default")
      (node (ref "J1") (pin "E18") (pinfunction "E18_E18") (pintype "passive"))
      (node (ref "J1") (pin "VE18") (pinfunction "E18_VE18") (pintype "passive"))
      (node (ref "R175") (pin "1") (pinfunction "1_1") (pintype "passive"))
    )
    (net (code "141") (name "Net-(J1-PadE19)") (class "Default")
      (node (ref "J1") (pin "E19") (pinfunction "E19_E19") (pintype "passive"))
      (node (ref "J1") (pin "VE19") (pinfunction "E19_VE19") (pintype "passive"))
      (node (ref "R185") (pin "1") (pinfunction "1_1") (pintype "passive"))
    )
    (net (code "142") (name "Net-(J1-PadE20)") (class "Default")
      (node (ref "J1") (pin "E20") (pinfunction "E20_E20") (pintype "passive"))
      (node (ref "J1") (pin "VE20") (pinfunction "E20_VE20") (pintype "passive"))
      (node (ref "R195") (pin "1") (pinfunction "1_1") (pintype "passive"))
    )
    (net (code "143") (name "Net-(J1-PadE21)") (class "Default")
      (node (ref "J1") (pin "E21") (pinfunction "E21_E21") (pintype "passive"))
      (node (ref "J1") (pin "VE21") (pinfunction "E21_VE21") (pintype "passive"))
      (node (ref "R205") (pin "1") (pinfunction "1_1") (pintype "passive"))
    )
    (net (code "144") (name "Net-(J1-PadE22)") (class "Default")
      (node (ref "J1") (pin "E22") (pinfunction "E22_E22") (pintype "passive"))
      (node (ref "J1") (pin "VE22") (pinfunction "E22_VE22") (pintype "passive"))
      (node (ref "R215") (pin "1") (pinfunction "1_1") (pintype "passive"))
    )
    (net (code "145") (name "Net-(J1-PadE23)") (class "Default")
      (node (ref "J1") (pin "E23") (pinfunction "E23_E23") (pintype "passive"))
      (node (ref "J1") (pin "VE23") (pinfunction "E23_VE23") (pintype "passive"))
      (node (ref "R225") (pin "1") (pinfunction "1_1") (pintype "passive"))
    )
    (net (code "146") (name "Net-(J1-PadE24)") (class "Default")
      (node (ref "J1") (pin "E24") (pinfunction "E24_E24") (pintype "passive"))
      (node (ref "J1") (pin "VE24") (pinfunction "E24_VE24") (pintype "passive"))
      (node (ref "R235") (pin "1") (pinfunction "1_1") (pintype "passive"))
    )
    (net (code "147") (name "Net-(J1-PadE25)") (class "Default")
      (node (ref "J1") (pin "E25") (pinfunction "E25_E25") (pintype "passive"))
      (node (ref "J1") (pin "VE25") (pinfunction "E25_VE25") (pintype "passive"))
      (node (ref "R245") (pin "1") (pinfunction "1_1") (pintype "passive"))
    )
    (net (code "148") (name "Net-(J1-PadE26)") (class "Default")
      (node (ref "J1") (pin "E26") (pinfunction "E26_E26") (pintype "passive"))
      (node (ref "J1") (pin "VE26") (pinfunction "E26_VE26") (pintype "passive"))
      (node (ref "R255") (pin "1") (pinfunction "1_1") (pintype "passive"))
    )
    (net (code "149") (name "Net-(J1-PadE27)") (class "Default")
      (node (ref "J1") (pin "E27") (pinfunction "E27_E27") (pintype "passive"))
      (node (ref "J1") (pin "VE27") (pinfunction "E27_VE27") (pintype "passive"))
      (node (ref "R265") (pin "1") (pinfunction "1_1") (pintype "passive"))
    )
    (net (code "150") (name "Net-(J1-PadE28)") (class "Default")
      (node (ref "J1") (pin "E28") (pinfunction "E28_E28") (pintype "passive"))
      (node (ref "J1") (pin "VE28") (pinfunction "E28_VE28") (pintype "passive"))
      (node (ref "R275") (pin "1") (pinfunction "1_1") (pintype "passive"))
    )
    (net (code "151") (name "Net-(J1-PadE29)") (class "Default")
      (node (ref "J1") (pin "E29") (pinfunction "E29_E29") (pintype "passive"))
      (node (ref "J1") (pin "VE29") (pinfunction "E29_VE29") (pintype "passive"))
      (node (ref "R285") (pin "1") (pinfunction "1_1") (pintype "passive"))
    )
    (net (code "152") (name "Net-(J1-PadE30)") (class "Default")
      (node (ref "J1") (pin "E30") (pinfunction "E30_E30") (pintype "passive"))
      (node (ref "J1") (pin "VE30") (pinfunction "E30_VE30") (pintype "passive"))
      (node (ref "R295") (pin "1") (pinfunction "1_1") (pintype "passive"))
    )
    (net (code "153") (name "Net-(J1-PadF01)") (class "Default")
      (node (ref "J1") (pin "F01") (pinfunction "F01_F01") (pintype "passive"))
      (node (ref "J1") (pin "VF01") (pinfunction "F01_VF01") (pintype "passive"))
      (node (ref "R6") (pin "2") (pinfunction "2_2") (pintype "passive"))
    )
    (net (code "154") (name "Net-(J1-PadF02)") (class "Default")
      (node (ref "J1") (pin "F02") (pinfunction "F02_F02") (pintype "passive"))
      (node (ref "J1") (pin "VF02") (pinfunction "F02_VF02") (pintype "passive"))
      (node (ref "R16") (pin "2") (pinfunction "2_2") (pintype "passive"))
    )
    (net (code "155") (name "Net-(J1-PadF03)") (class "Default")
      (node (ref "J1") (pin "F03") (pinfunction "F03_F03") (pintype "passive"))
      (node (ref "J1") (pin "VF03") (pinfunction "F03_VF03") (pintype "passive"))
      (node (ref "R26") (pin "2") (pinfunction "2_2") (pintype "passive"))
    )
    (net (code "156") (name "Net-(J1-PadF04)") (class "Default")
      (node (ref "J1") (pin "F04") (pinfunction "F04_F04") (pintype "passive"))
      (node (ref "J1") (pin "VF04") (pinfunction "F04_VF04") (pintype "passive"))
      (node (ref "R36") (pin "2") (pinfunction "2_2") (pintype "passive"))
    )
    (net (code "157") (name "Net-(J1-PadF05)") (class "Default")
      (node (ref "J1") (pin "F05") (pinfunction "F05_F05") (pintype "passive"))
      (node (ref "J1") (pin "VF05") (pinfunction "F05_VF05") (pintype "passive"))
      (node (ref "R46") (pin "2") (pinfunction "2_2") (pintype "passive"))
    )
    (net (code "158") (name "Net-(J1-PadF06)") (class "Default")
      (node (ref "J1") (pin "F06") (pinfunction "F06_F06") (pintype "passive"))
      (node (ref "J1") (pin "VF06") (pinfunction "F06_VF06") (pintype "passive"))
      (node (ref "R56") (pin "2") (pinfunction "2_2") (pintype "passive"))
    )
    (net (code "159") (name "Net-(J1-PadF07)") (class "Default")
      (node (ref "J1") (pin "F07") (pinfunction "F07_F07") (pintype "passive"))
      (node (ref "J1") (pin "VF07") (pinfunction "F07_VF07") (pintype "passive"))
      (node (ref "R66") (pin "2") (pinfunction "2_2") (pintype "passive"))
    )
    (net (code "160") (name "Net-(J1-PadF08)") (class "Default")
      (node (ref "J1") (pin "F08") (pinfunction "F08_F08") (pintype "passive"))
      (node (ref "J1") (pin "VF08") (pinfunction "F08_VF08") (pintype "passive"))
      (node (ref "R76") (pin "2") (pinfunction "2_2") (pintype "passive"))
    )
    (net (code "161") (name "Net-(J1-PadF09)") (class "Default")
      (node (ref "J1") (pin "F09") (pinfunction "F09_F09") (pintype "passive"))
      (node (ref "J1") (pin "VF09") (pinfunction "F09_VF09") (pintype "passive"))
      (node (ref "R86") (pin "2") (pinfunction "2_2") (pintype "passive"))
    )
    (net (code "162") (name "Net-(J1-PadF10)") (class "Default")
      (node (ref "J1") (pin "F10") (pinfunction "F10_F10") (pintype "passive"))
      (node (ref "J1") (pin "VF10") (pinfunction "F10_VF10") (pintype "passive"))
      (node (ref "R96") (pin "2") (pinfunction "2_2") (pintype "passive"))
    )
    (net (code "163") (name "Net-(J1-PadF11)") (class "Default")
      (node (ref "J1") (pin "F11") (pinfunction "F11_F11") (pintype "passive"))
      (node (ref "J1") (pin "VF11") (pinfunction "F11_VF11") (pintype "passive"))
      (node (ref "R106") (pin "2") (pinfunction "2_2") (pintype "passive"))
    )
    (net (code "164") (name "Net-(J1-PadF12)") (class "Default")
      (node (ref "J1") (pin "F12") (pinfunction "F12_F12") (pintype "passive"))
      (node (ref "J1") (pin "VF12") (pinfunction "F12_VF12") (pintype "passive"))
      (node (ref "R116") (pin "2") (pinfunction "2_2") (pintype "passive"))
    )
    (net (code "165") (name "Net-(J1-PadF13)") (class "Default")
      (node (ref "J1") (pin "F13") (pinfunction "F13_F13") (pintype "passive"))
      (node (ref "J1") (pin "VF13") (pinfunction "F13_VF13") (pintype "passive"))
      (node (ref "R126") (pin "2") (pinfunction "2_2") (pintype "passive"))
    )
    (net (code "166") (name "Net-(J1-PadF14)") (class "Default")
      (node (ref "J1") (pin "F14") (pinfunction "F14_F14") (pintype "passive"))
      (node (ref "J1") (pin "VF14") (pinfunction "F14_VF14") (pintype "passive"))
      (node (ref "R136") (pin "2") (pinfunction "2_2") (pintype "passive"))
    )
    (net (code "167") (name "Net-(J1-PadF15)") (class "Default")
      (node (ref "J1") (pin "F15") (pinfunction "F15_F15") (pintype "passive"))
      (node (ref "J1") (pin "VF15") (pinfunction "F15_VF15") (pintype "passive"))
      (node (ref "R146") (pin "2") (pinfunction "2_2") (pintype "passive"))
    )
    (net (code "168") (name "Net-(J1-PadF16)") (class "Default")
      (node (ref "J1") (pin "F16") (pinfunction "F16_F16") (pintype "passive"))
      (node (ref "J1") (pin "VF16") (pinfunction "F16_VF16") (pintype "passive"))
      (node (ref "R156") (pin "2") (pinfunction "2_2") (pintype "passive"))
    )
    (net (code "169") (name "Net-(J1-PadF17)") (class "Default")
      (node (ref "J1") (pin "F17") (pinfunction "F17_F17") (pintype "passive"))
      (node (ref "J1") (pin "VF17") (pinfunction "F17_VF17") (pintype "passive"))
      (node (ref "R166") (pin "2") (pinfunction "2_2") (pintype "passive"))
    )
    (net (code "170") (name "Net-(J1-PadF18)") (class "Default")
      (node (ref "J1") (pin "F18") (pinfunction "F18_F18") (pintype "passive"))
      (node (ref "J1") (pin "VF18") (pinfunction "F18_VF18") (pintype "passive"))
      (node (ref "R176") (pin "2") (pinfunction "2_2") (pintype "passive"))
    )
    (net (code "171") (name "Net-(J1-PadF19)") (class "Default")
      (node (ref "J1") (pin "F19") (pinfunction "F19_F19") (pintype "passive"))
      (node (ref "J1") (pin "VF19") (pinfunction "F19_VF19") (pintype "passive"))
      (node (ref "R186") (pin "2") (pinfunction "2_2") (pintype "passive"))
    )
    (net (code "172") (name "Net-(J1-PadF20)") (class "Default")
      (node (ref "J1") (pin "F20") (pinfunction "F20_F20") (pintype "passive"))
      (node (ref "J1") (pin "VF20") (pinfunction "F20_VF20") (pintype "passive"))
      (node (ref "R196") (pin "2") (pinfunction "2_2") (pintype "passive"))
    )
    (net (code "173") (name "Net-(J1-PadF21)") (class "Default")
      (node (ref "J1") (pin "F21") (pinfunction "F21_F21") (pintype "passive"))
      (node (ref "J1") (pin "VF21") (pinfunction "F21_VF21") (pintype "passive"))
      (node (ref "R206") (pin "2") (pinfunction "2_2") (pintype "passive"))
    )
    (net (code "174") (name "Net-(J1-PadF22)") (class "Default")
      (node (ref "J1") (pin "F22") (pinfunction "F22_F22") (pintype "passive"))
      (node (ref "J1") (pin "VF22") (pinfunction "F22_VF22") (pintype "passive"))
      (node (ref "R216") (pin "2") (pinfunction "2_2") (pintype "passive"))
    )
    (net (code "175") (name "Net-(J1-PadF23)") (class "Default")
      (node (ref "J1") (pin "F23") (pinfunction "F23_F23") (pintype "passive"))
      (node (ref "J1") (pin "VF23") (pinfunction "F23_VF23") (pintype "passive"))
      (node (ref "R226") (pin "2") (pinfunction "2_2") (pintype "passive"))
    )
    (net (code "176") (name "Net-(J1-PadF24)") (class "Default")
      (node (ref "J1") (pin "F24") (pinfunction "F24_F24") (pintype "passive"))
      (node (ref "J1") (pin "VF24") (pinfunction "F24_VF24") (pintype "passive"))
      (node (ref "R236") (pin "2") (pinfunction "2_2") (pintype "passive"))
    )
    (net (code "177") (name "Net-(J1-PadF25)") (class "Default")
      (node (ref "J1") (pin "F25") (pinfunction "F25_F25") (pintype "passive"))
      (node (ref "J1") (pin "VF25") (pinfunction "F25_VF25") (pintype "passive"))
      (node (ref "R246") (pin "2") (pinfunction "2_2") (pintype "passive"))
    )
    (net (code "178") (name "Net-(J1-PadF26)") (class "Default")
      (node (ref "J1") (pin "F26") (pinfunction "F26_F26") (pintype "passive"))
      (node (ref "J1") (pin "VF26") (pinfunction "F26_VF26") (pintype "passive"))
      (node (ref "R256") (pin "2") (pinfunction "2_2") (pintype "passive"))
    )
    (net (code "179") (name "Net-(J1-PadF27)") (class "Default")
      (node (ref "J1") (pin "F27") (pinfunction "F27_F27") (pintype "passive"))
      (node (ref "J1") (pin "VF27") (pinfunction "F27_VF27") (pintype "passive"))
      (node (ref "R266") (pin "2") (pinfunction "2_2") (pintype "passive"))
    )
    (net (code "180") (name "Net-(J1-PadF28)") (class "Default")
      (node (ref "J1") (pin "F28") (pinfunction "F28_F28") (pintype "passive"))
      (node (ref "J1") (pin "VF28") (pinfunction "F28_VF28") (pintype "passive"))
      (node (ref "R276") (pin "2") (pinfunction "2_2") (pintype "passive"))
    )
    (net (code "181") (name "Net-(J1-PadF29)") (class "Default")
      (node (ref "J1") (pin "F29") (pinfunction "F29_F29") (pintype "passive"))
      (node (ref "J1") (pin "VF29") (pinfunction "F29_VF29") (pintype "passive"))
      (node (ref "R286") (pin "2") (pinfunction "2_2") (pintype "passive"))
    )
    (net (code "182") (name "Net-(J1-PadF30)") (class "Default")
      (node (ref "J1") (pin "F30") (pinfunction "F30_F30") (pintype "passive"))
      (node (ref "J1") (pin "VF30") (pinfunction "F30_VF30") (pintype "passive"))
      (node (ref "R296") (pin "2") (pinfunction "2_2") (pintype "passive"))
    )
    (net (code "183") (name "Net-(J1-PadG01)") (class "Default")
      (node (ref "J1") (pin "G01") (pinfunction "G01_G01") (pintype "passive"))
      (node (ref "J1") (pin "VG01") (pinfunction "G01_VG01") (pintype "passive"))
      (node (ref "R7") (pin "1") (pinfunction "1_1") (pintype "passive"))
    )
    (net (code "184") (name "Net-(J1-PadG02)") (class "Default")
      (node (ref "J1") (pin "G02") (pinfunction "G02_G02") (pintype "passive"))
      (node (ref "J1") (pin "VG02") (pinfunction "G02_VG02") (pintype "passive"))
      (node (ref "R17") (pin "1") (pinfunction "1_1") (pintype "passive"))
    )
    (net (code "185") (name "Net-(J1-PadG03)") (class "Default")
      (node (ref "J1") (pin "G03") (pinfunction "G03_G03") (pintype "passive"))
      (node (ref "J1") (pin "VG03") (pinfunction "G03_VG03") (pintype "passive"))
      (node (ref "R27") (pin "1") (pinfunction "1_1") (pintype "passive"))
    )
    (net (code "186") (name "Net-(J1-PadG04)") (class "Default")
      (node (ref "J1") (pin "G04") (pinfunction "G04_G04") (pintype "passive"))
      (node (ref "J1") (pin "VG04") (pinfunction "G04_VG04") (pintype "passive"))
      (node (ref "R37") (pin "1") (pinfunction "1_1") (pintype "passive"))
    )
    (net (code "187") (name "Net-(J1-PadG05)") (class "Default")
      (node (ref "J1") (pin "G05") (pinfunction "G05_G05") (pintype "passive"))
      (node (ref "J1") (pin "VG05") (pinfunction "G05_VG05") (pintype "passive"))
      (node (ref "R47") (pin "1") (pinfunction "1_1") (pintype "passive"))
    )
    (net (code "188") (name "Net-(J1-PadG06)") (class "Default")
      (node (ref "J1") (pin "G06") (pinfunction "G06_G06") (pintype "passive"))
      (node (ref "J1") (pin "VG06") (pinfunction "G06_VG06") (pintype "passive"))
      (node (ref "R57") (pin "1") (pinfunction "1_1") (pintype "passive"))
    )
    (net (code "189") (name "Net-(J1-PadG07)") (class "Default")
      (node (ref "J1") (pin "G07") (pinfunction "G07_G07") (pintype "passive"))
      (node (ref "J1") (pin "VG07") (pinfunction "G07_VG07") (pintype "passive"))
      (node (ref "R67") (pin "1") (pinfunction "1_1") (pintype "passive"))
    )
    (net (code "190") (name "Net-(J1-PadG08)") (class "Default")
      (node (ref "J1") (pin "G08") (pinfunction "G08_G08") (pintype "passive"))
      (node (ref "J1") (pin "VG08") (pinfunction "G08_VG08") (pintype "passive"))
      (node (ref "R77") (pin "1") (pinfunction "1_1") (pintype "passive"))
    )
    (net (code "191") (name "Net-(J1-PadG09)") (class "Default")
      (node (ref "J1") (pin "G09") (pinfunction "G09_G09") (pintype "passive"))
      (node (ref "J1") (pin "VG09") (pinfunction "G09_VG09") (pintype "passive"))
      (node (ref "R87") (pin "1") (pinfunction "1_1") (pintype "passive"))
    )
    (net (code "192") (name "Net-(J1-PadG10)") (class "Default")
      (node (ref "J1") (pin "G10") (pinfunction "G10_G10") (pintype "passive"))
      (node (ref "J1") (pin "VG10") (pinfunction "G10_VG10") (pintype "passive"))
      (node (ref "R97") (pin "1") (pinfunction "1_1") (pintype "passive"))
    )
    (net (code "193") (name "Net-(J1-PadG11)") (class "Default")
      (node (ref "J1") (pin "G11") (pinfunction "G11_G11") (pintype "passive"))
      (node (ref "J1") (pin "VG11") (pinfunction "G11_VG11") (pintype "passive"))
      (node (ref "R107") (pin "1") (pinfunction "1_1") (pintype "passive"))
    )
    (net (code "194") (name "Net-(J1-PadG12)") (class "Default")
      (node (ref "J1") (pin "G12") (pinfunction "G12_G12") (pintype "passive"))
      (node (ref "J1") (pin "VG12") (pinfunction "G12_VG12") (pintype "passive"))
      (node (ref "R117") (pin "1") (pinfunction "1_1") (pintype "passive"))
    )
    (net (code "195") (name "Net-(J1-PadG13)") (class "Default")
      (node (ref "J1") (pin "G13") (pinfunction "G13_G13") (pintype "passive"))
      (node (ref "J1") (pin "VG13") (pinfunction "G13_VG13") (pintype "passive"))
      (node (ref "R127") (pin "1") (pinfunction "1_1") (pintype "passive"))
    )
    (net (code "196") (name "Net-(J1-PadG14)") (class "Default")
      (node (ref "J1") (pin "G14") (pinfunction "G14_G14") (pintype "passive"))
      (node (ref "J1") (pin "VG14") (pinfunction "G14_VG14") (pintype "passive"))
      (node (ref "R137") (pin "1") (pinfunction "1_1") (pintype "passive"))
    )
    (net (code "197") (name "Net-(J1-PadG15)") (class "Default")
      (node (ref "J1") (pin "G15") (pinfunction "G15_G15") (pintype "passive"))
      (node (ref "J1") (pin "VG15") (pinfunction "G15_VG15") (pintype "passive"))
      (node (ref "R147") (pin "1") (pinfunction "1_1") (pintype "passive"))
    )
    (net (code "198") (name "Net-(J1-PadG16)") (class "Default")
      (node (ref "J1") (pin "G16") (pinfunction "G16_G16") (pintype "passive"))
      (node (ref "J1") (pin "VG16") (pinfunction "G16_VG16") (pintype "passive"))
      (node (ref "R157") (pin "1") (pinfunction "1_1") (pintype "passive"))
    )
    (net (code "199") (name "Net-(J1-PadG17)") (class "Default")
      (node (ref "J1") (pin "G17") (pinfunction "G17_G17") (pintype "passive"))
      (node (ref "J1") (pin "VG17") (pinfunction "G17_VG17") (pintype "passive"))
      (node (ref "R167") (pin "1") (pinfunction "1_1") (pintype "passive"))
    )
    (net (code "200") (name "Net-(J1-PadG18)") (class "Default")
      (node (ref "J1") (pin "G18") (pinfunction "G18_G18") (pintype "passive"))
      (node (ref "J1") (pin "VG18") (pinfunction "G18_VG18") (pintype "passive"))
      (node (ref "R177") (pin "1") (pinfunction "1_1") (pintype "passive"))
    )
    (net (code "201") (name "Net-(J1-PadG19)") (class "Default")
      (node (ref "J1") (pin "G19") (pinfunction "G19_G19") (pintype "passive"))
      (node (ref "J1") (pin "VG19") (pinfunction "G19_VG19") (pintype "passive"))
      (node (ref "R187") (pin "1") (pinfunction "1_1") (pintype "passive"))
    )
    (net (code "202") (name "Net-(J1-PadG20)") (class "Default")
      (node (ref "J1") (pin "G20") (pinfunction "G20_G20") (pintype "passive"))
      (node (ref "J1") (pin "VG20") (pinfunction "G20_VG20") (pintype "passive"))
      (node (ref "R197") (pin "1") (pinfunction "1_1") (pintype "passive"))
    )
    (net (code "203") (name "Net-(J1-PadG21)") (class "Default")
      (node (ref "J1") (pin "G21") (pinfunction "G21_G21") (pintype "passive"))
      (node (ref "J1") (pin "VG21") (pinfunction "G21_VG21") (pintype "passive"))
      (node (ref "R207") (pin "1") (pinfunction "1_1") (pintype "passive"))
    )
    (net (code "204") (name "Net-(J1-PadG22)") (class "Default")
      (node (ref "J1") (pin "G22") (pinfunction "G22_G22") (pintype "passive"))
      (node (ref "J1") (pin "VG22") (pinfunction "G22_VG22") (pintype "passive"))
      (node (ref "R217") (pin "1") (pinfunction "1_1") (pintype "passive"))
    )
    (net (code "205") (name "Net-(J1-PadG23)") (class "Default")
      (node (ref "J1") (pin "G23") (pinfunction "G23_G23") (pintype "passive"))
      (node (ref "J1") (pin "VG23") (pinfunction "G23_VG23") (pintype "passive"))
      (node (ref "R227") (pin "1") (pinfunction "1_1") (pintype "passive"))
    )
    (net (code "206") (name "Net-(J1-PadG24)") (class "Default")
      (node (ref "J1") (pin "G24") (pinfunction "G24_G24") (pintype "passive"))
      (node (ref "J1") (pin "VG24") (pinfunction "G24_VG24") (pintype "passive"))
      (node (ref "R237") (pin "1") (pinfunction "1_1") (pintype "passive"))
    )
    (net (code "207") (name "Net-(J1-PadG25)") (class "Default")
      (node (ref "J1") (pin "G25") (pinfunction "G25_G25") (pintype "passive"))
      (node (ref "J1") (pin "VG25") (pinfunction "G25_VG25") (pintype "passive"))
      (node (ref "R247") (pin "1") (pinfunction "1_1") (pintype "passive"))
    )
    (net (code "208") (name "Net-(J1-PadG26)") (class "Default")
      (node (ref "J1") (pin "G26") (pinfunction "G26_G26") (pintype "passive"))
      (node (ref "J1") (pin "VG26") (pinfunction "G26_VG26") (pintype "passive"))
      (node (ref "R257") (pin "1") (pinfunction "1_1") (pintype "passive"))
    )
    (net (code "209") (name "Net-(J1-PadG27)") (class "Default")
      (node (ref "J1") (pin "G27") (pinfunction "G27_G27") (pintype "passive"))
      (node (ref "J1") (pin "VG27") (pinfunction "G27_VG27") (pintype "passive"))
      (node (ref "R267") (pin "1") (pinfunction "1_1") (pintype "passive"))
    )
    (net (code "210") (name "Net-(J1-PadG28)") (class "Default")
      (node (ref "J1") (pin "G28") (pinfunction "G28_G28") (pintype "passive"))
      (node (ref "J1") (pin "VG28") (pinfunction "G28_VG28") (pintype "passive"))
      (node (ref "R277") (pin "1") (pinfunction "1_1") (pintype "passive"))
    )
    (net (code "211") (name "Net-(J1-PadG29)") (class "Default")
      (node (ref "J1") (pin "G29") (pinfunction "G29_G29") (pintype "passive"))
      (node (ref "J1") (pin "VG29") (pinfunction "G29_VG29") (pintype "passive"))
      (node (ref "R287") (pin "1") (pinfunction "1_1") (pintype "passive"))
    )
    (net (code "212") (name "Net-(J1-PadG30)") (class "Default")
      (node (ref "J1") (pin "G30") (pinfunction "G30_G30") (pintype "passive"))
      (node (ref "J1") (pin "VG30") (pinfunction "G30_VG30") (pintype "passive"))
      (node (ref "R297") (pin "1") (pinfunction "1_1") (pintype "passive"))
    )
    (net (code "213") (name "Net-(J1-PadH01)") (class "Default")
      (node (ref "J1") (pin "H01") (pinfunction "H01_H01") (pintype "passive"))
      (node (ref "J1") (pin "VH01") (pinfunction "H01_VH01") (pintype "passive"))
      (node (ref "R8") (pin "2") (pinfunction "2_2") (pintype "passive"))
    )
    (net (code "214") (name "Net-(J1-PadH02)") (class "Default")
      (node (ref "J1") (pin "H02") (pinfunction "H02_H02") (pintype "passive"))
      (node (ref "J1") (pin "VH02") (pinfunction "H02_VH02") (pintype "passive"))
      (node (ref "R18") (pin "2") (pinfunction "2_2") (pintype "passive"))
    )
    (net (code "215") (name "Net-(J1-PadH03)") (class "Default")
      (node (ref "J1") (pin "H03") (pinfunction "H03_H03") (pintype "passive"))
      (node (ref "J1") (pin "VH03") (pinfunction "H03_VH03") (pintype "passive"))
      (node (ref "R28") (pin "2") (pinfunction "2_2") (pintype "passive"))
    )
    (net (code "216") (name "Net-(J1-PadH04)") (class "Default")
      (node (ref "J1") (pin "H04") (pinfunction "H04_H04") (pintype "passive"))
      (node (ref "J1") (pin "VH04") (pinfunction "H04_VH04") (pintype "passive"))
      (node (ref "R38") (pin "2") (pinfunction "2_2") (pintype "passive"))
    )
    (net (code "217") (name "Net-(J1-PadH05)") (class "Default")
      (node (ref "J1") (pin "H05") (pinfunction "H05_H05") (pintype "passive"))
      (node (ref "J1") (pin "VH05") (pinfunction "H05_VH05") (pintype "passive"))
      (node (ref "R48") (pin "2") (pinfunction "2_2") (pintype "passive"))
    )
    (net (code "218") (name "Net-(J1-PadH06)") (class "Default")
      (node (ref "J1") (pin "H06") (pinfunction "H06_H06") (pintype "passive"))
      (node (ref "J1") (pin "VH06") (pinfunction "H06_VH06") (pintype "passive"))
      (node (ref "R58") (pin "2") (pinfunction "2_2") (pintype "passive"))
    )
    (net (code "219") (name "Net-(J1-PadH07)") (class "Default")
      (node (ref "J1") (pin "H07") (pinfunction "H07_H07") (pintype "passive"))
      (node (ref "J1") (pin "VH07") (pinfunction "H07_VH07") (pintype "passive"))
      (node (ref "R68") (pin "2") (pinfunction "2_2") (pintype "passive"))
    )
    (net (code "220") (name "Net-(J1-PadH08)") (class "Default")
      (node (ref "J1") (pin "H08") (pinfunction "H08_H08") (pintype "passive"))
      (node (ref "J1") (pin "VH08") (pinfunction "H08_VH08") (pintype "passive"))
      (node (ref "R78") (pin "2") (pinfunction "2_2") (pintype "passive"))
    )
    (net (code "221") (name "Net-(J1-PadH09)") (class "Default")
      (node (ref "J1") (pin "H09") (pinfunction "H09_H09") (pintype "passive"))
      (node (ref "J1") (pin "VH09") (pinfunction "H09_VH09") (pintype "passive"))
      (node (ref "R88") (pin "2") (pinfunction "2_2") (pintype "passive"))
    )
    (net (code "222") (name "Net-(J1-PadH10)") (class "Default")
      (node (ref "J1") (pin "H10") (pinfunction "H10_H10") (pintype "passive"))
      (node (ref "J1") (pin "VH10") (pinfunction "H10_VH10") (pintype "passive"))
      (node (ref "R98") (pin "2") (pinfunction "2_2") (pintype "passive"))
    )
    (net (code "223") (name "Net-(J1-PadH11)") (class "Default")
      (node (ref "J1") (pin "H11") (pinfunction "H11_H11") (pintype "passive"))
      (node (ref "J1") (pin "VH11") (pinfunction "H11_VH11") (pintype "passive"))
      (node (ref "R108") (pin "2") (pinfunction "2_2") (pintype "passive"))
    )
    (net (code "224") (name "Net-(J1-PadH12)") (class "Default")
      (node (ref "J1") (pin "H12") (pinfunction "H12_H12") (pintype "passive"))
      (node (ref "J1") (pin "VH12") (pinfunction "H12_VH12") (pintype "passive"))
      (node (ref "R118") (pin "2") (pinfunction "2_2") (pintype "passive"))
    )
    (net (code "225") (name "Net-(J1-PadH13)") (class "Default")
      (node (ref "J1") (pin "H13") (pinfunction "H13_H13") (pintype "passive"))
      (node (ref "J1") (pin "VH13") (pinfunction "H13_VH13") (pintype "passive"))
      (node (ref "R128") (pin "2") (pinfunction "2_2") (pintype "passive"))
    )
    (net (code "226") (name "Net-(J1-PadH14)") (class "Default")
      (node (ref "J1") (pin "H14") (pinfunction "H14_H14") (pintype "passive"))
      (node (ref "J1") (pin "VH14") (pinfunction "H14_VH14") (pintype "passive"))
      (node (ref "R138") (pin "2") (pinfunction "2_2") (pintype "passive"))
    )
    (net (code "227") (name "Net-(J1-PadH15)") (class "Default")
      (node (ref "J1") (pin "H15") (pinfunction "H15_H15") (pintype "passive"))
      (node (ref "J1") (pin "VH15") (pinfunction "H15_VH15") (pintype "passive"))
      (node (ref "R148") (pin "2") (pinfunction "2_2") (pintype "passive"))
    )
    (net (code "228") (name "Net-(J1-PadH16)") (class "Default")
      (node (ref "J1") (pin "H16") (pinfunction "H16_H16") (pintype "passive"))
      (node (ref "J1") (pin "VH16") (pinfunction "H16_VH16") (pintype "passive"))
      (node (ref "R158") (pin "2") (pinfunction "2_2") (pintype "passive"))
    )
    (net (code "229") (name "Net-(J1-PadH17)") (class "Default")
      (node (ref "J1") (pin "H17") (pinfunction "H17_H17") (pintype "passive"))
      (node (ref "J1") (pin "VH17") (pinfunction "H17_VH17") (pintype "passive"))
      (node (ref "R168") (pin "2") (pinfunction "2_2") (pintype "passive"))
    )
    (net (code "230") (name "Net-(J1-PadH18)") (class "Default")
      (node (ref "J1") (pin "H18") (pinfunction "H18_H18") (pintype "passive"))
      (node (ref "J1") (pin "VH18") (pinfunction "H18_VH18") (pintype "passive"))
      (node (ref "R178") (pin "2") (pinfunction "2_2") (pintype "passive"))
    )
    (net (code "231") (name "Net-(J1-PadH19)") (class "Default")
      (node (ref "J1") (pin "H19") (pinfunction "H19_H19") (pintype "passive"))
      (node (ref "J1") (pin "VH19") (pinfunction "H19_VH19") (pintype "passive"))
      (node (ref "R188") (pin "2") (pinfunction "2_2") (pintype "passive"))
    )
    (net (code "232") (name "Net-(J1-PadH20)") (class "Default")
      (node (ref "J1") (pin "H20") (pinfunction "H20_H20") (pintype "passive"))
      (node (ref "J1") (pin "VH20") (pinfunction "H20_VH20") (pintype "passive"))
      (node (ref "R198") (pin "2") (pinfunction "2_2") (pintype "passive"))
    )
    (net (code "233") (name "Net-(J1-PadH21)") (class "Default")
      (node (ref "J1") (pin "H21") (pinfunction "H21_H21") (pintype "passive"))
      (node (ref "J1") (pin "VH21") (pinfunction "H21_VH21") (pintype "passive"))
      (node (ref "R208") (pin "2") (pinfunction "2_2") (pintype "passive"))
    )
    (net (code "234") (name "Net-(J1-PadH22)") (class "Default")
      (node (ref "J1") (pin "H22") (pinfunction "H22_H22") (pintype "passive"))
      (node (ref "J1") (pin "VH22") (pinfunction "H22_VH22") (pintype "passive"))
      (node (ref "R218") (pin "2") (pinfunction "2_2") (pintype "passive"))
    )
    (net (code "235") (name "Net-(J1-PadH23)") (class "Default")
      (node (ref "J1") (pin "H23") (pinfunction "H23_H23") (pintype "passive"))
      (node (ref "J1") (pin "VH23") (pinfunction "H23_VH23") (pintype "passive"))
      (node (ref "R228") (pin "2") (pinfunction "2_2") (pintype "passive"))
    )
    (net (code "236") (name "Net-(J1-PadH24)") (class "Default")
      (node (ref "J1") (pin "H24") (pinfunction "H24_H24") (pintype "passive"))
      (node (ref "J1") (pin "VH24") (pinfunction "H24_VH24") (pintype "passive"))
      (node (ref "R238") (pin "2") (pinfunction "2_2") (pintype "passive"))
    )
    (net (code "237") (name "Net-(J1-PadH25)") (class "Default")
      (node (ref "J1") (pin "H25") (pinfunction "H25_H25") (pintype "passive"))
      (node (ref "J1") (pin "VH25") (pinfunction "H25_VH25") (pintype "passive"))
      (node (ref "R248") (pin "2") (pinfunction "2_2") (pintype "passive"))
    )
    (net (code "238") (name "Net-(J1-PadH26)") (class "Default")
      (node (ref "J1") (pin "H26") (pinfunction "H26_H26") (pintype "passive"))
      (node (ref "J1") (pin "VH26") (pinfunction "H26_VH26") (pintype "passive"))
      (node (ref "R258") (pin "2") (pinfunction "2_2") (pintype "passive"))
    )
    (net (code "239") (name "Net-(J1-PadH27)") (class "Default")
      (node (ref "J1") (pin "H27") (pinfunction "H27_H27") (pintype "passive"))
      (node (ref "J1") (pin "VH27") (pinfunction "H27_VH27") (pintype "passive"))
      (node (ref "R268") (pin "2") (pinfunction "2_2") (pintype "passive"))
    )
    (net (code "240") (name "Net-(J1-PadH28)") (class "Default")
      (node (ref "J1") (pin "H28") (pinfunction "H28_H28") (pintype "passive"))
      (node (ref "J1") (pin "VH28") (pinfunction "H28_VH28") (pintype "passive"))
      (node (ref "R278") (pin "2") (pinfunction "2_2") (pintype "passive"))
    )
    (net (code "241") (name "Net-(J1-PadH29)") (class "Default")
      (node (ref "J1") (pin "H29") (pinfunction "H29_H29") (pintype "passive"))
      (node (ref "J1") (pin "VH29") (pinfunction "H29_VH29") (pintype "passive"))
      (node (ref "R288") (pin "2") (pinfunction "2_2") (pintype "passive"))
    )
    (net (code "242") (name "Net-(J1-PadH30)") (class "Default")
      (node (ref "J1") (pin "H30") (pinfunction "H30_H30") (pintype "passive"))
      (node (ref "J1") (pin "VH30") (pinfunction "H30_VH30") (pintype "passive"))
      (node (ref "R298") (pin "2") (pinfunction "2_2") (pintype "passive"))
    )
    (net (code "243") (name "Net-(J1-PadI01)") (class "Default")
      (node (ref "J1") (pin "I01") (pinfunction "I01_I01") (pintype "passive"))
      (node (ref "J1") (pin "VI01") (pinfunction "I01_VI01") (pintype "passive"))
      (node (ref "R9") (pin "1") (pinfunction "1_1") (pintype "passive"))
    )
    (net (code "244") (name "Net-(J1-PadI02)") (class "Default")
      (node (ref "J1") (pin "I02") (pinfunction "I02_I02") (pintype "passive"))
      (node (ref "J1") (pin "VI02") (pinfunction "I02_VI02") (pintype "passive"))
      (node (ref "R19") (pin "1") (pinfunction "1_1") (pintype "passive"))
    )
    (net (code "245") (name "Net-(J1-PadI03)") (class "Default")
      (node (ref "J1") (pin "I03") (pinfunction "I03_I03") (pintype "passive"))
      (node (ref "J1") (pin "VI03") (pinfunction "I03_VI03") (pintype "passive"))
      (node (ref "R29") (pin "1") (pinfunction "1_1") (pintype "passive"))
    )
    (net (code "246") (name "Net-(J1-PadI04)") (class "Default")
      (node (ref "J1") (pin "I04") (pinfunction "I04_I04") (pintype "passive"))
      (node (ref "J1") (pin "VI04") (pinfunction "I04_VI04") (pintype "passive"))
      (node (ref "R39") (pin "1") (pinfunction "1_1") (pintype "passive"))
    )
    (net (code "247") (name "Net-(J1-PadI05)") (class "Default")
      (node (ref "J1") (pin "I05") (pinfunction "I05_I05") (pintype "passive"))
      (node (ref "J1") (pin "VI05") (pinfunction "I05_VI05") (pintype "passive"))
      (node (ref "R49") (pin "1") (pinfunction "1_1") (pintype "passive"))
    )
    (net (code "248") (name "Net-(J1-PadI06)") (class "Default")
      (node (ref "J1") (pin "I06") (pinfunction "I06_I06") (pintype "passive"))
      (node (ref "J1") (pin "VI06") (pinfunction "I06_VI06") (pintype "passive"))
      (node (ref "R59") (pin "1") (pinfunction "1_1") (pintype "passive"))
    )
    (net (code "249") (name "Net-(J1-PadI07)") (class "Default")
      (node (ref "J1") (pin "I07") (pinfunction "I07_I07") (pintype "passive"))
      (node (ref "J1") (pin "VI07") (pinfunction "I07_VI07") (pintype "passive"))
      (node (ref "R69") (pin "1") (pinfunction "1_1") (pintype "passive"))
    )
    (net (code "250") (name "Net-(J1-PadI08)") (class "Default")
      (node (ref "J1") (pin "I08") (pinfunction "I08_I08") (pintype "passive"))
      (node (ref "J1") (pin "VI08") (pinfunction "I08_VI08") (pintype "passive"))
      (node (ref "R79") (pin "1") (pinfunction "1_1") (pintype "passive"))
    )
    (net (code "251") (name "Net-(J1-PadI09)") (class "Default")
      (node (ref "J1") (pin "I09") (pinfunction "I09_I09") (pintype "passive"))
      (node (ref "J1") (pin "VI09") (pinfunction "I09_VI09") (pintype "passive"))
      (node (ref "R89") (pin "1") (pinfunction "1_1") (pintype "passive"))
    )
    (net (code "252") (name "Net-(J1-PadI10)") (class "Default")
      (node (ref "J1") (pin "I10") (pinfunction "I10_I10") (pintype "passive"))
      (node (ref "J1") (pin "VI10") (pinfunction "I10_VI10") (pintype "passive"))
      (node (ref "R99") (pin "1") (pinfunction "1_1") (pintype "passive"))
    )
    (net (code "253") (name "Net-(J1-PadI11)") (class "Default")
      (node (ref "J1") (pin "I11") (pinfunction "I11_I11") (pintype "passive"))
      (node (ref "J1") (pin "VI11") (pinfunction "I11_VI11") (pintype "passive"))
      (node (ref "R109") (pin "1") (pinfunction "1_1") (pintype "passive"))
    )
    (net (code "254") (name "Net-(J1-PadI12)") (class "Default")
      (node (ref "J1") (pin "I12") (pinfunction "I12_I12") (pintype "passive"))
      (node (ref "J1") (pin "VI12") (pinfunction "I12_VI12") (pintype "passive"))
      (node (ref "R119") (pin "1") (pinfunction "1_1") (pintype "passive"))
    )
    (net (code "255") (name "Net-(J1-PadI13)") (class "Default")
      (node (ref "J1") (pin "I13") (pinfunction "I13_I13") (pintype "passive"))
      (node (ref "J1") (pin "VI13") (pinfunction "I13_VI13") (pintype "passive"))
      (node (ref "R129") (pin "1") (pinfunction "1_1") (pintype "passive"))
    )
    (net (code "256") (name "Net-(J1-PadI14)") (class "Default")
      (node (ref "J1") (pin "I14") (pinfunction "I14_I14") (pintype "passive"))
      (node (ref "J1") (pin "VI14") (pinfunction "I14_VI14") (pintype "passive"))
      (node (ref "R139") (pin "1") (pinfunction "1_1") (pintype "passive"))
    )
    (net (code "257") (name "Net-(J1-PadI15)") (class "Default")
      (node (ref "J1") (pin "I15") (pinfunction "I15_I15") (pintype "passive"))
      (node (ref "J1") (pin "VI15") (pinfunction "I15_VI15") (pintype "passive"))
      (node (ref "R149") (pin "1") (pinfunction "1_1") (pintype "passive"))
    )
    (net (code "258") (name "Net-(J1-PadI16)") (class "Default")
      (node (ref "J1") (pin "I16") (pinfunction "I16_I16") (pintype "passive"))
      (node (ref "J1") (pin "VI16") (pinfunction "I16_VI16") (pintype "passive"))
      (node (ref "R159") (pin "1") (pinfunction "1_1") (pintype "passive"))
    )
    (net (code "259") (name "Net-(J1-PadI17)") (class "Default")
      (node (ref "J1") (pin "I17") (pinfunction "I17_I17") (pintype "passive"))
      (node (ref "J1") (pin "VI17") (pinfunction "I17_VI17") (pintype "passive"))
      (node (ref "R169") (pin "1") (pinfunction "1_1") (pintype "passive"))
    )
    (net (code "260") (name "Net-(J1-PadI18)") (class "Default")
      (node (ref "J1") (pin "I18") (pinfunction "I18_I18") (pintype "passive"))
      (node (ref "J1") (pin "VI18") (pinfunction "I18_VI18") (pintype "passive"))
      (node (ref "R179") (pin "1") (pinfunction "1_1") (pintype "passive"))
    )
    (net (code "261") (name "Net-(J1-PadI19)") (class "Default")
      (node (ref "J1") (pin "I19") (pinfunction "I19_I19") (pintype "passive"))
      (node (ref "J1") (pin "VI19") (pinfunction "I19_VI19") (pintype "passive"))
      (node (ref "R189") (pin "1") (pinfunction "1_1") (pintype "passive"))
    )
    (net (code "262") (name "Net-(J1-PadI20)") (class "Default")
      (node (ref "J1") (pin "I20") (pinfunction "I20_I20") (pintype "passive"))
      (node (ref "J1") (pin "VI20") (pinfunction "I20_VI20") (pintype "passive"))
      (node (ref "R199") (pin "1") (pinfunction "1_1") (pintype "passive"))
    )
    (net (code "263") (name "Net-(J1-PadI21)") (class "Default")
      (node (ref "J1") (pin "I21") (pinfunction "I21_I21") (pintype "passive"))
      (node (ref "J1") (pin "VI21") (pinfunction "I21_VI21") (pintype "passive"))
      (node (ref "R209") (pin "1") (pinfunction "1_1") (pintype "passive"))
    )
    (net (code "264") (name "Net-(J1-PadI22)") (class "Default")
      (node (ref "J1") (pin "I22") (pinfunction "I22_I22") (pintype "passive"))
      (node (ref "J1") (pin "VI22") (pinfunction "I22_VI22") (pintype "passive"))
      (node (ref "R219") (pin "1") (pinfunction "1_1") (pintype "passive"))
    )
    (net (code "265") (name "Net-(J1-PadI23)") (class "Default")
      (node (ref "J1") (pin "I23") (pinfunction "I23_I23") (pintype "passive"))
      (node (ref "J1") (pin "VI23") (pinfunction "I23_VI23") (pintype "passive"))
      (node (ref "R229") (pin "1") (pinfunction "1_1") (pintype "passive"))
    )
    (net (code "266") (name "Net-(J1-PadI24)") (class "Default")
      (node (ref "J1") (pin "I24") (pinfunction "I24_I24") (pintype "passive"))
      (node (ref "J1") (pin "VI24") (pinfunction "I24_VI24") (pintype "passive"))
      (node (ref "R239") (pin "1") (pinfunction "1_1") (pintype "passive"))
    )
    (net (code "267") (name "Net-(J1-PadI25)") (class "Default")
      (node (ref "J1") (pin "I25") (pinfunction "I25_I25") (pintype "passive"))
      (node (ref "J1") (pin "VI25") (pinfunction "I25_VI25") (pintype "passive"))
      (node (ref "R249") (pin "1") (pinfunction "1_1") (pintype "passive"))
    )
    (net (code "268") (name "Net-(J1-PadI26)") (class "Default")
      (node (ref "J1") (pin "I26") (pinfunction "I26_I26") (pintype "passive"))
      (node (ref "J1") (pin "VI26") (pinfunction "I26_VI26") (pintype "passive"))
      (node (ref "R259") (pin "1") (pinfunction "1_1") (pintype "passive"))
    )
    (net (code "269") (name "Net-(J1-PadI27)") (class "Default")
      (node (ref "J1") (pin "I27") (pinfunction "I27_I27") (pintype "passive"))
      (node (ref "J1") (pin "VI27") (pinfunction "I27_VI27") (pintype "passive"))
      (node (ref "R269") (pin "1") (pinfunction "1_1") (pintype "passive"))
    )
    (net (code "270") (name "Net-(J1-PadI28)") (class "Default")
      (node (ref "J1") (pin "I28") (pinfunction "I28_I28") (pintype "passive"))
      (node (ref "J1") (pin "VI28") (pinfunction "I28_VI28") (pintype "passive"))
      (node (ref "R279") (pin "1") (pinfunction "1_1") (pintype "passive"))
    )
    (net (code "271") (name "Net-(J1-PadI29)") (class "Default")
      (node (ref "J1") (pin "I29") (pinfunction "I29_I29") (pintype "passive"))
      (node (ref "J1") (pin "VI29") (pinfunction "I29_VI29") (pintype "passive"))
      (node (ref "R289") (pin "1") (pinfunction "1_1") (pintype "passive"))
    )
    (net (code "272") (name "Net-(J1-PadI30)") (class "Default")
      (node (ref "J1") (pin "I30") (pinfunction "I30_I30") (pintype "passive"))
      (node (ref "J1") (pin "VI30") (pinfunction "I30_VI30") (pintype "passive"))
      (node (ref "R299") (pin "1") (pinfunction "1_1") (pintype "passive"))
    )
    (net (code "273") (name "Net-(J1-PadJ01)") (class "Default")
      (node (ref "J1") (pin "J01") (pinfunction "J01_J01") (pintype "passive"))
      (node (ref "J1") (pin "VJ01") (pinfunction "J01_VJ01") (pintype "passive"))
      (node (ref "R10") (pin "2") (pinfunction "2_2") (pintype "passive"))
    )
    (net (code "274") (name "Net-(J1-PadJ02)") (class "Default")
      (node (ref "J1") (pin "J02") (pinfunction "J02_J02") (pintype "passive"))
      (node (ref "J1") (pin "VJ02") (pinfunction "J02_VJ02") (pintype "passive"))
      (node (ref "R20") (pin "2") (pinfunction "2_2") (pintype "passive"))
    )
    (net (code "275") (name "Net-(J1-PadJ03)") (class "Default")
      (node (ref "J1") (pin "J03") (pinfunction "J03_J03") (pintype "passive"))
      (node (ref "J1") (pin "VJ03") (pinfunction "J03_VJ03") (pintype "passive"))
      (node (ref "R30") (pin "2") (pinfunction "2_2") (pintype "passive"))
    )
    (net (code "276") (name "Net-(J1-PadJ04)") (class "Default")
      (node (ref "J1") (pin "J04") (pinfunction "J04_J04") (pintype "passive"))
      (node (ref "J1") (pin "VJ04") (pinfunction "J04_VJ04") (pintype "passive"))
      (node (ref "R40") (pin "2") (pinfunction "2_2") (pintype "passive"))
    )
    (net (code "277") (name "Net-(J1-PadJ05)") (class "Default")
      (node (ref "J1") (pin "J05") (pinfunction "J05_J05") (pintype "passive"))
      (node (ref "J1") (pin "VJ05") (pinfunction "J05_VJ05") (pintype "passive"))
      (node (ref "R50") (pin "2") (pinfunction "2_2") (pintype "passive"))
    )
    (net (code "278") (name "Net-(J1-PadJ06)") (class "Default")
      (node (ref "J1") (pin "J06") (pinfunction "J06_J06") (pintype "passive"))
      (node (ref "J1") (pin "VJ06") (pinfunction "J06_VJ06") (pintype "passive"))
      (node (ref "R60") (pin "2") (pinfunction "2_2") (pintype "passive"))
    )
    (net (code "279") (name "Net-(J1-PadJ07)") (class "Default")
      (node (ref "J1") (pin "J07") (pinfunction "J07_J07") (pintype "passive"))
      (node (ref "J1") (pin "VJ07") (pinfunction "J07_VJ07") (pintype "passive"))
      (node (ref "R70") (pin "2") (pinfunction "2_2") (pintype "passive"))
    )
    (net (code "280") (name "Net-(J1-PadJ08)") (class "Default")
      (node (ref "J1") (pin "J08") (pinfunction "J08_J08") (pintype "passive"))
      (node (ref "J1") (pin "VJ08") (pinfunction "J08_VJ08") (pintype "passive"))
      (node (ref "R80") (pin "2") (pinfunction "2_2") (pintype "passive"))
    )
    (net (code "281") (name "Net-(J1-PadJ09)") (class "Default")
      (node (ref "J1") (pin "J09") (pinfunction "J09_J09") (pintype "passive"))
      (node (ref "J1") (pin "VJ09") (pinfunction "J09_VJ09") (pintype "passive"))
      (node (ref "R90") (pin "2") (pinfunction "2_2") (pintype "passive"))
    )
    (net (code "282") (name "Net-(J1-PadJ10)") (class "Default")
      (node (ref "J1") (pin "J10") (pinfunction "J10_J10") (pintype "passive"))
      (node (ref "J1") (pin "VJ10") (pinfunction "J10_VJ10") (pintype "passive"))
      (node (ref "R100") (pin "2") (pinfunction "2_2") (pintype "passive"))
    )
    (net (code "283") (name "Net-(J1-PadJ11)") (class "Default")
      (node (ref "J1") (pin "J11") (pinfunction "J11_J11") (pintype "passive"))
      (node (ref "J1") (pin "VJ11") (pinfunction "J11_VJ11") (pintype "passive"))
      (node (ref "R110") (pin "2") (pinfunction "2_2") (pintype "passive"))
    )
    (net (code "284") (name "Net-(J1-PadJ12)") (class "Default")
      (node (ref "J1") (pin "J12") (pinfunction "J12_J12") (pintype "passive"))
      (node (ref "J1") (pin "VJ12") (pinfunction "J12_VJ12") (pintype "passive"))
      (node (ref "R120") (pin "2") (pinfunction "2_2") (pintype "passive"))
    )
    (net (code "285") (name "Net-(J1-PadJ13)") (class "Default")
      (node (ref "J1") (pin "J13") (pinfunction "J13_J13") (pintype "passive"))
      (node (ref "J1") (pin "VJ13") (pinfunction "J13_VJ13") (pintype "passive"))
      (node (ref "R130") (pin "2") (pinfunction "2_2") (pintype "passive"))
    )
    (net (code "286") (name "Net-(J1-PadJ14)") (class "Default")
      (node (ref "J1") (pin "J14") (pinfunction "J14_J14") (pintype "passive"))
      (node (ref "J1") (pin "VJ14") (pinfunction "J14_VJ14") (pintype "passive"))
      (node (ref "R140") (pin "2") (pinfunction "2_2") (pintype "passive"))
    )
    (net (code "287") (name "Net-(J1-PadJ15)") (class "Default")
      (node (ref "J1") (pin "J15") (pinfunction "J15_J15") (pintype "passive"))
      (node (ref "J1") (pin "VJ15") (pinfunction "J15_VJ15") (pintype "passive"))
      (node (ref "R150") (pin "2") (pinfunction "2_2") (pintype "passive"))
    )
    (net (code "288") (name "Net-(J1-PadJ16)") (class "Default")
      (node (ref "J1") (pin "J16") (pinfunction "J16_J16") (pintype "passive"))
      (node (ref "J1") (pin "VJ16") (pinfunction "J16_VJ16") (pintype "passive"))
      (node (ref "R160") (pin "2") (pinfunction "2_2") (pintype "passive"))
    )
    (net (code "289") (name "Net-(J1-PadJ17)") (class "Default")
      (node (ref "J1") (pin "J17") (pinfunction "J17_J17") (pintype "passive"))
      (node (ref "J1") (pin "VJ17") (pinfunction "J17_VJ17") (pintype "passive"))
      (node (ref "R170") (pin "2") (pinfunction "2_2") (pintype "passive"))
    )
    (net (code "290") (name "Net-(J1-PadJ18)") (class "Default")
      (node (ref "J1") (pin "J18") (pinfunction "J18_J18") (pintype "passive"))
      (node (ref "J1") (pin "VJ18") (pinfunction "J18_VJ18") (pintype "passive"))
      (node (ref "R180") (pin "2") (pinfunction "2_2") (pintype "passive"))
    )
    (net (code "291") (name "Net-(J1-PadJ19)") (class "Default")
      (node (ref "J1") (pin "J19") (pinfunction "J19_J19") (pintype "passive"))
      (node (ref "J1") (pin "VJ19") (pinfunction "J19_VJ19") (pintype "passive"))
      (node (ref "R190") (pin "2") (pinfunction "2_2") (pintype "passive"))
    )
    (net (code "292") (name "Net-(J1-PadJ20)") (class "Default")
      (node (ref "J1") (pin "J20") (pinfunction "J20_J20") (pintype "passive"))
      (node (ref "J1") (pin "VJ20") (pinfunction "J20_VJ20") (pintype "passive"))
      (node (ref "R200") (pin "2") (pinfunction "2_2") (pintype "passive"))
    )
    (net (code "293") (name "Net-(J1-PadJ21)") (class "Default")
      (node (ref "J1") (pin "J21") (pinfunction "J21_J21") (pintype "passive"))
      (node (ref "J1") (pin "VJ21") (pinfunction "J21_VJ21") (pintype "passive"))
      (node (ref "R210") (pin "2") (pinfunction "2_2") (pintype "passive"))
    )
    (net (code "294") (name "Net-(J1-PadJ22)") (class "Default")
      (node (ref "J1") (pin "J22") (pinfunction "J22_J22") (pintype "passive"))
      (node (ref "J1") (pin "VJ22") (pinfunction "J22_VJ22") (pintype "passive"))
      (node (ref "R220") (pin "2") (pinfunction "2_2") (pintype "passive"))
    )
    (net (code "295") (name "Net-(J1-PadJ23)") (class "Default")
      (node (ref "J1") (pin "J23") (pinfunction "J23_J23") (pintype "passive"))
      (node (ref "J1") (pin "VJ23") (pinfunction "J23_VJ23") (pintype "passive"))
      (node (ref "R230") (pin "2") (pinfunction "2_2") (pintype "passive"))
    )
    (net (code "296") (name "Net-(J1-PadJ24)") (class "Default")
      (node (ref "J1") (pin "J24") (pinfunction "J24_J24") (pintype "passive"))
      (node (ref "J1") (pin "VJ24") (pinfunction "J24_VJ24") (pintype "passive"))
      (node (ref "R240") (pin "2") (pinfunction "2_2") (pintype "passive"))
    )
    (net (code "297") (name "Net-(J1-PadJ25)") (class "Default")
      (node (ref "J1") (pin "J25") (pinfunction "J25_J25") (pintype "passive"))
      (node (ref "J1") (pin "VJ25") (pinfunction "J25_VJ25") (pintype "passive"))
      (node (ref "R250") (pin "2") (pinfunction "2_2") (pintype "passive"))
    )
    (net (code "298") (name "Net-(J1-PadJ26)") (class "Default")
      (node (ref "J1") (pin "J26") (pinfunction "J26_J26") (pintype "passive"))
      (node (ref "J1") (pin "VJ26") (pinfunction "J26_VJ26") (pintype "passive"))
      (node (ref "R260") (pin "2") (pinfunction "2_2") (pintype "passive"))
    )
    (net (code "299") (name "Net-(J1-PadJ27)") (class "Default")
      (node (ref "J1") (pin "J27") (pinfunction "J27_J27") (pintype "passive"))
      (node (ref "J1") (pin "VJ27") (pinfunction "J27_VJ27") (pintype "passive"))
      (node (ref "R270") (pin "2") (pinfunction "2_2") (pintype "passive"))
    )
    (net (code "300") (name "Net-(J1-PadJ28)") (class "Default")
      (node (ref "J1") (pin "J28") (pinfunction "J28_J28") (pintype "passive"))
      (node (ref "J1") (pin "VJ28") (pinfunction "J28_VJ28") (pintype "passive"))
      (node (ref "R280") (pin "2") (pinfunction "2_2") (pintype "passive"))
    )
    (net (code "301") (name "Net-(J1-PadJ29)") (class "Default")
      (node (ref "J1") (pin "J29") (pinfunction "J29_J29") (pintype "passive"))
      (node (ref "J1") (pin "VJ29") (pinfunction "J29_VJ29") (pintype "passive"))
      (node (ref "R290") (pin "2") (pinfunction "2_2") (pintype "passive"))
    )
    (net (code "302") (name "Net-(J1-PadJ30)") (class "Default")
      (node (ref "J1") (pin "J30") (pinfunction "J30_J30") (pintype "passive"))
      (node (ref "J1") (pin "VJ30") (pinfunction "J30_VJ30") (pintype "passive"))
      (node (ref "R300") (pin "2") (pinfunction "2_2") (pintype "passive"))
    )
  )
)
